# Schematic_Tektronix_Auxiliary_Front_Pane.net
KiCad netlist of a schematic drawn in EasyEDA
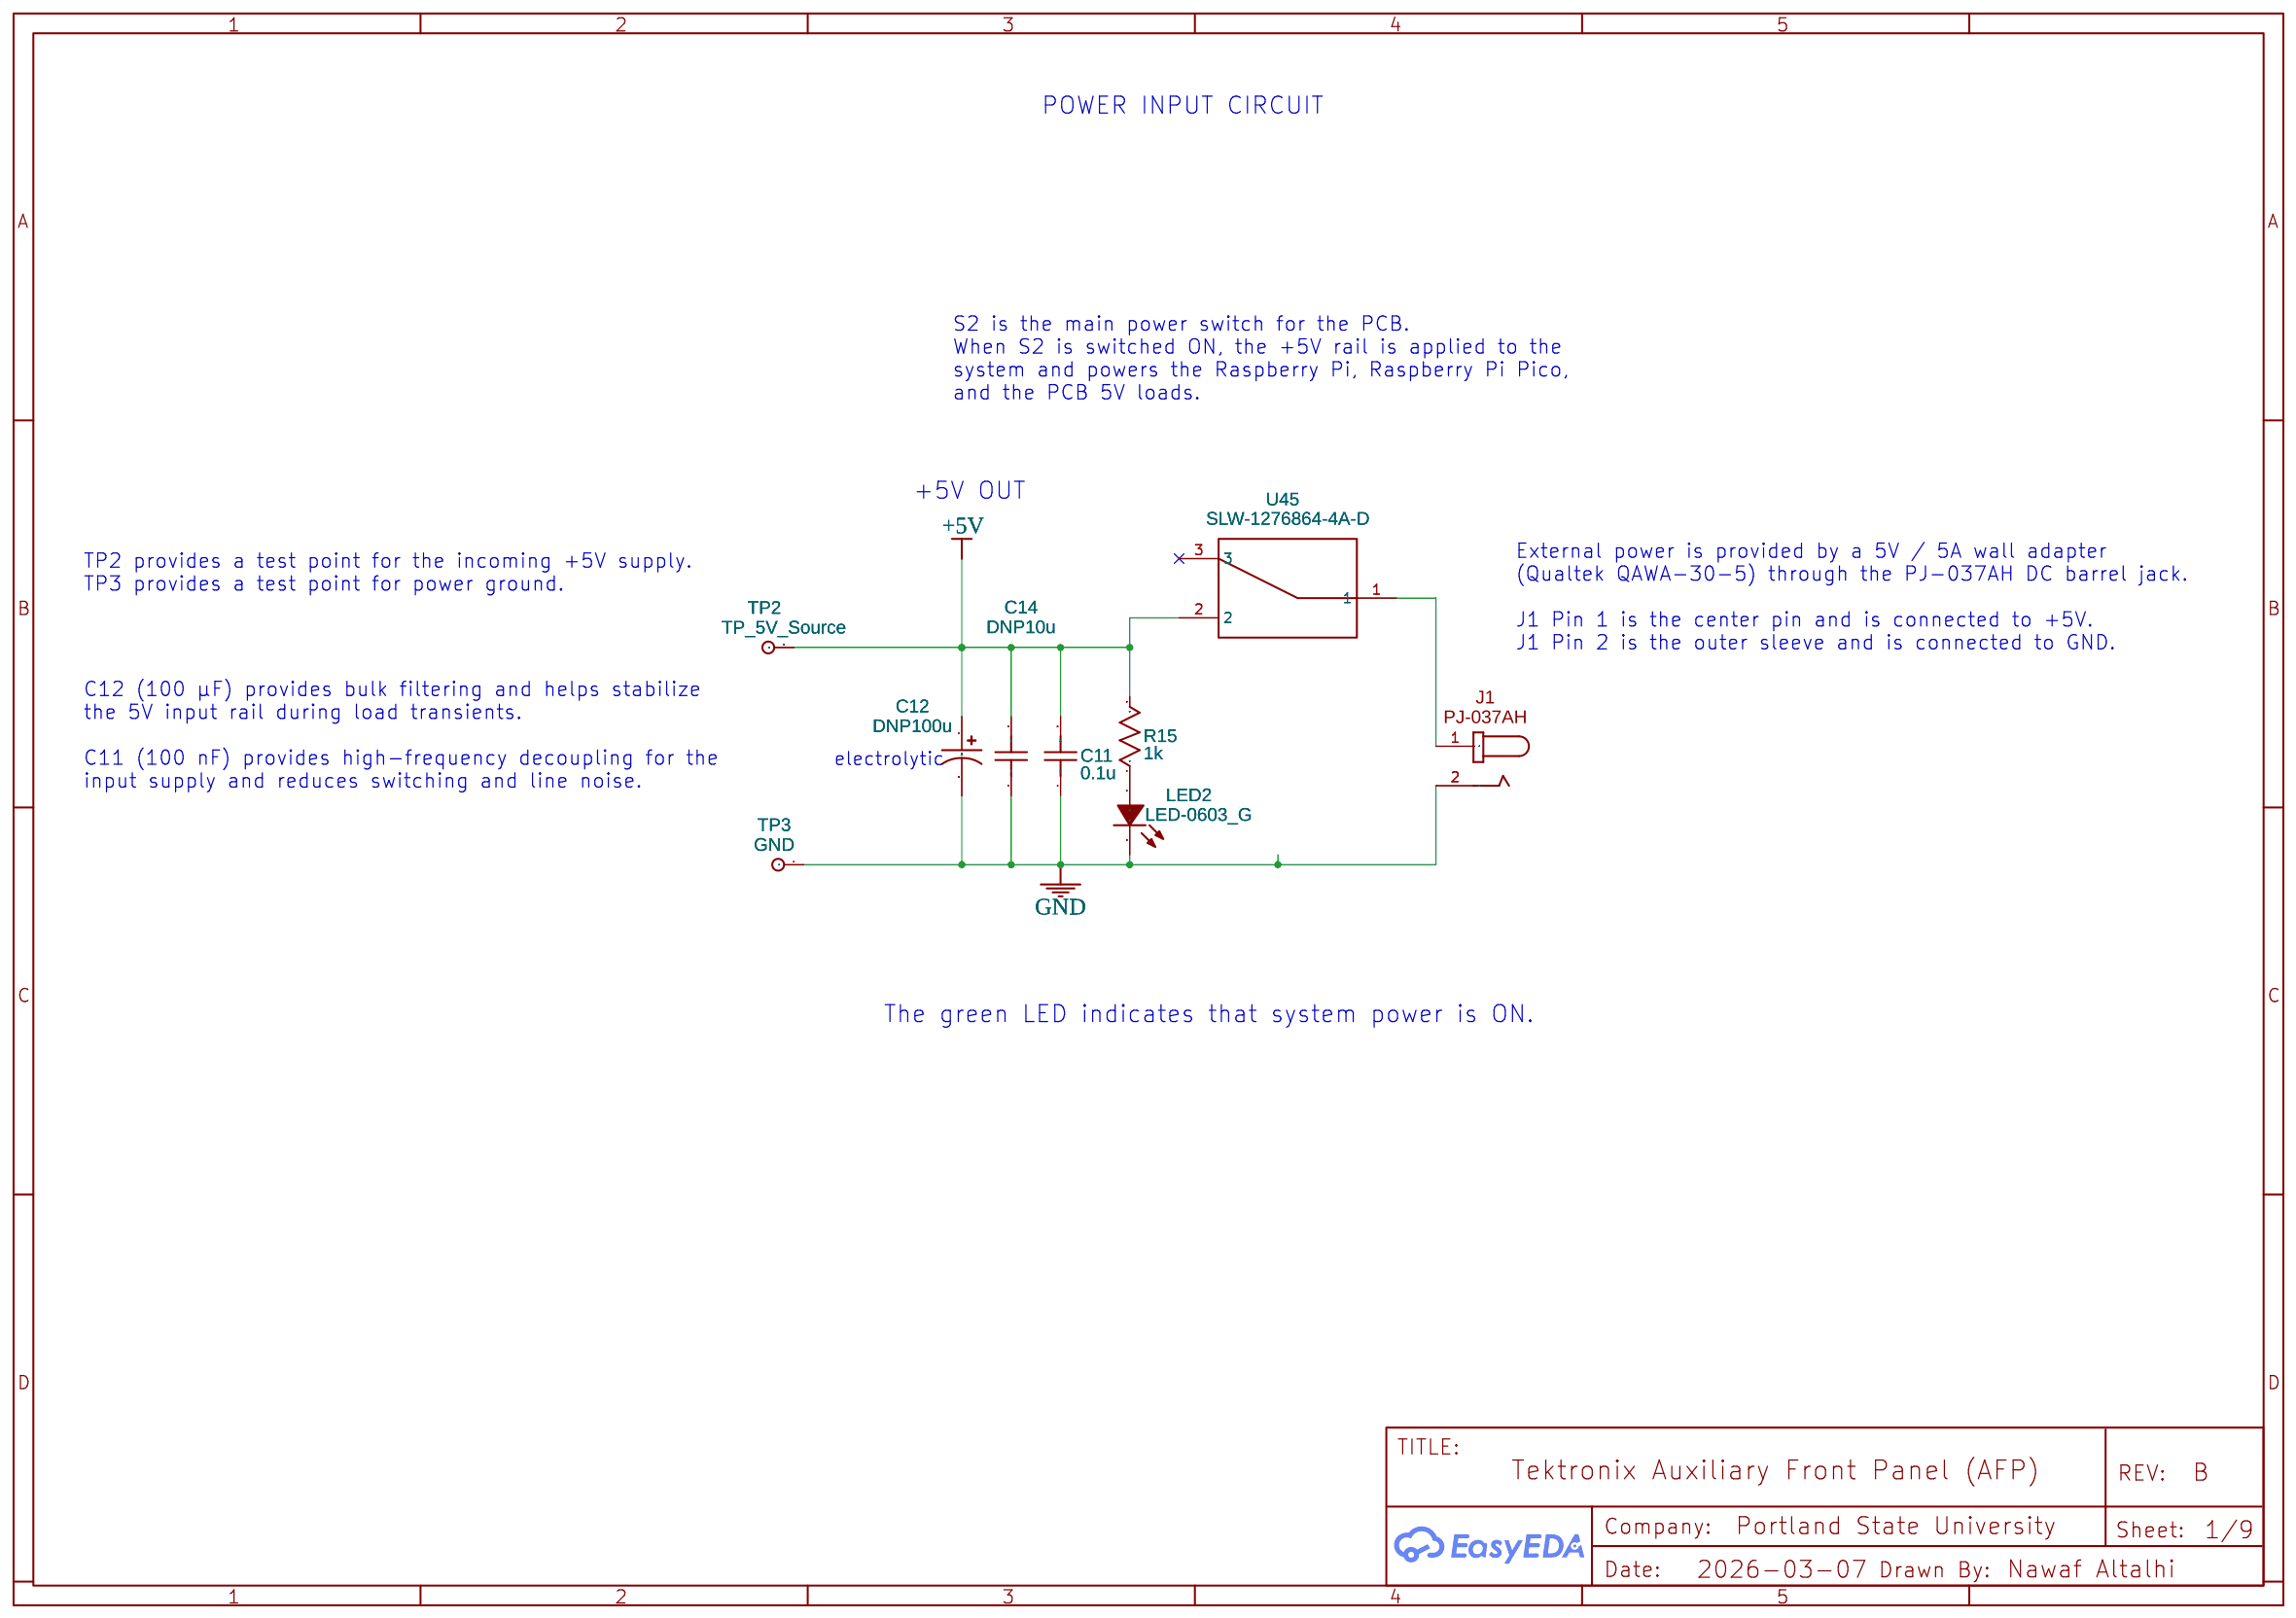
[diagram p0: 5V Power Input]
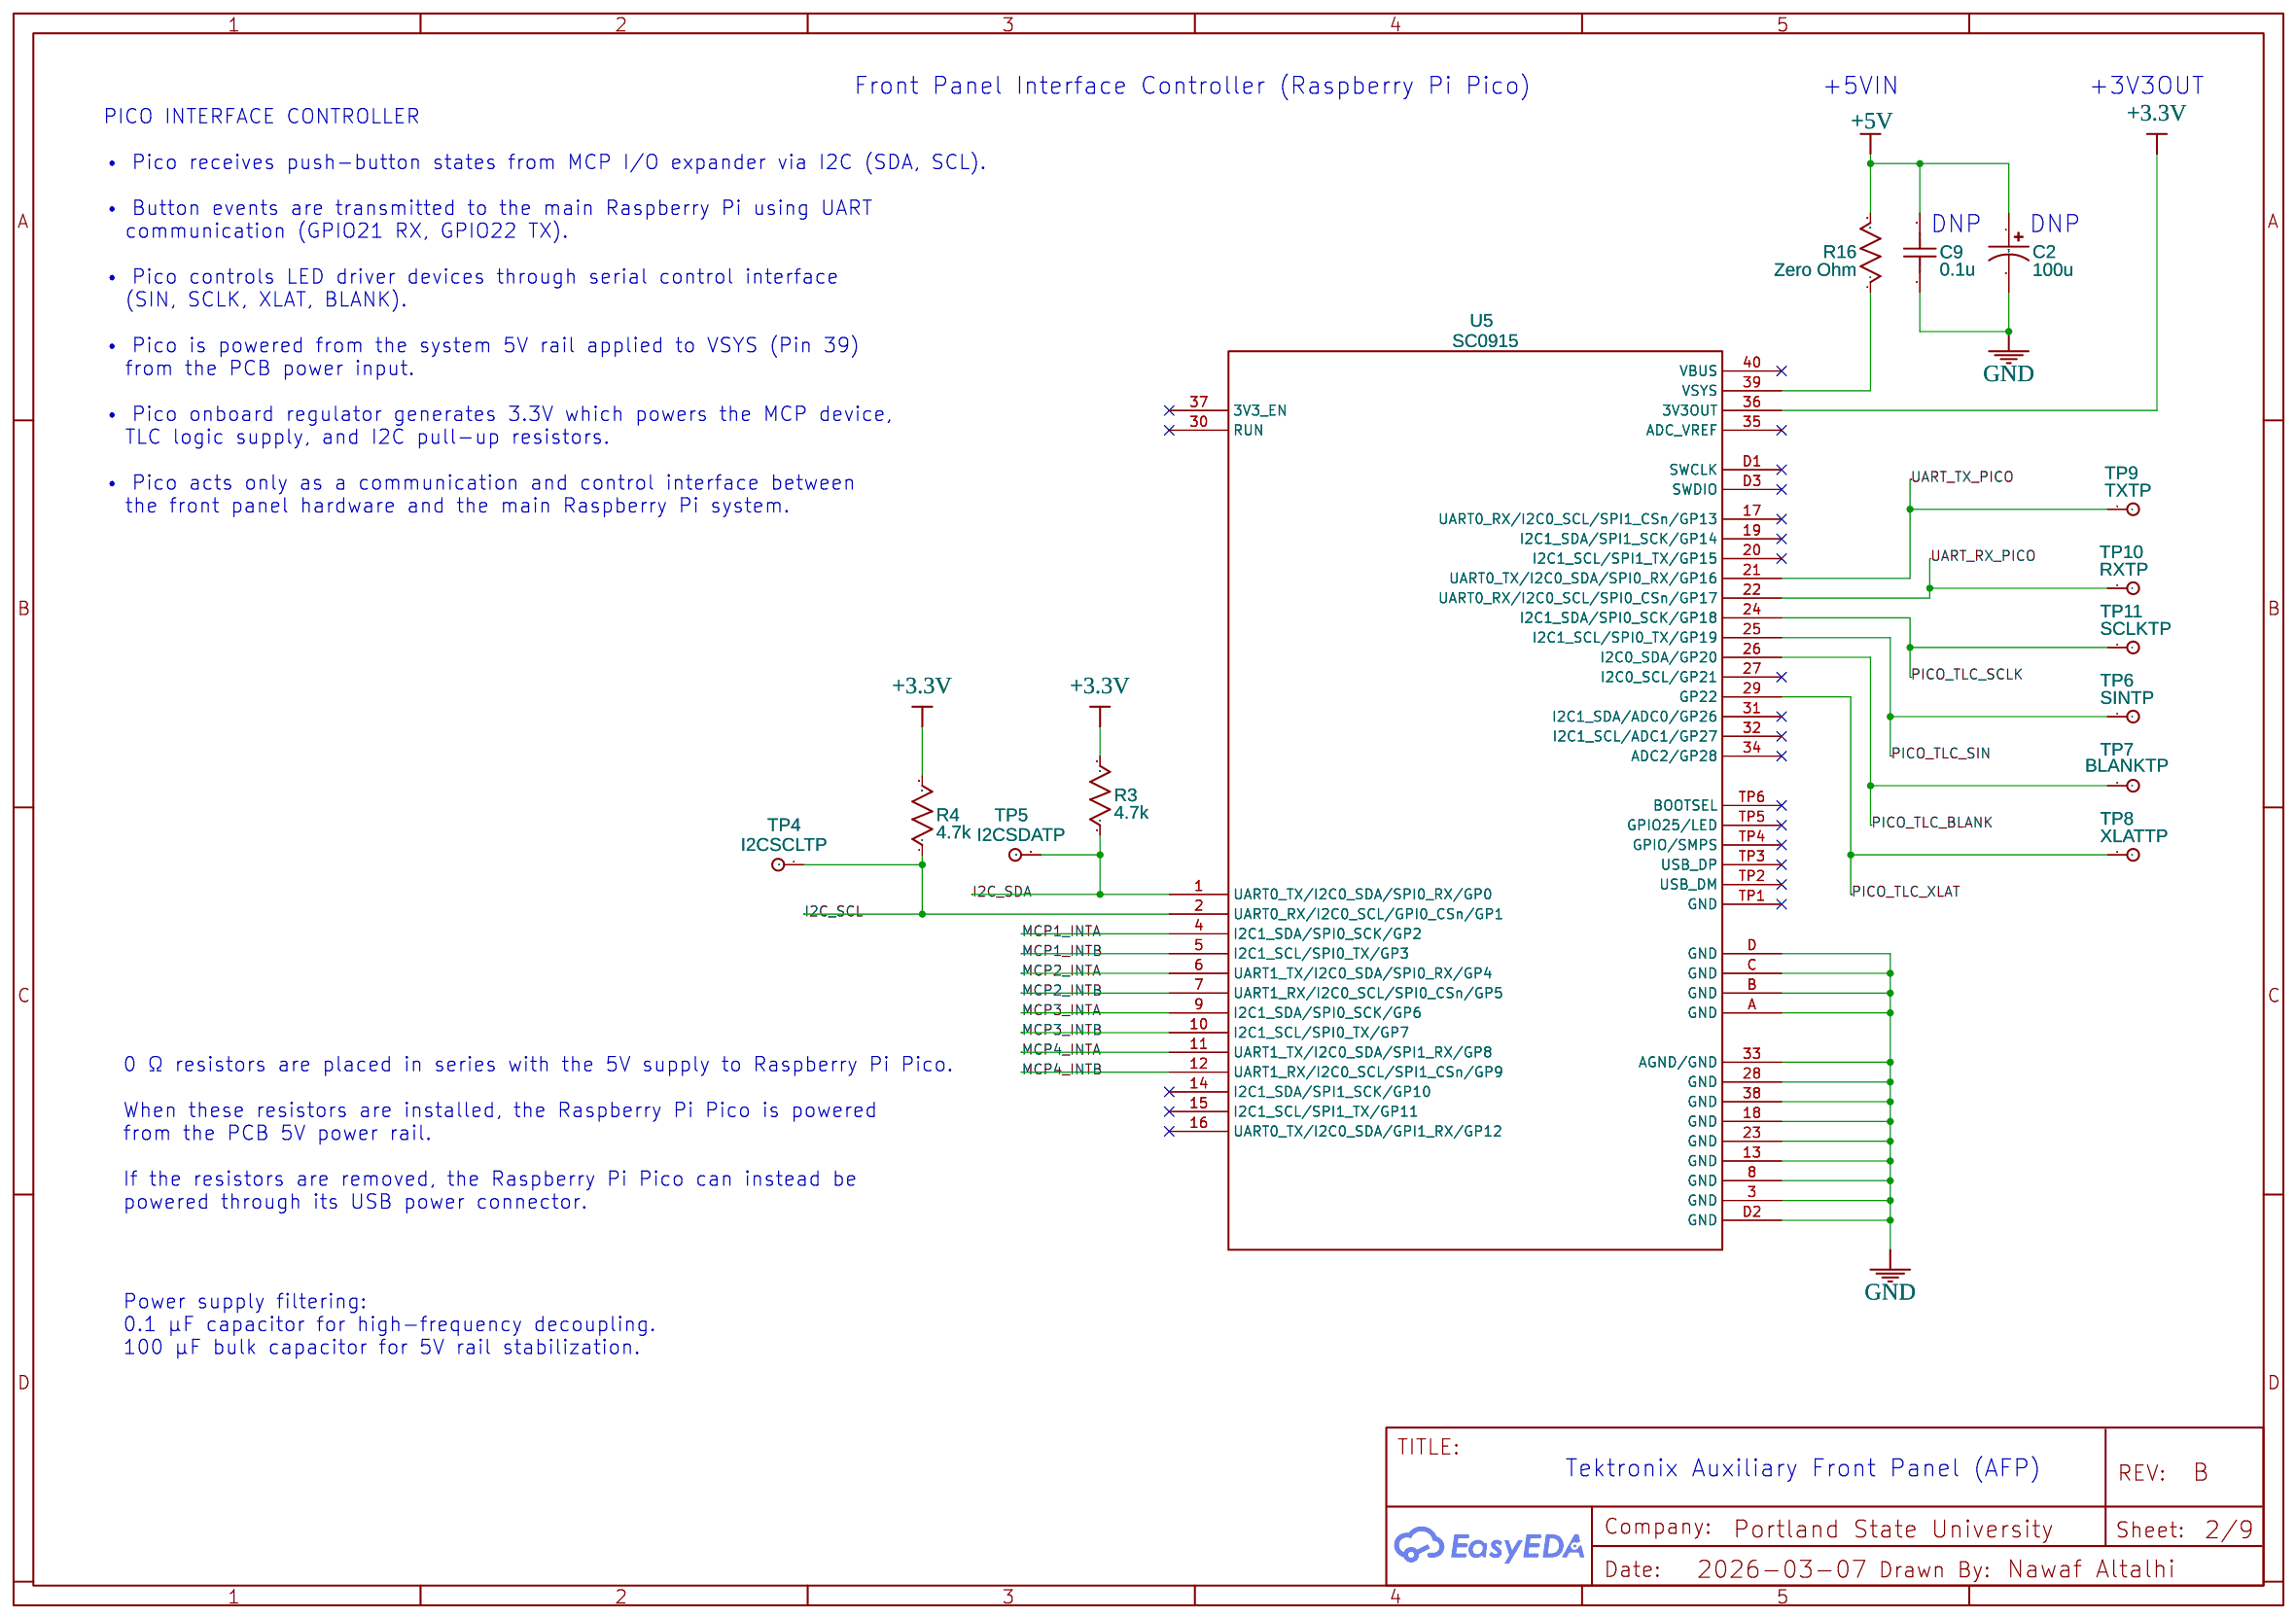
[diagram p1: Raspberry Pi Pico Interface]
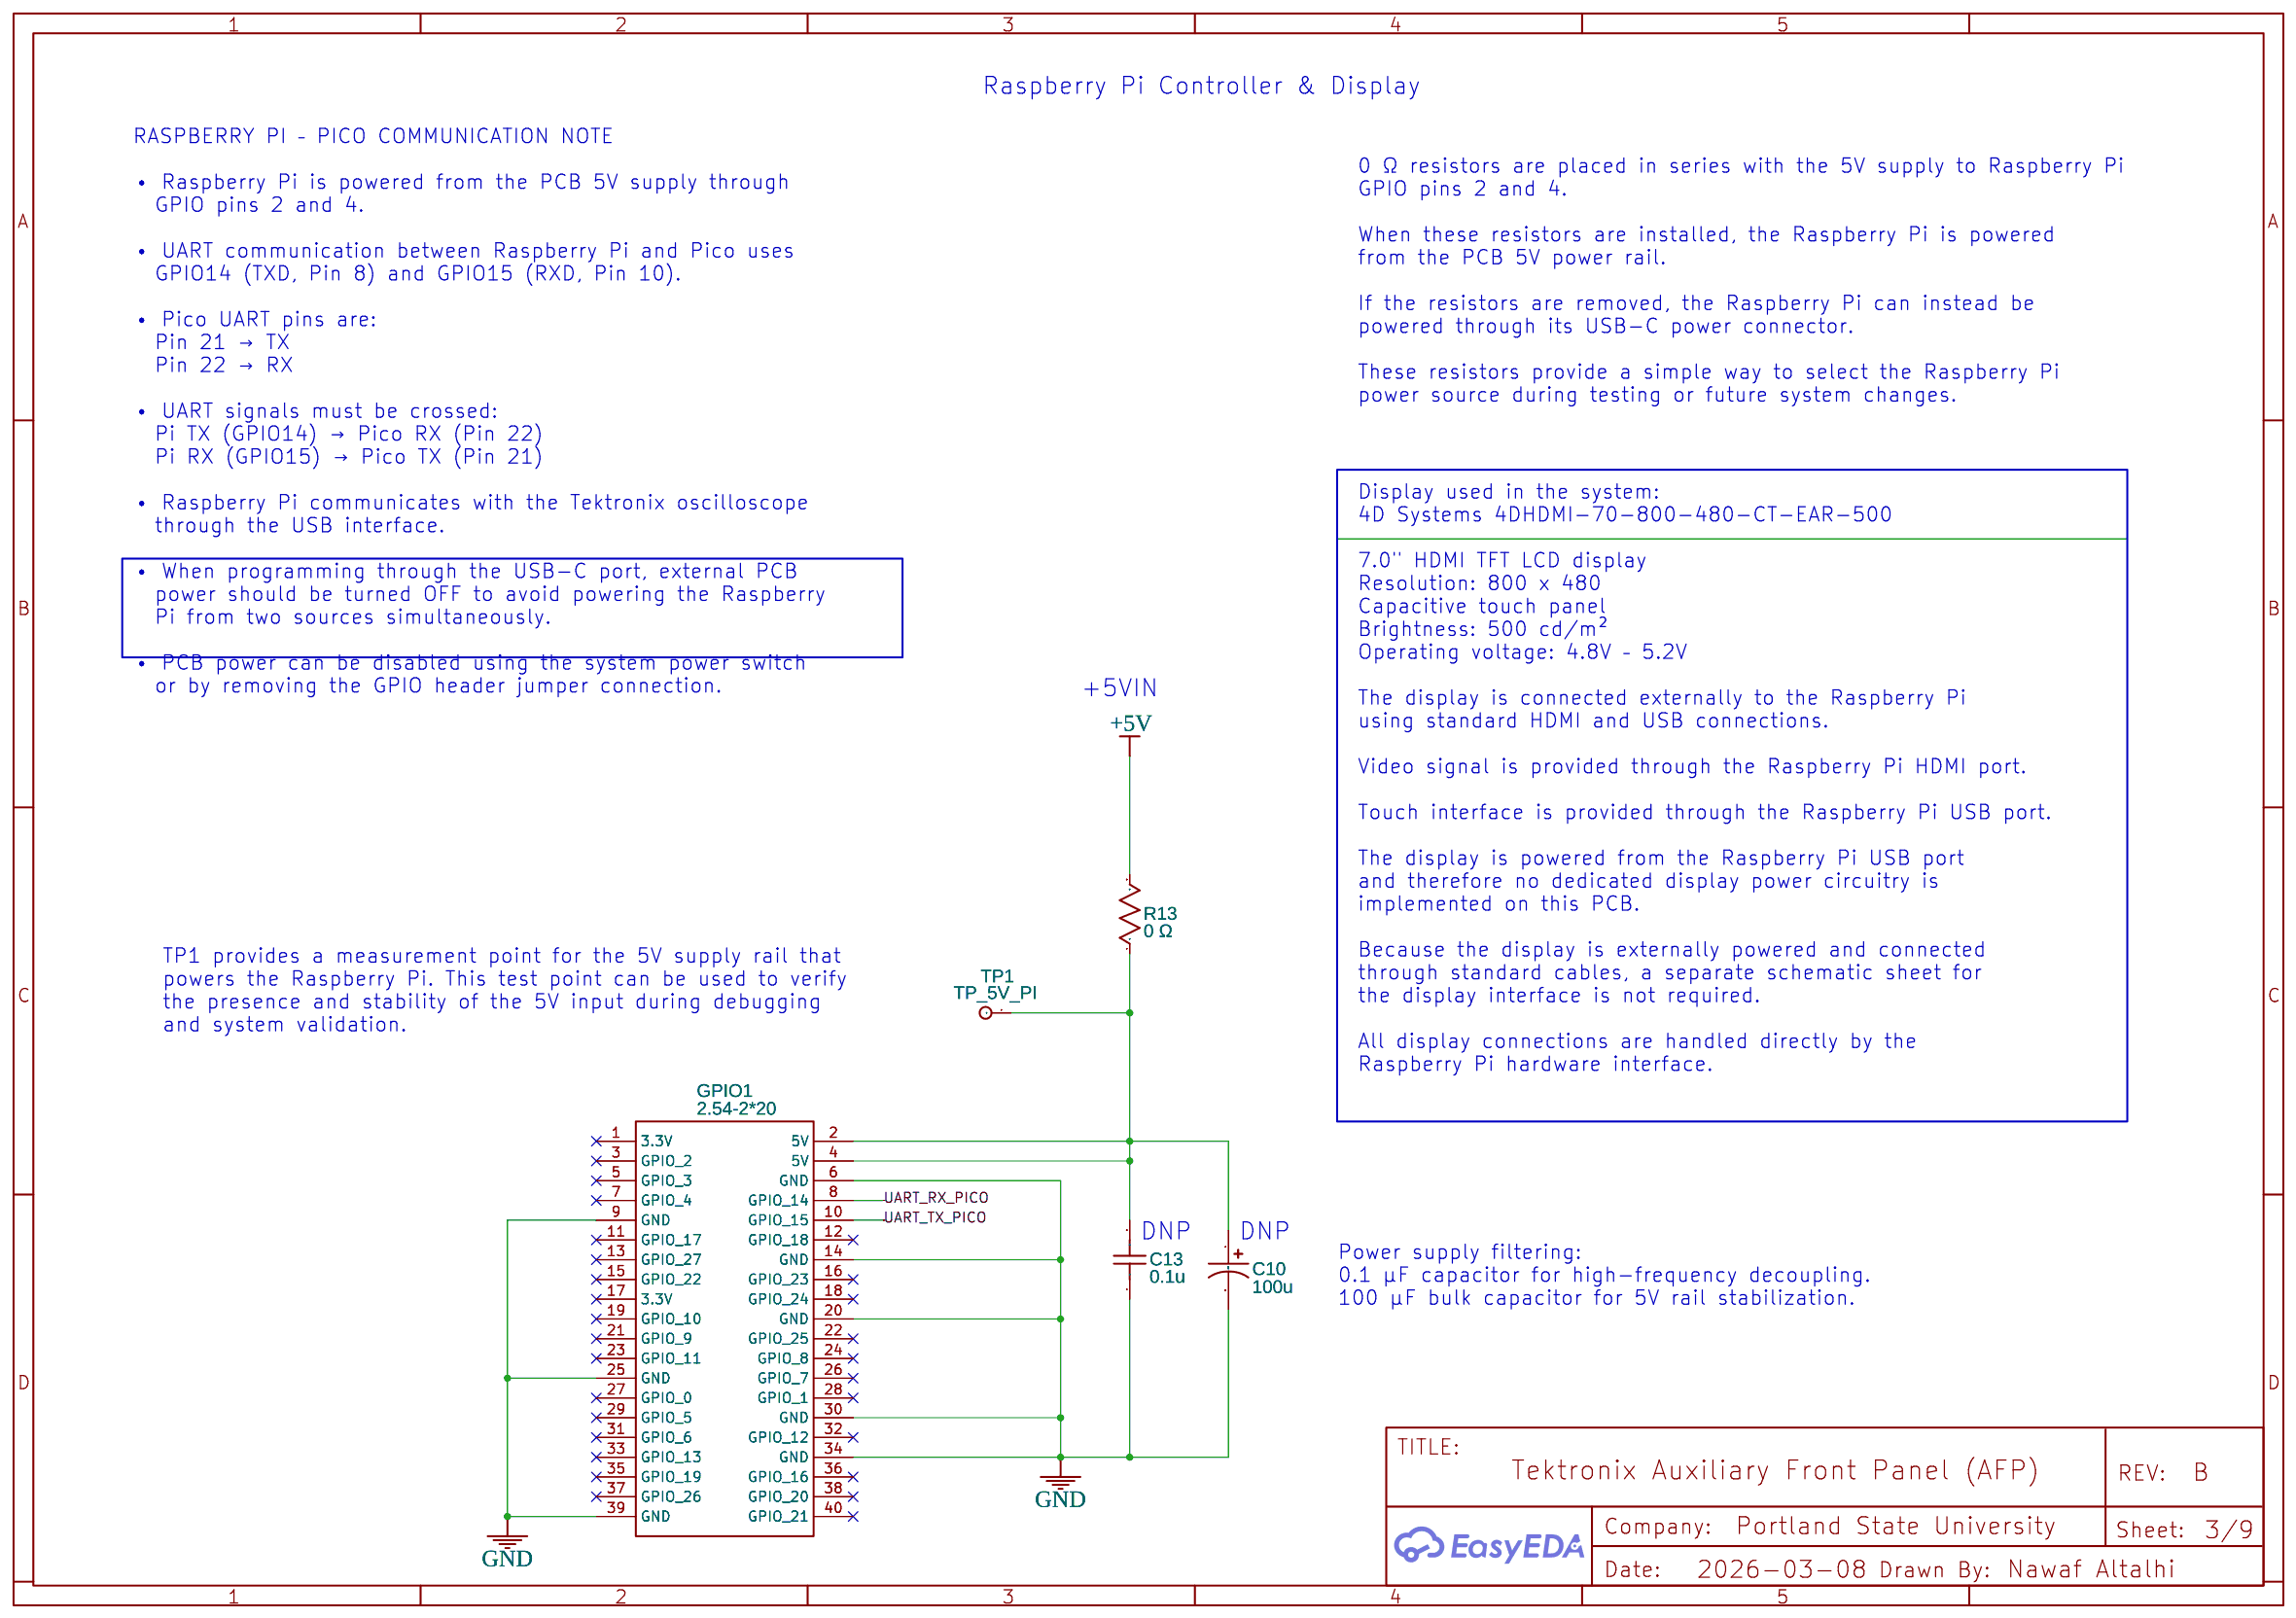
[diagram p2: Raspberry Pi Controller]
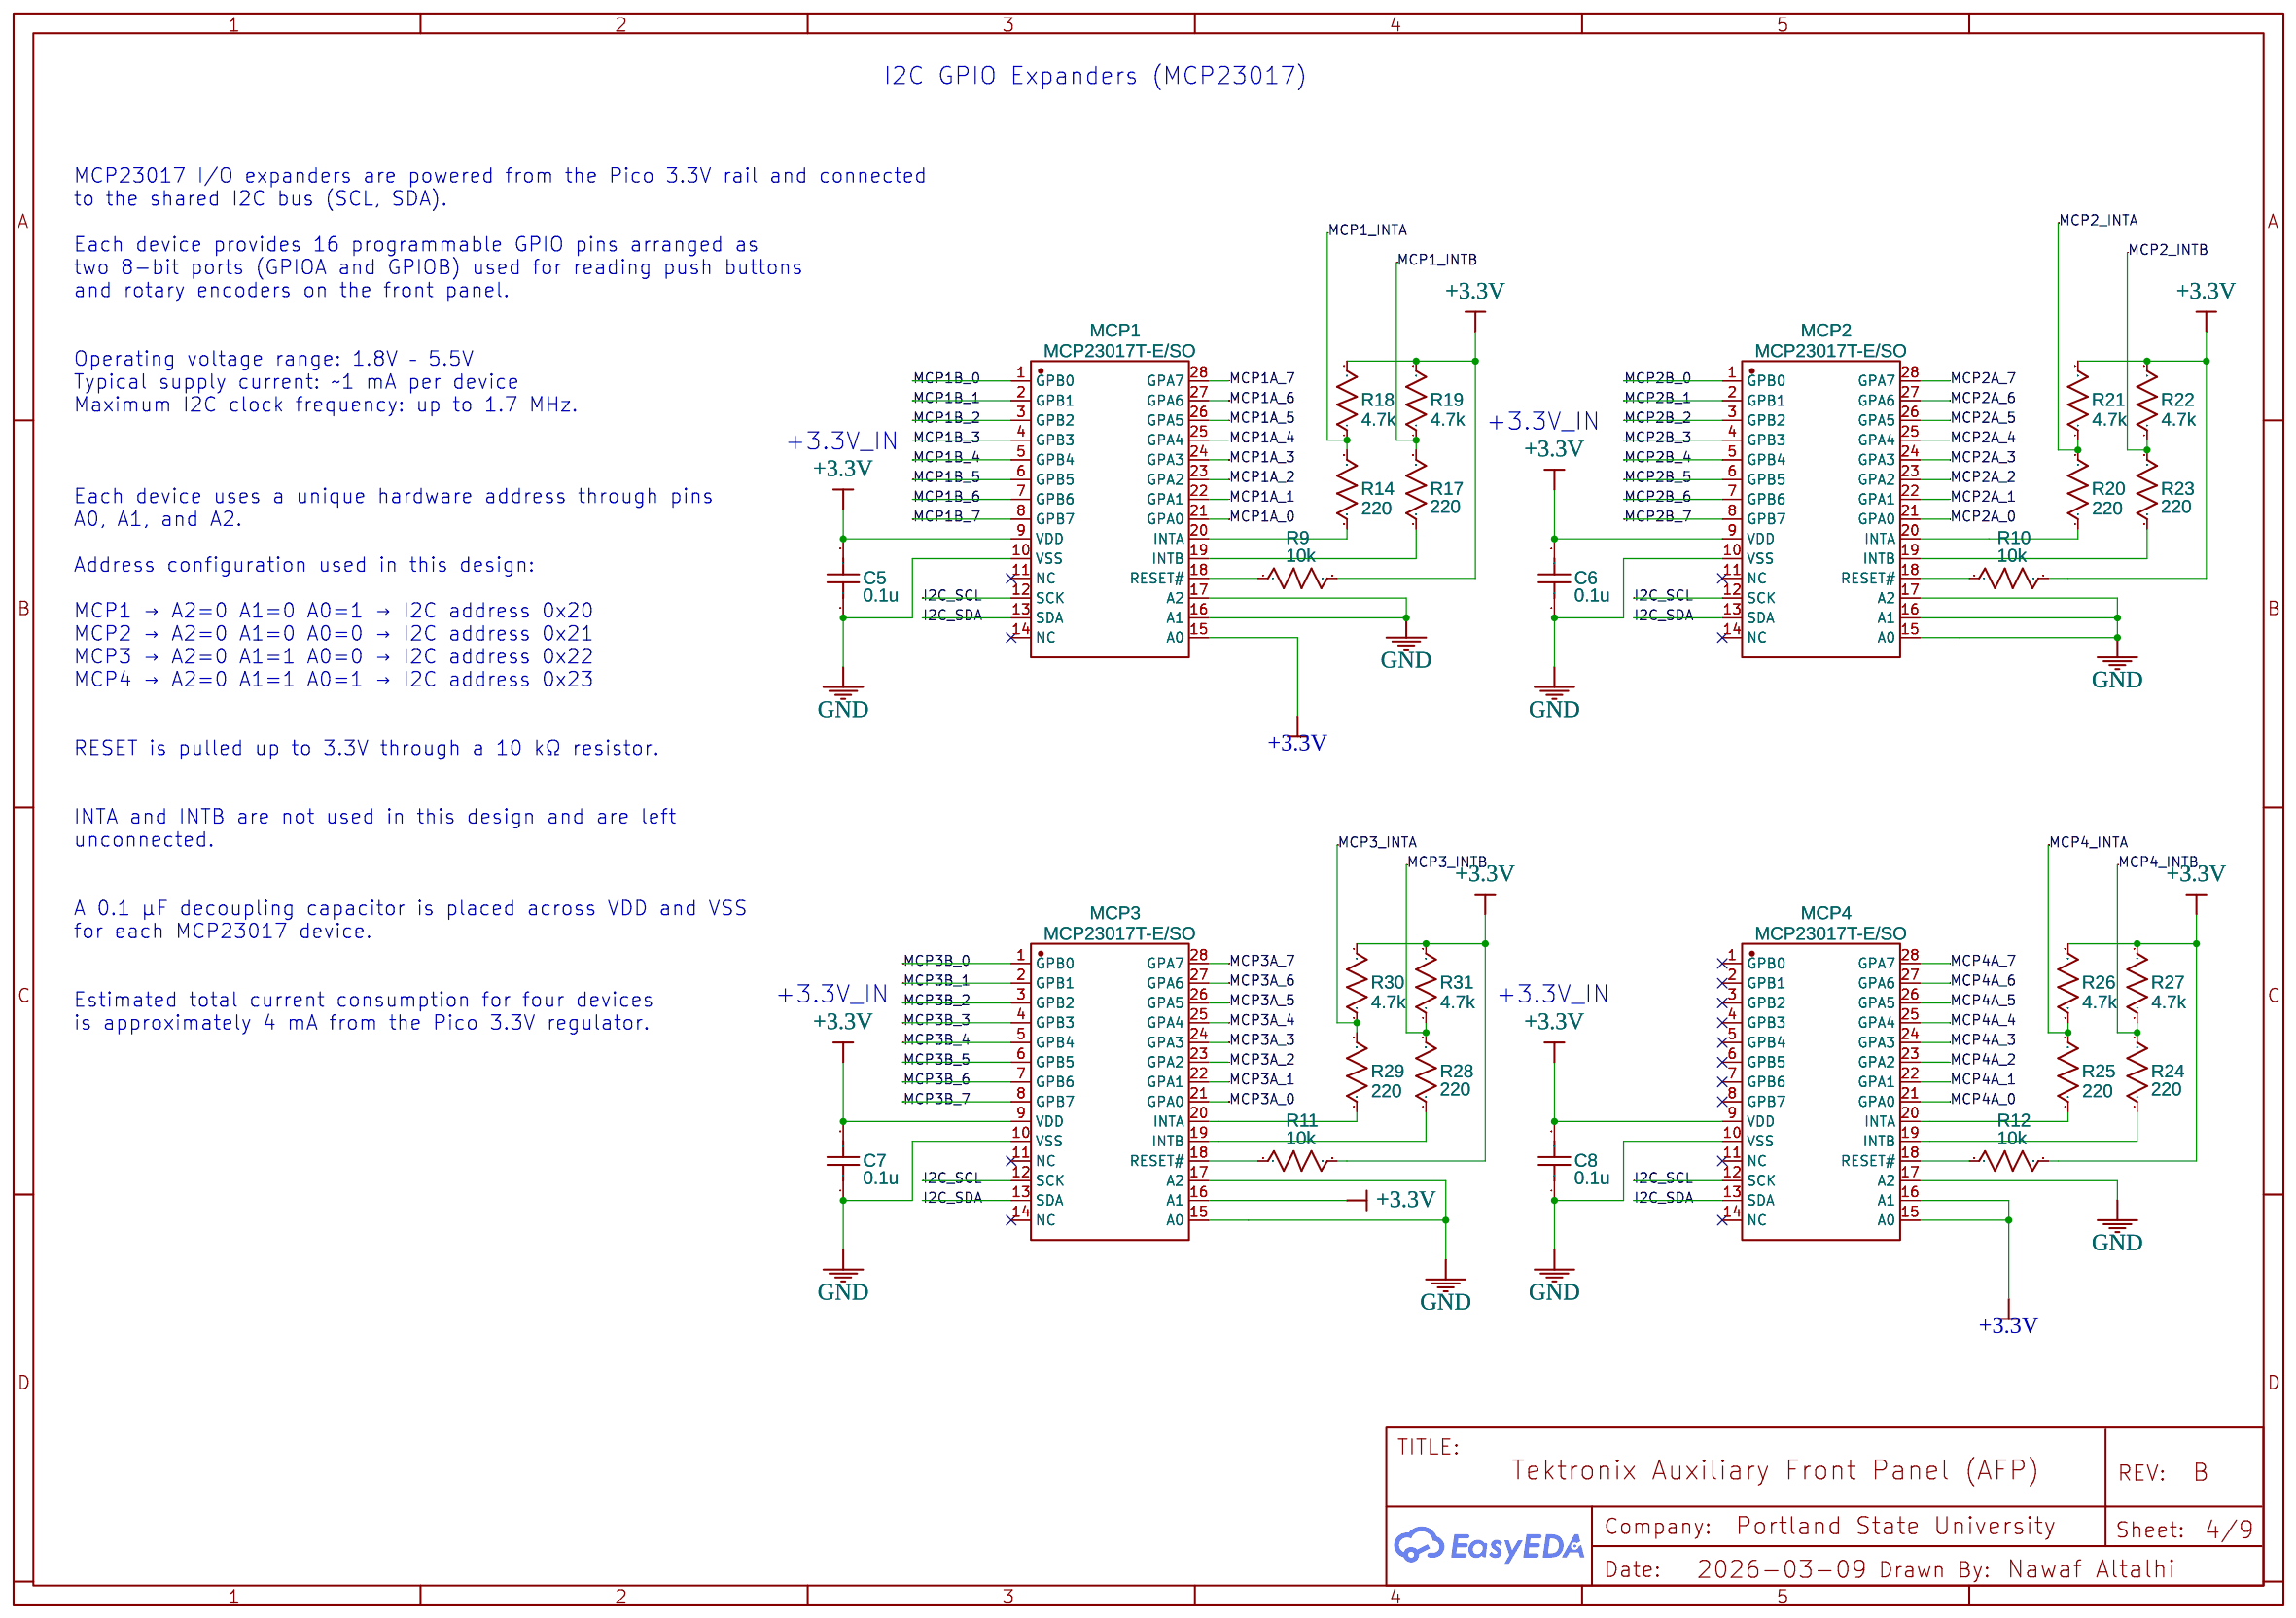
[diagram p3: MCP23017]
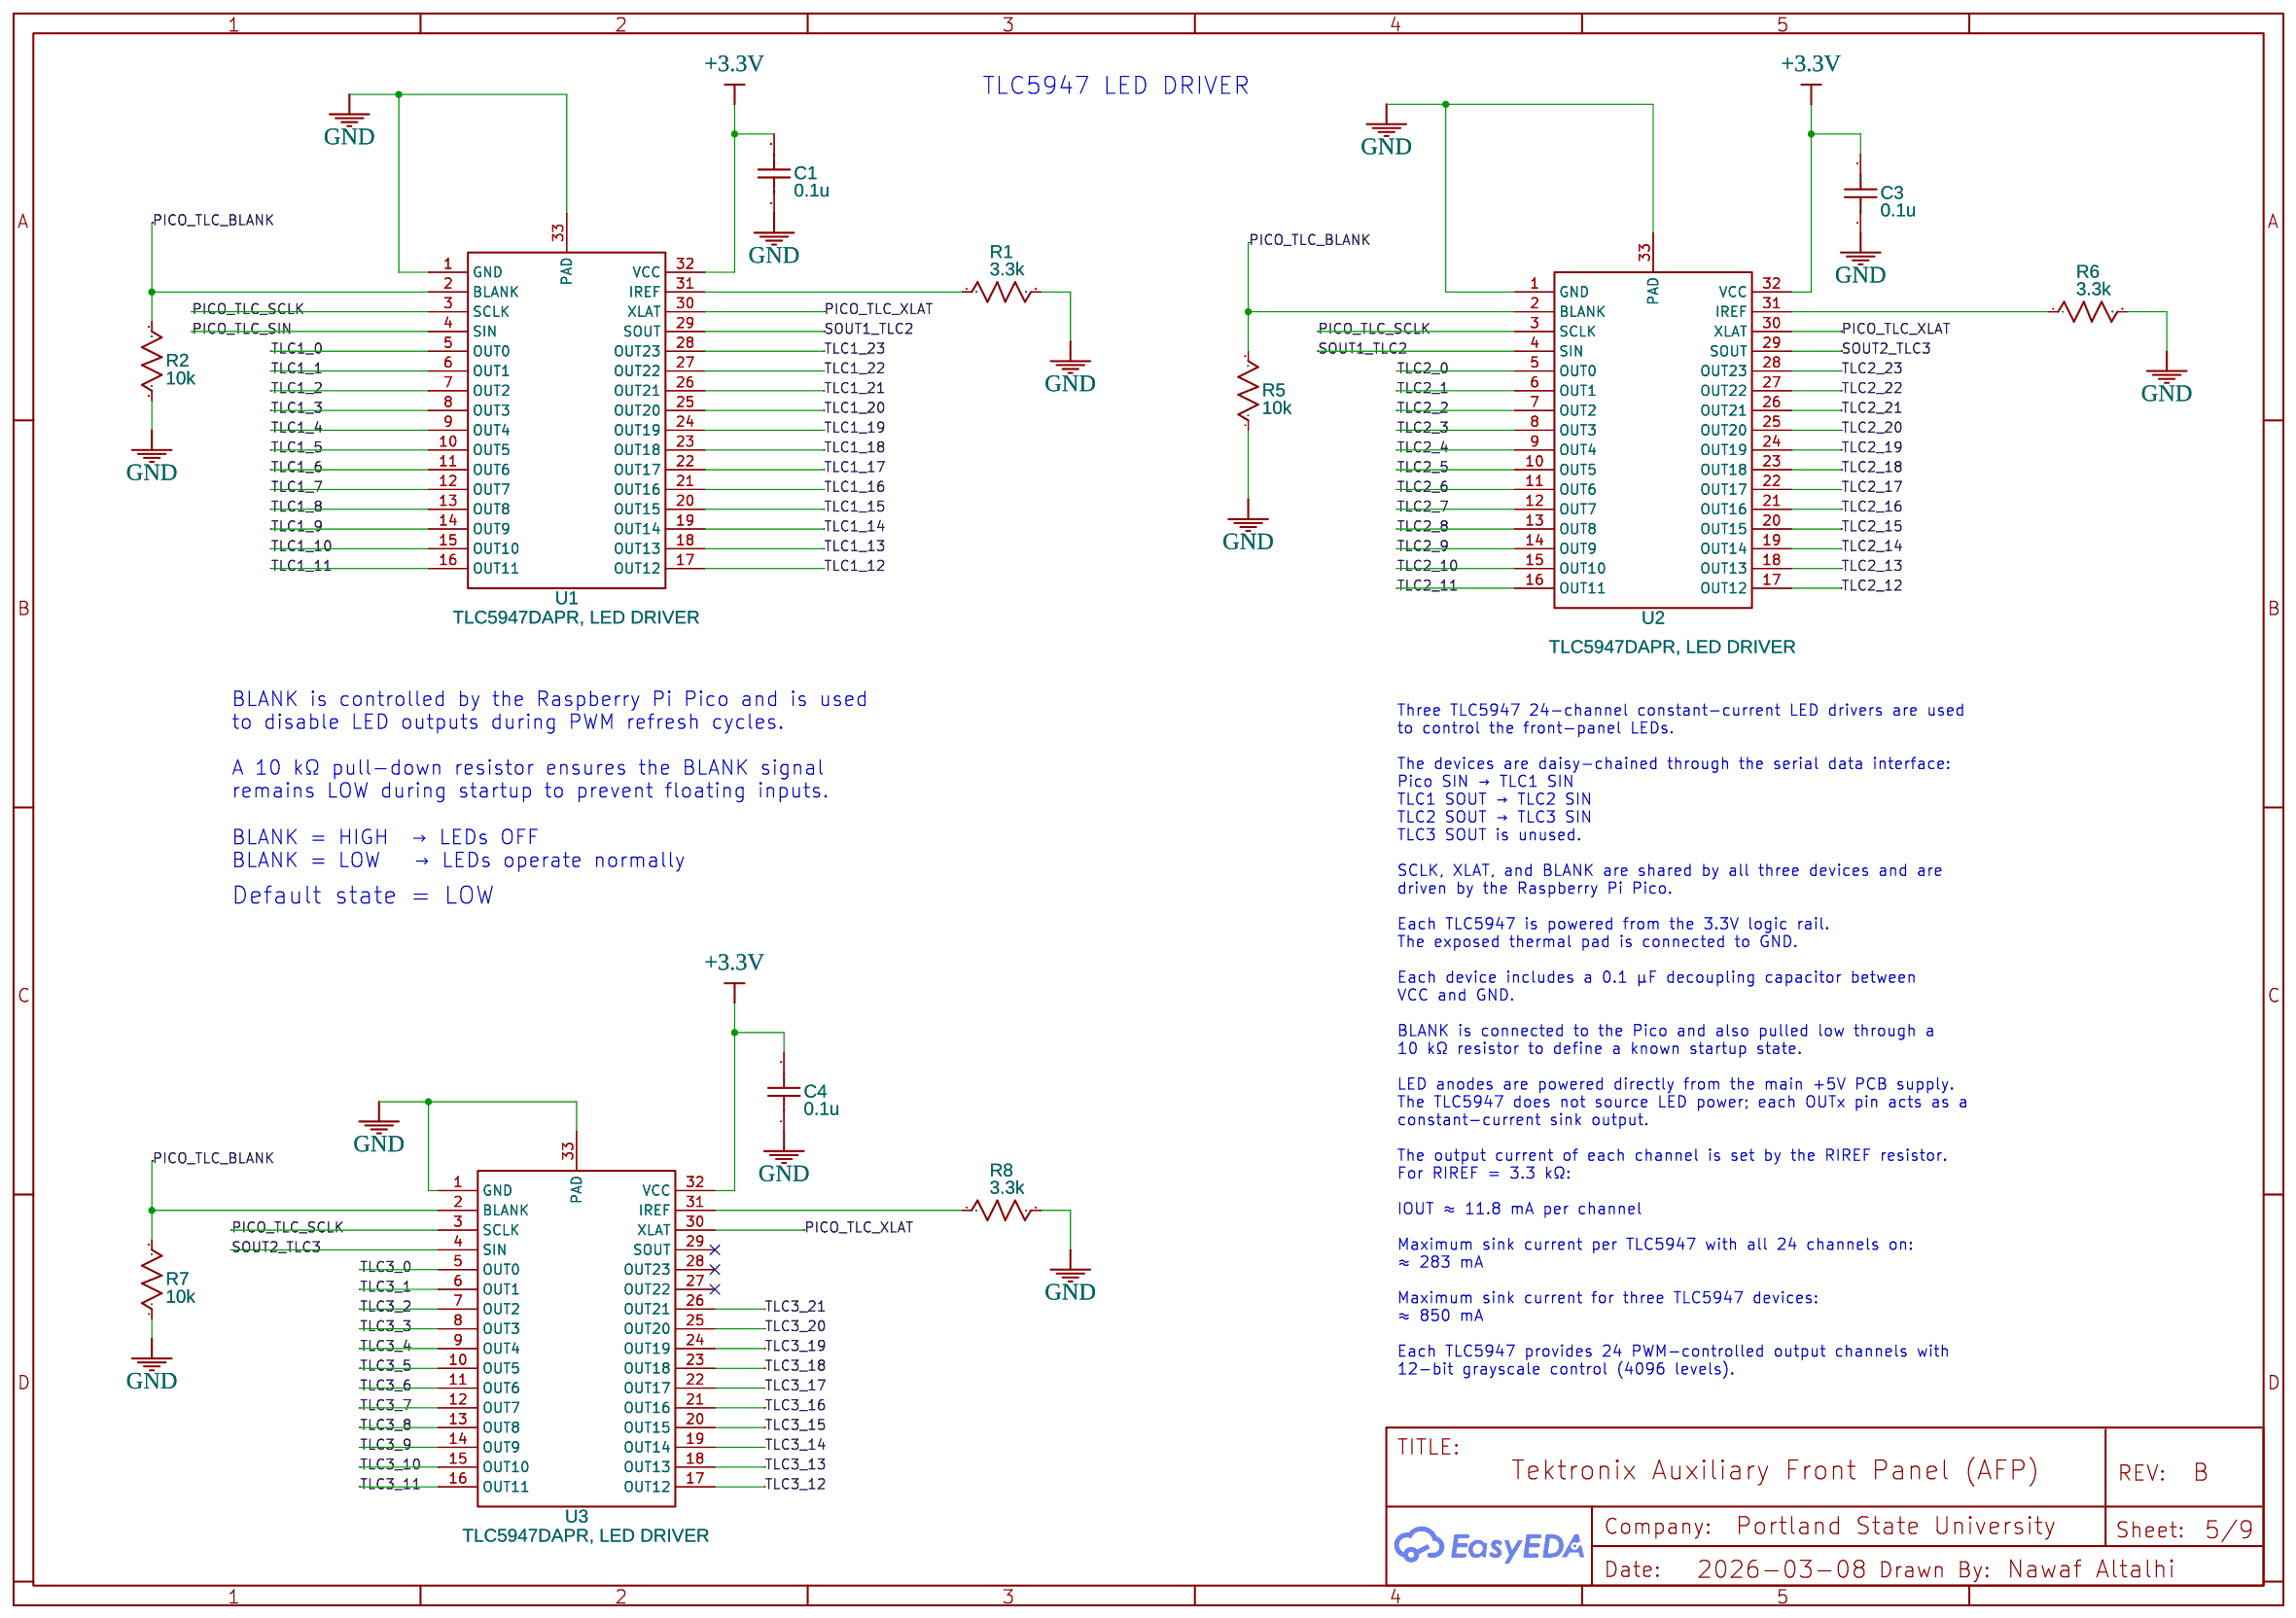
[diagram p4: TLC5947]
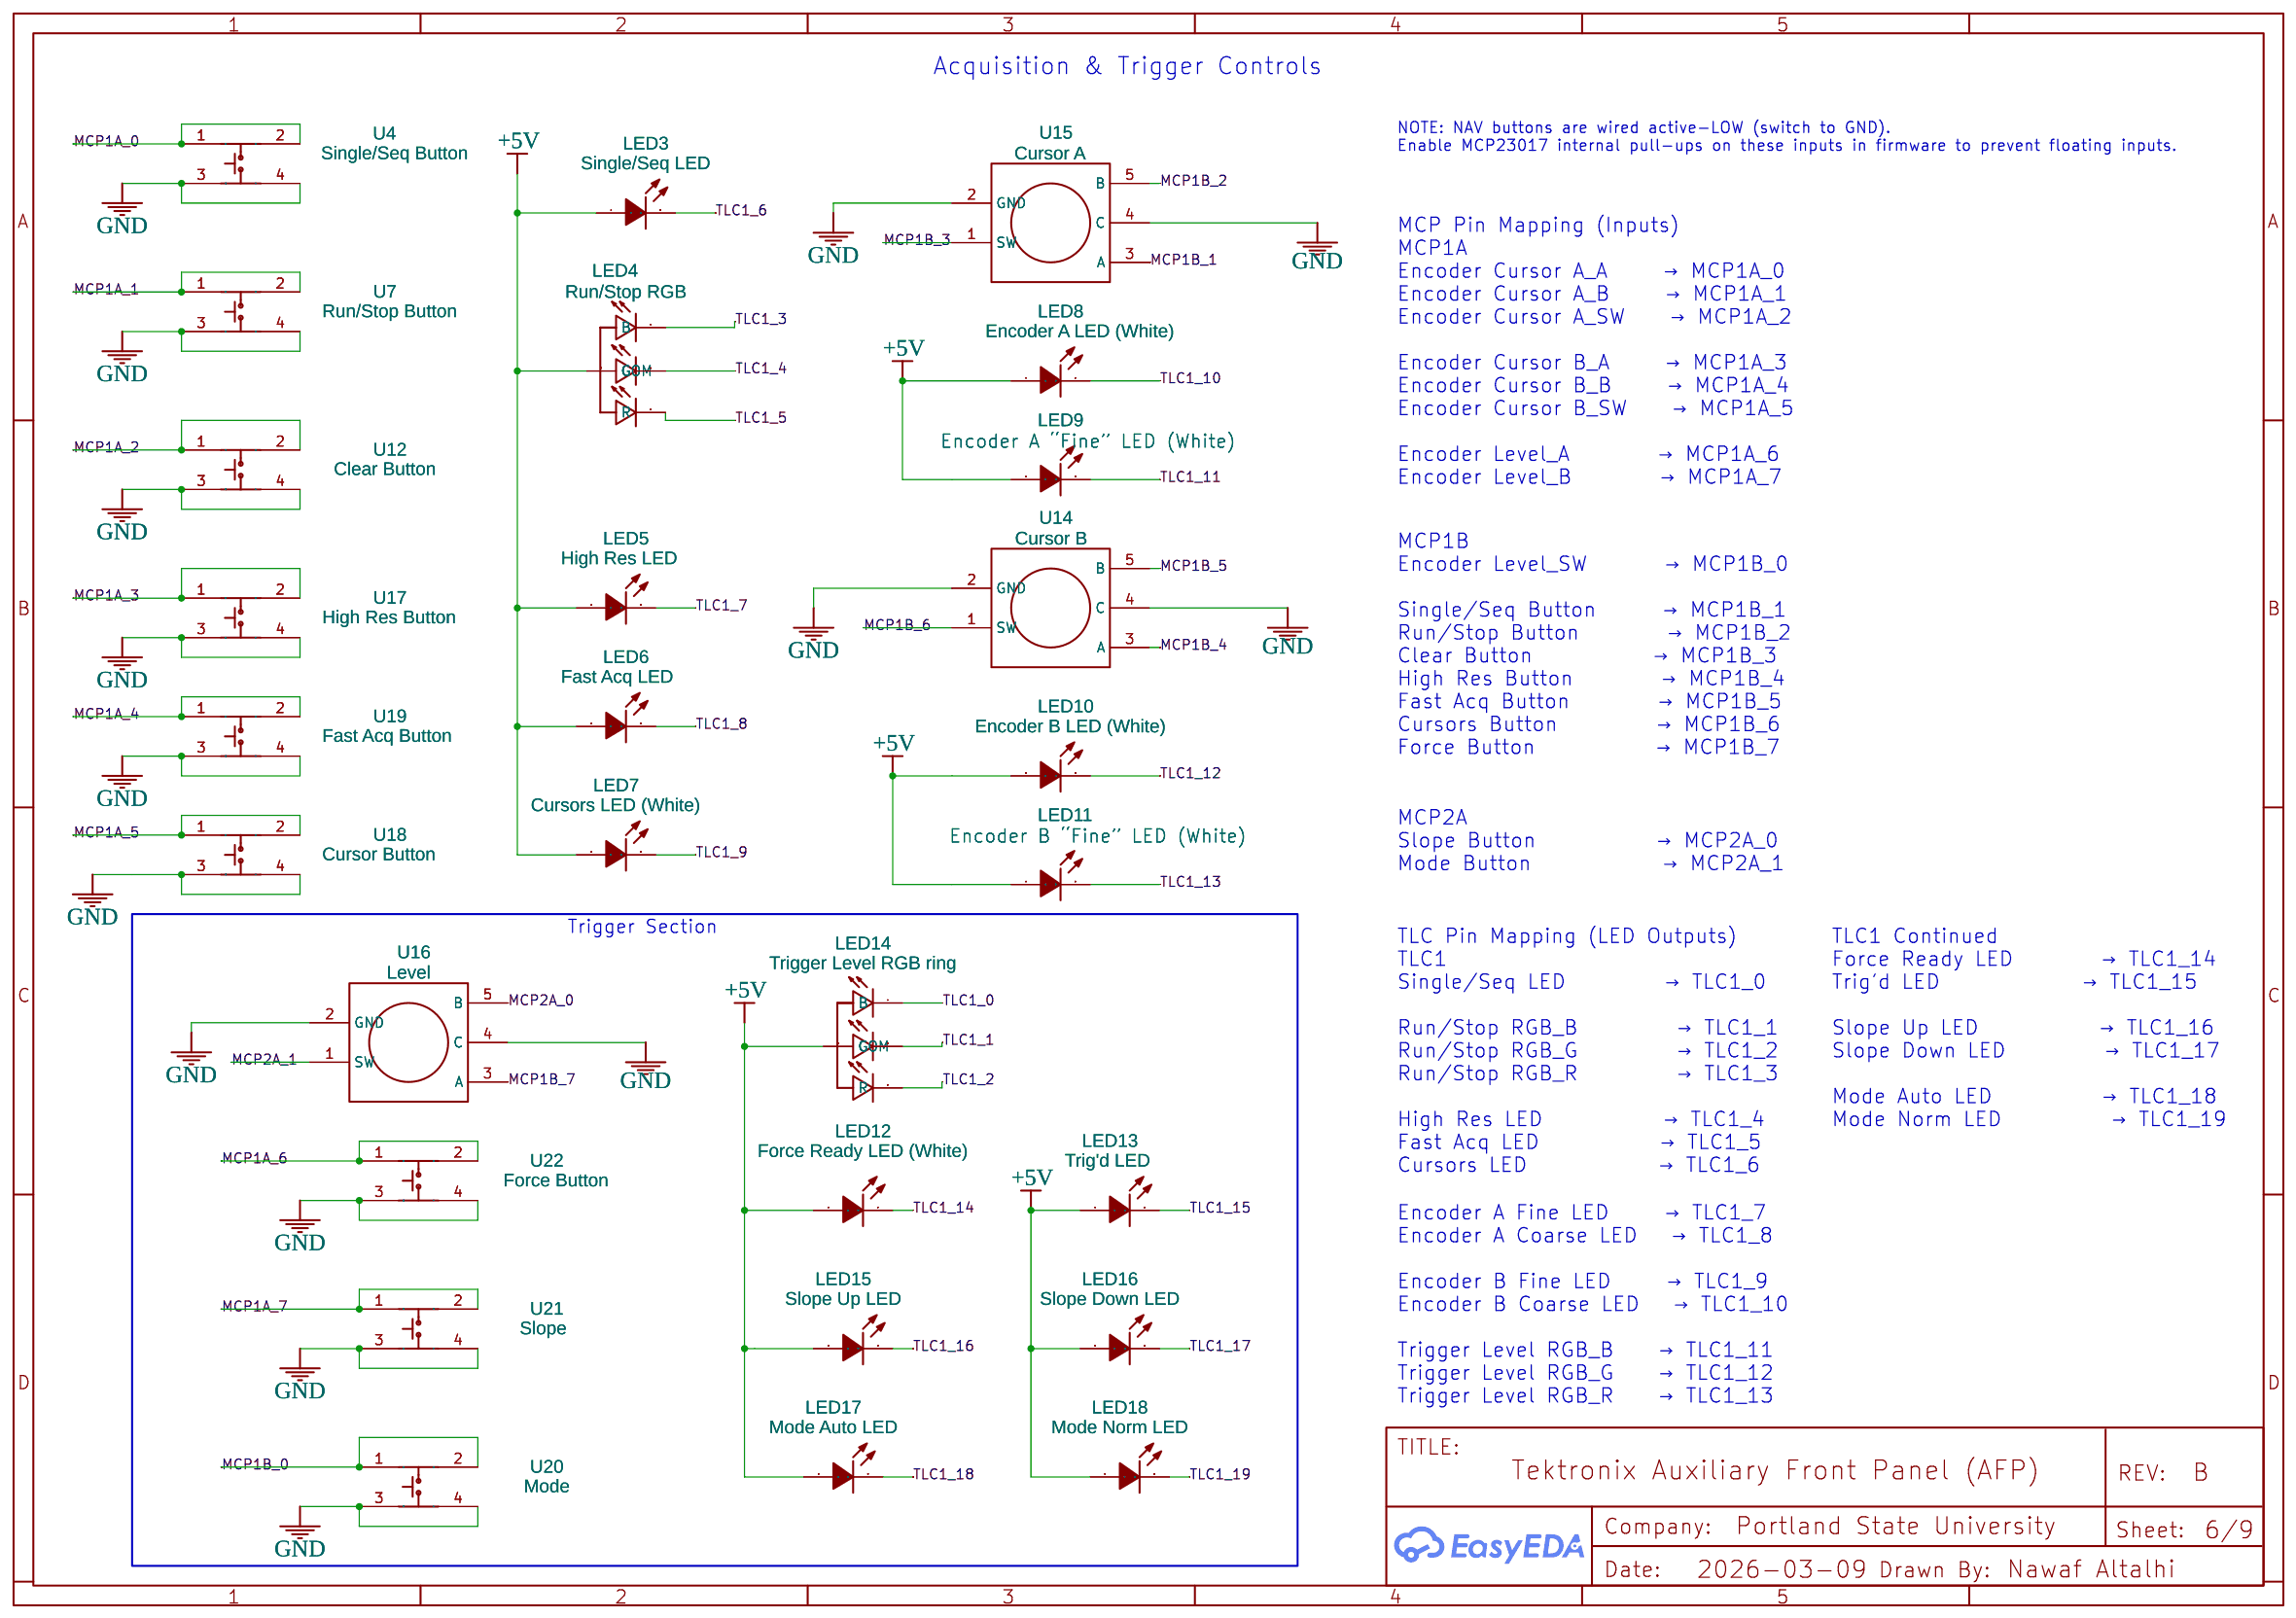
[diagram p5: Acquisition & Trigger Controls]
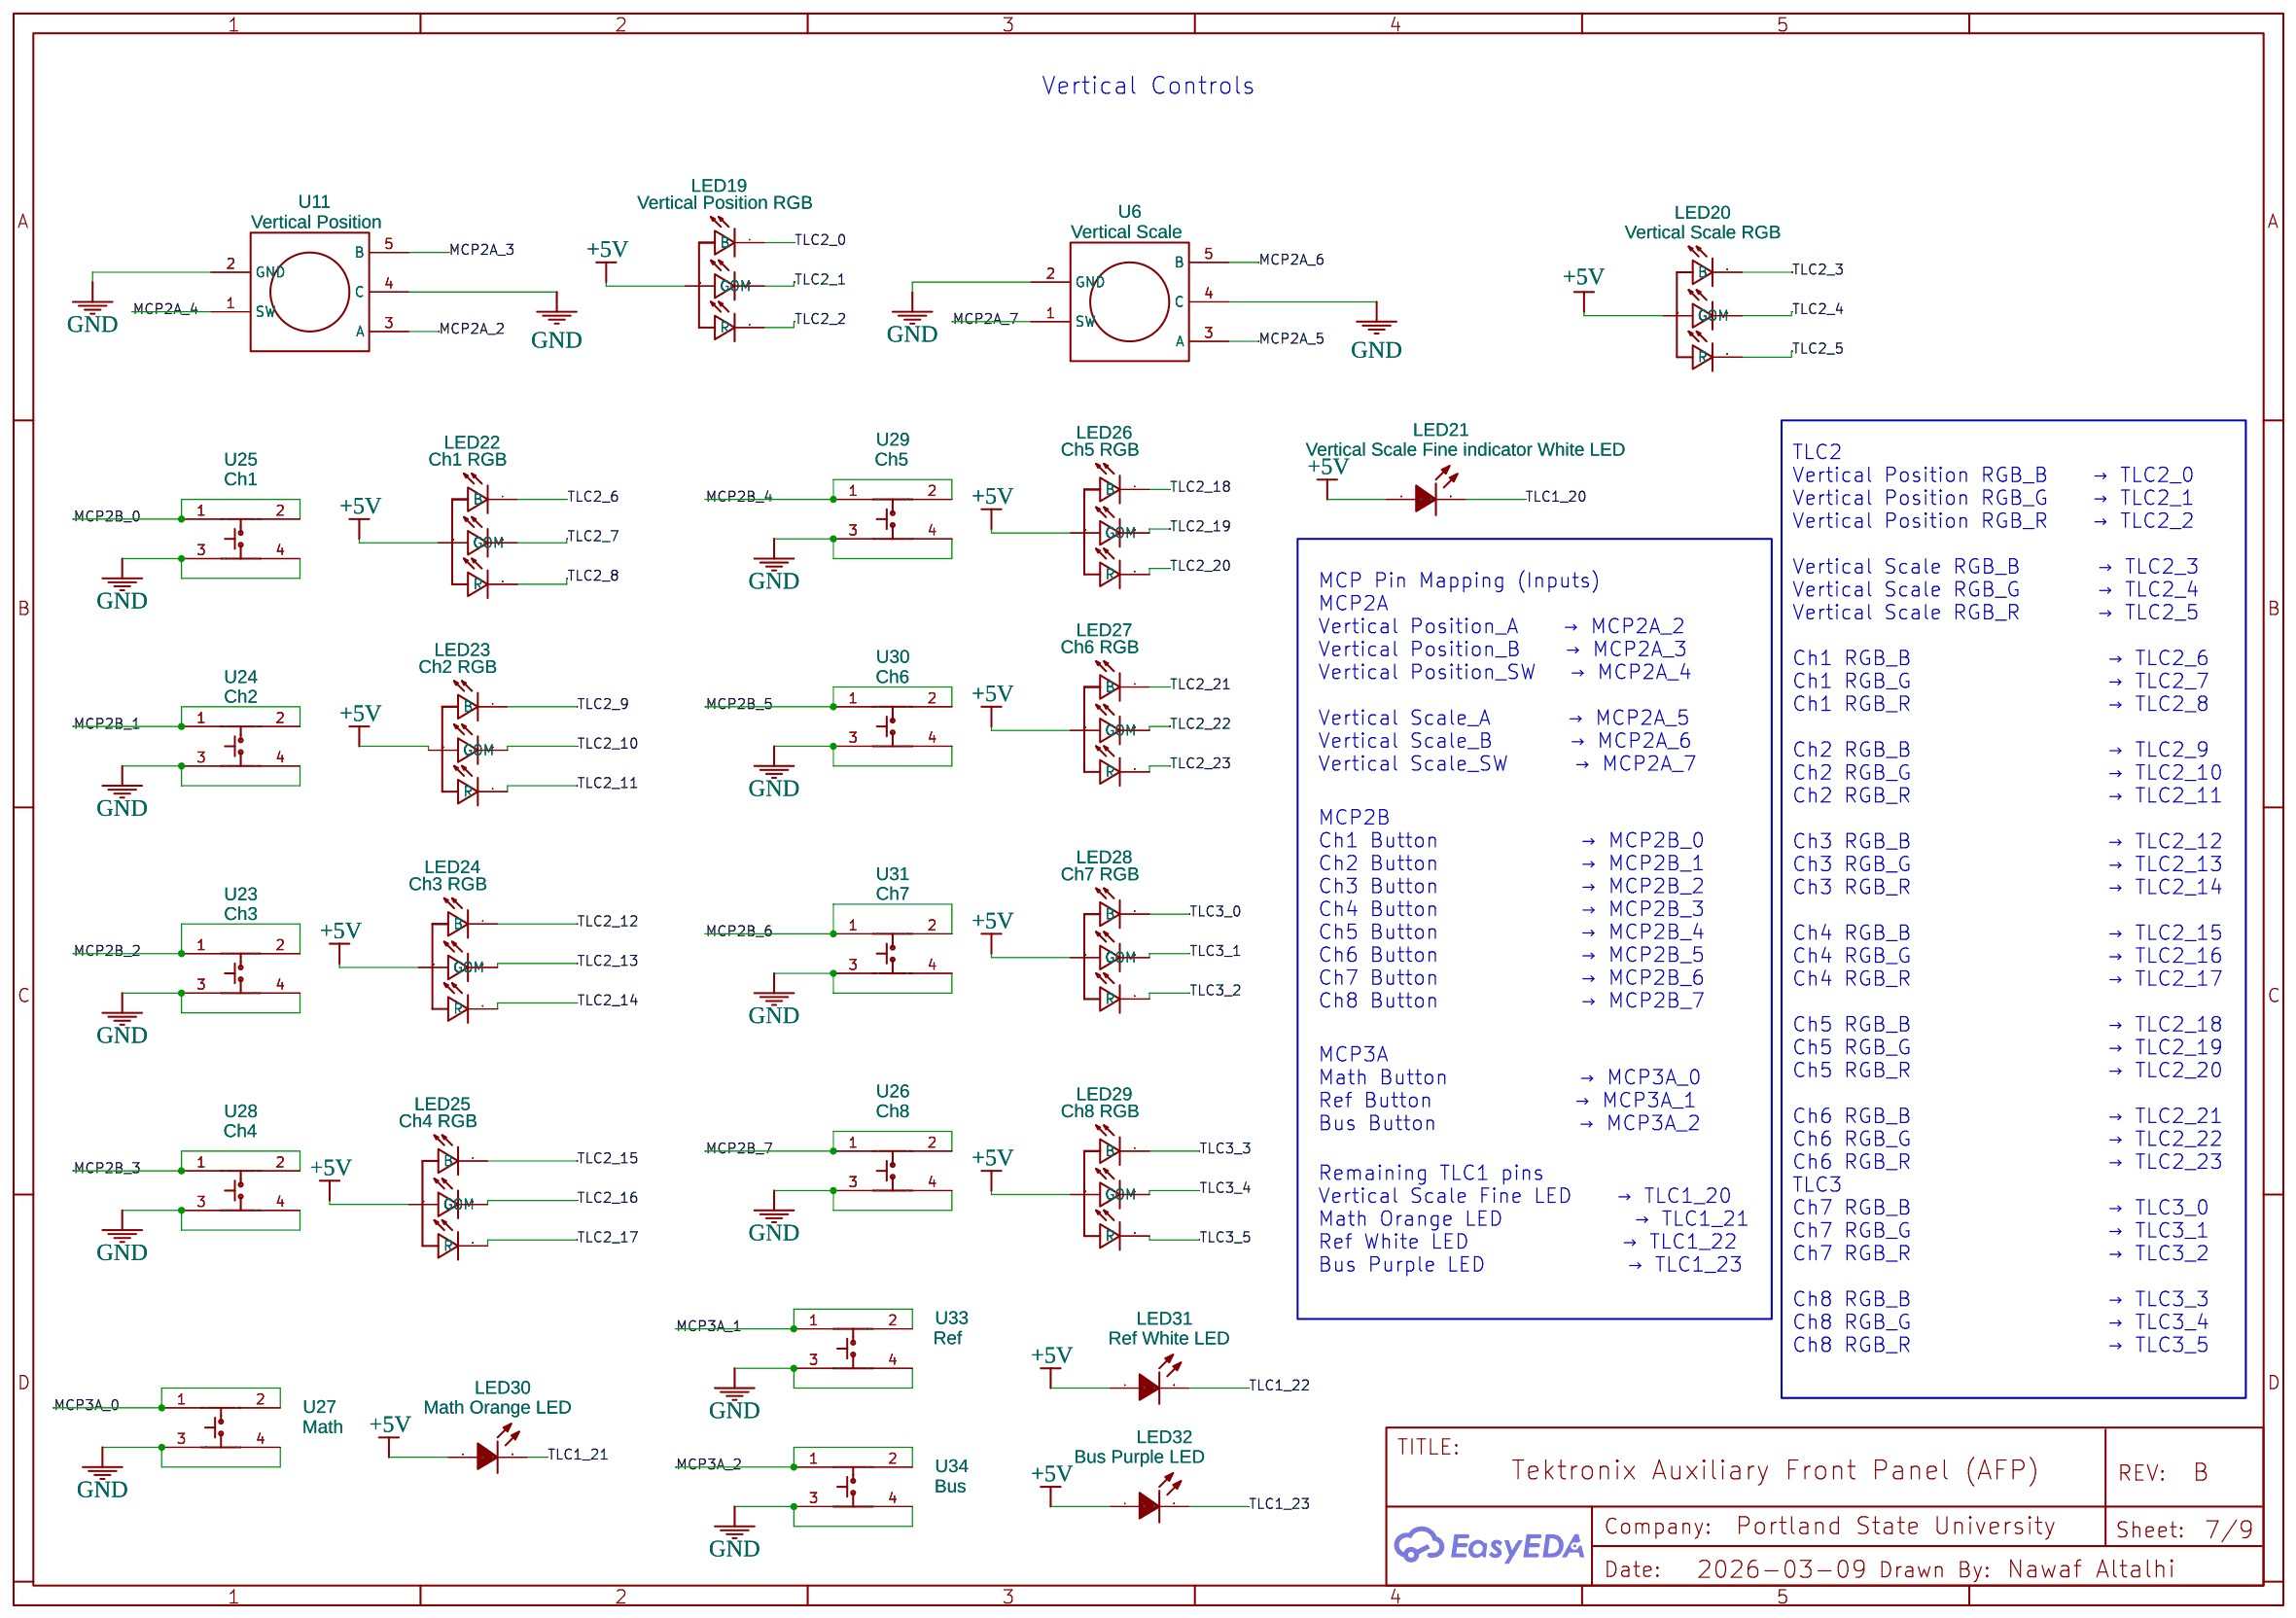
[diagram p6: VERTICAL]
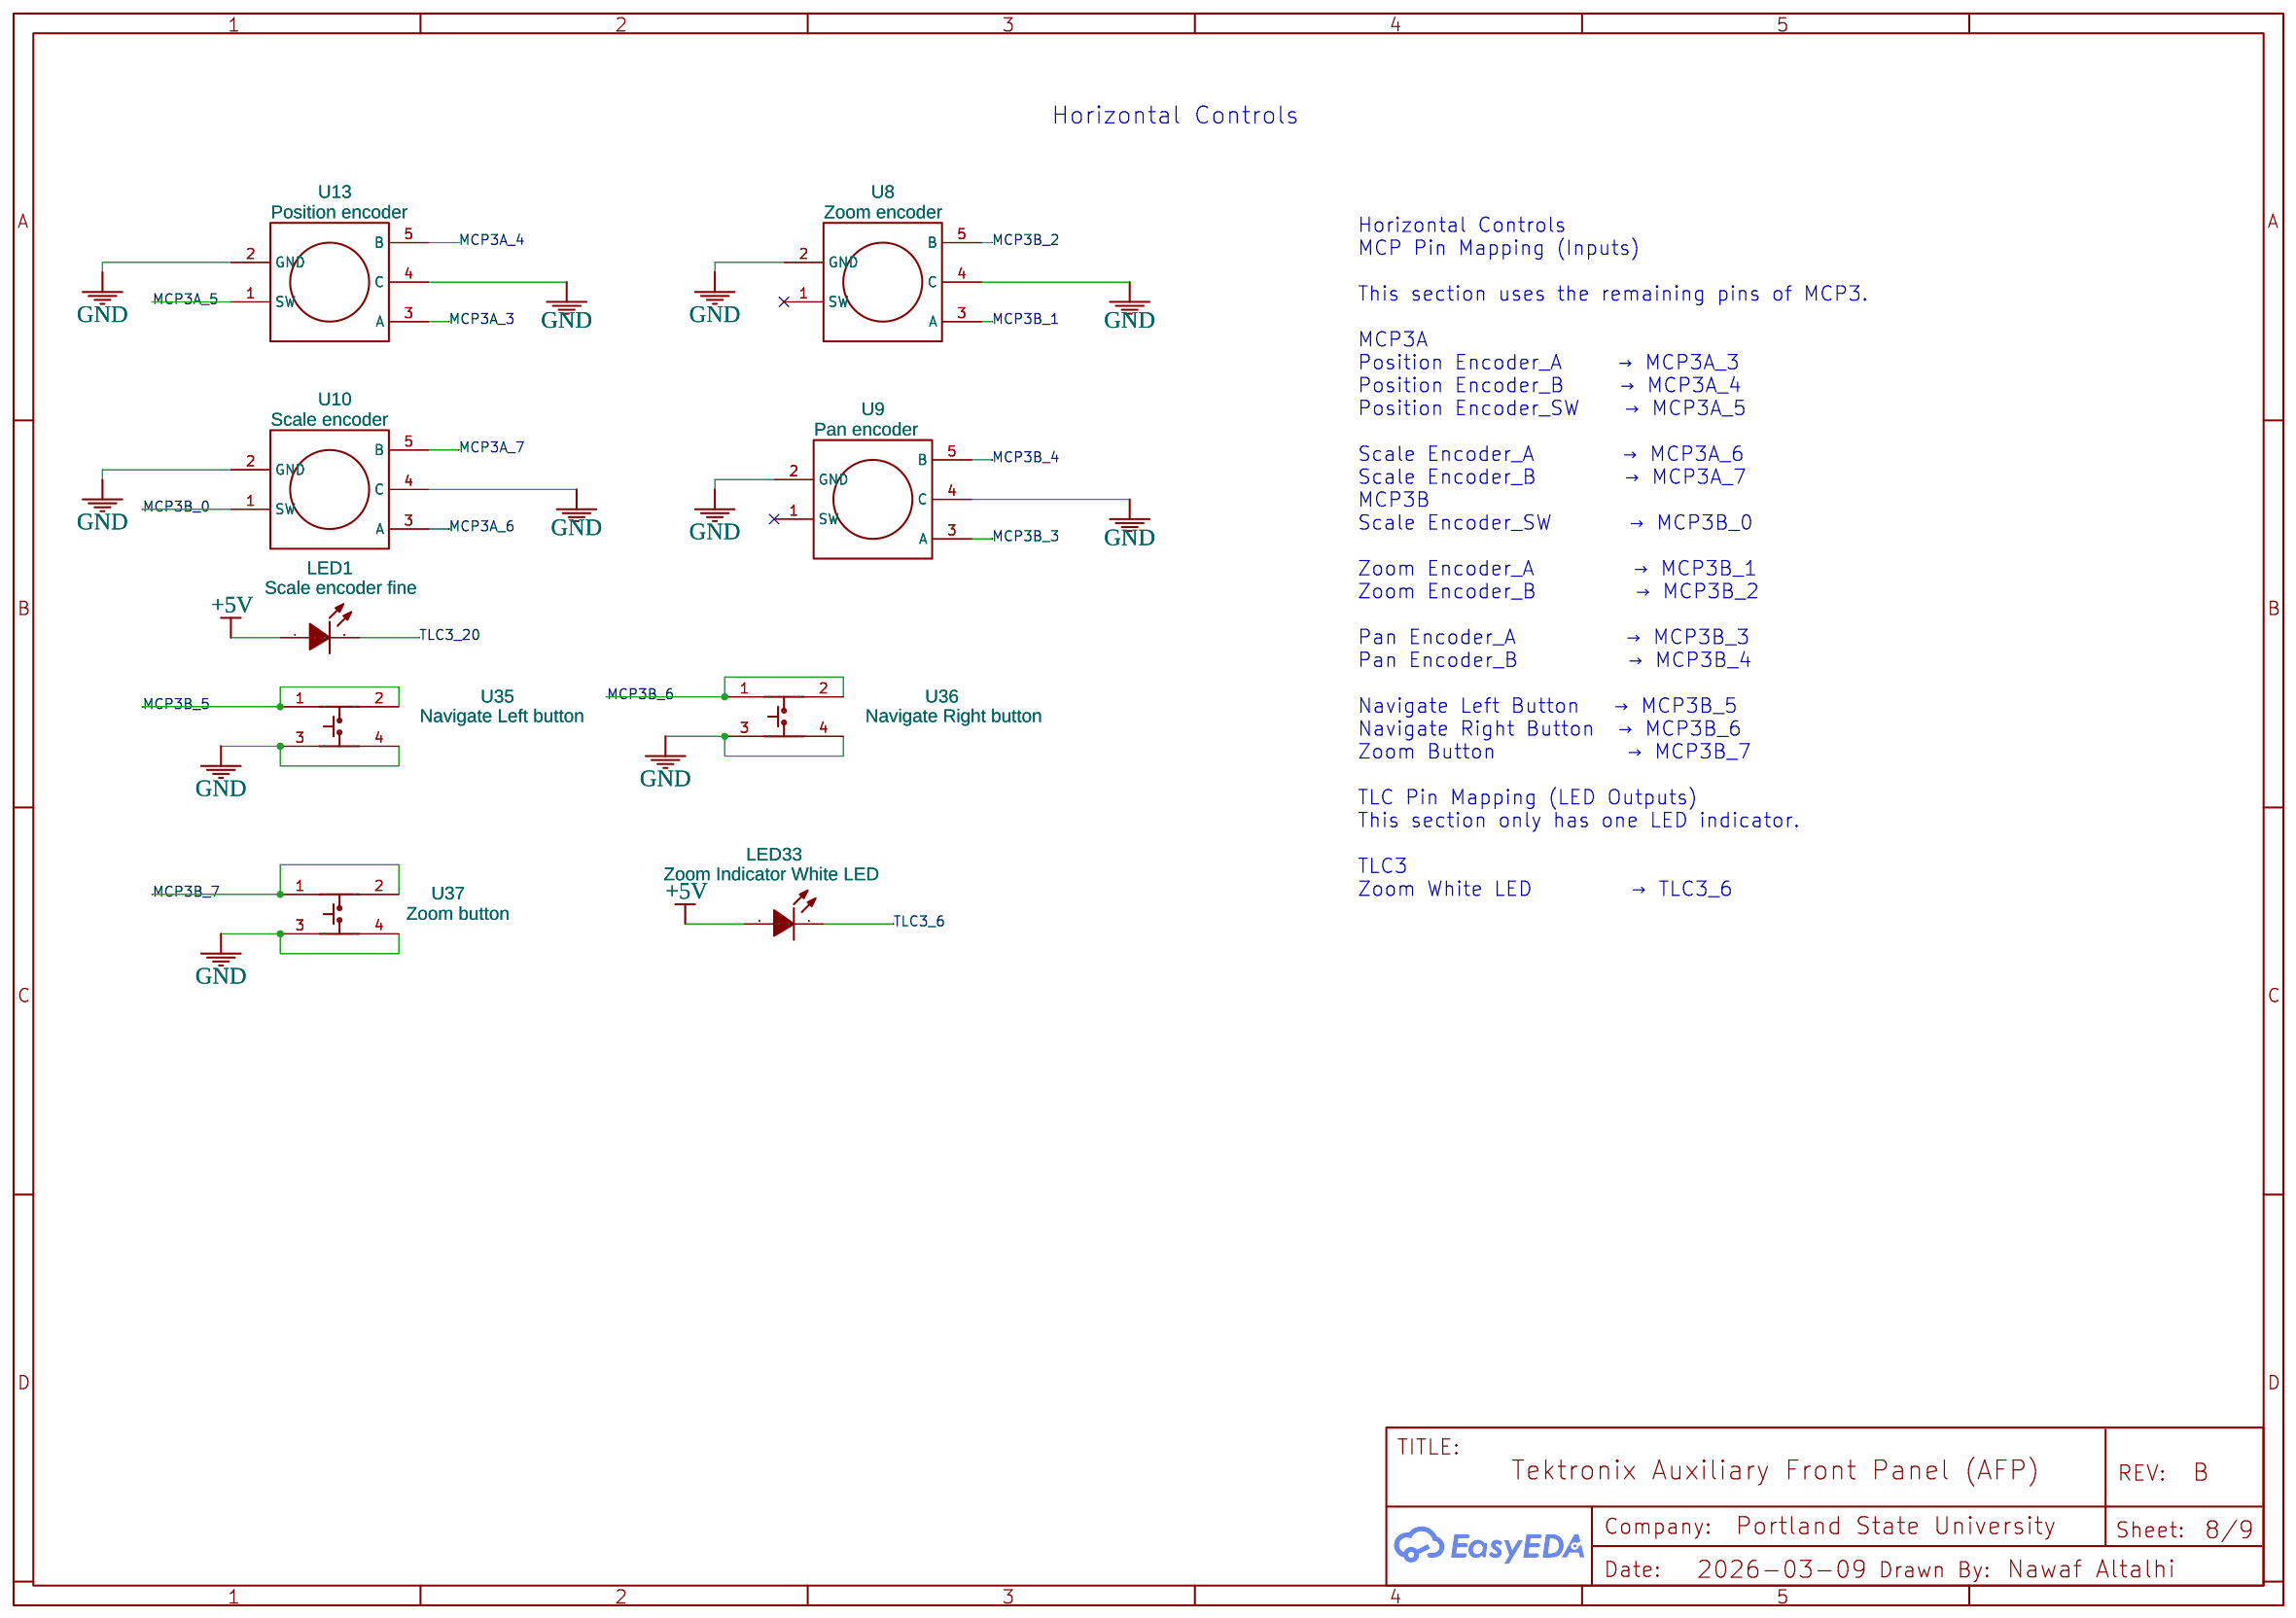
[diagram p7: HORIZONTAL]
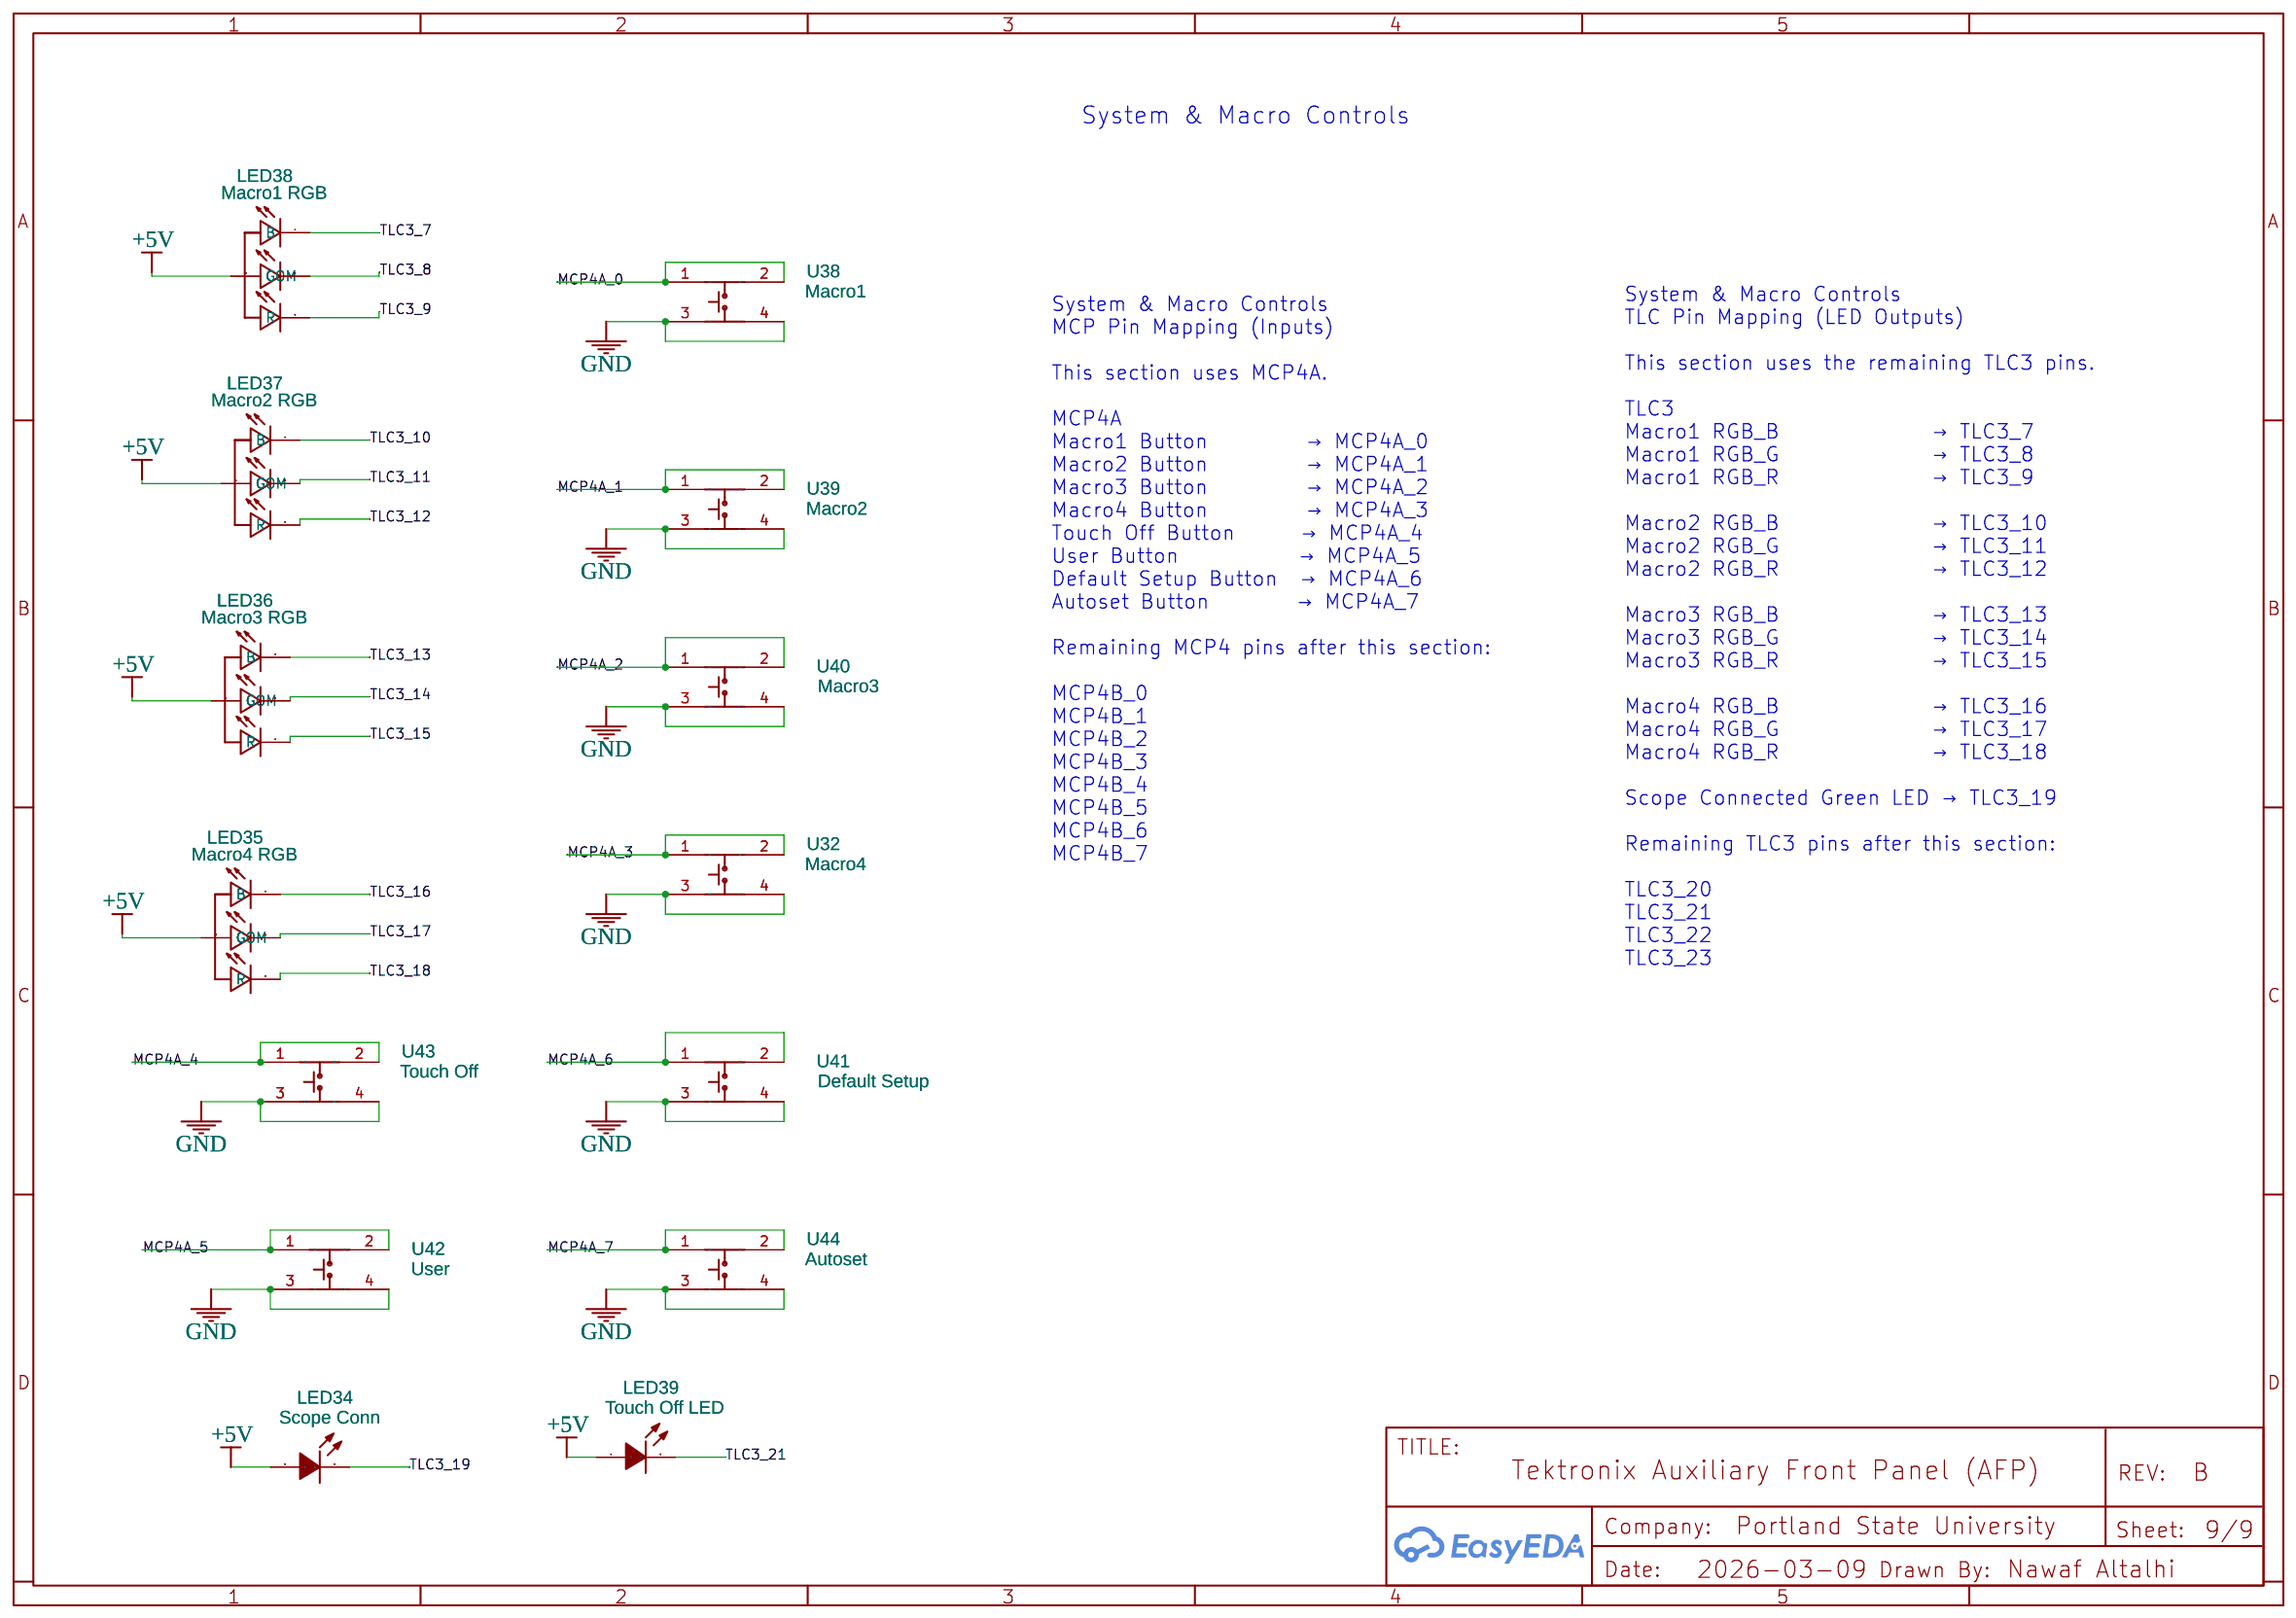
[diagram p8: Miscellaneous controls& Macro]

(export (version "E")
  (design (tool "Eeschema 10.0.6"))
  (components
    (comp (ref "C11") (value "0.1u") (libsource (lib "") (part "C_0603_US")))
    (comp (ref "C12")
      (value "DNP100u")
      (fields (field (name "Manufacturer Part") "EDT107M016A9HAA") (field (name "Manufacturer") "KEMET"))
      (libsource (lib "") (part "C_Tan_SMD_A_US"))
    )
    (comp (ref "C14") (value "DNP10u") (libsource (lib "") (part "C_0603_US")))
    (comp (ref "J1")
      (value "PJ-037AH")
      (fields (field (name "Manufacturer") "Same Sky (Formerly CUI Devices)"))
      (libsource (lib "") (part "PJ-037AH"))
    )
    (comp (ref "LED2")
      (value "LED-0603_G")
      (fields
        (field (name "Manufacturer Part") "19-217/GHC-YR1S2/3T")
        (field (name "Manufacturer") "EVERLIGHT(台湾亿光)")
      )
      (libsource (lib "") (part "LED-0603_G"))
    )
    (comp (ref "R15") (value "1k") (libsource (lib "") (part "R_0603_US")))
    (comp (ref "TP2") (value "TP_5V_Source") (libsource (lib "") (part "Connector_TestPoint")))
    (comp (ref "TP3") (value "GND") (libsource (lib "") (part "Connector_TestPoint")))
    (comp (ref "U45")
      (value "SLW-1276864-4A-D")
      (fields (field (name "Manufacturer") "Same Sky (Formerly CUI Devices)"))
      (libsource (lib "") (part "SLW-1276864-4A-D"))
    )
    (comp (ref "C2")
      (value "100u")
      (fields (field (name "Manufacturer Part") "EDT107M016A9HAA") (field (name "Manufacturer") "KEMET"))
      (libsource (lib "") (part "C_Tan_SMD_A_US"))
    )
    (comp (ref "C9") (value "0.1u") (libsource (lib "") (part "C_0603_US")))
    (comp (ref "R3") (value "4.7k") (libsource (lib "") (part "R_0603_US")))
    (comp (ref "R4") (value "4.7k") (libsource (lib "") (part "R_0603_US")))
    (comp (ref "R16") (value "Zero Ohm") (libsource (lib "") (part "R_0603_US_1")))
    (comp (ref "TP4") (value "I2CSCLTP") (libsource (lib "") (part "Connector_TestPoint")))
    (comp (ref "TP5") (value "I2CSDATP") (libsource (lib "") (part "Connector_TestPoint")))
    (comp (ref "TP6") (value "SINTP") (libsource (lib "") (part "Connector_TestPoint_1")))
    (comp (ref "TP7") (value "BLANKTP") (libsource (lib "") (part "Connector_TestPoint_1")))
    (comp (ref "TP8") (value "XLATTP") (libsource (lib "") (part "Connector_TestPoint_1")))
    (comp (ref "TP9") (value "TXTP") (libsource (lib "") (part "Connector_TestPoint_1")))
    (comp (ref "TP10") (value "RXTP") (libsource (lib "") (part "Connector_TestPoint_1")))
    (comp (ref "TP11") (value "SCLKTP") (libsource (lib "") (part "Connector_TestPoint_1")))
    (comp (ref "U5")
      (value "SC0915")
      (fields (field (name "Manufacturer") "Raspberry Pi"))
      (libsource (lib "") (part "SC0915"))
    )
    (comp (ref "C10")
      (value "100u")
      (fields (field (name "Manufacturer Part") "EDT107M016A9HAA") (field (name "Manufacturer") "KEMET"))
      (libsource (lib "") (part "C_Tan_SMD_A_US"))
    )
    (comp (ref "C13") (value "0.1u") (libsource (lib "") (part "C_0603_US")))
    (comp (ref "GPIO1")
      (value "2.54-2*20")
      (fields (field (name "Manufacturer") "ZHOURI(洲日)"))
      (libsource (lib "") (part "2.54-2*20"))
    )
    (comp (ref "R13") (value "0 Ω") (libsource (lib "") (part "R_0603_US")))
    (comp (ref "TP1") (value "TP_5V_PI") (libsource (lib "") (part "Connector_TestPoint")))
    (comp (ref "C5") (value "0.1u") (libsource (lib "") (part "C_0603_US")))
    (comp (ref "C6") (value "0.1u") (libsource (lib "") (part "C_0603_US")))
    (comp (ref "C7") (value "0.1u") (libsource (lib "") (part "C_0603_US")))
    (comp (ref "C8") (value "0.1u") (libsource (lib "") (part "C_0603_US")))
    (comp (ref "MCP1")
      (value "MCP23017T-E/SO")
      (fields (field (name "Manufacturer") "Microchip Technology"))
      (libsource (lib "") (part "MCP23017T-E/SO"))
    )
    (comp (ref "MCP2")
      (value "MCP23017T-E/SO")
      (fields (field (name "Manufacturer") "Microchip Technology"))
      (libsource (lib "") (part "MCP23017T-E/SO"))
    )
    (comp (ref "MCP3")
      (value "MCP23017T-E/SO")
      (fields (field (name "Manufacturer") "Microchip Technology"))
      (libsource (lib "") (part "MCP23017T-E/SO"))
    )
    (comp (ref "MCP4")
      (value "MCP23017T-E/SO")
      (fields (field (name "Manufacturer") "Microchip Technology"))
      (libsource (lib "") (part "MCP23017T-E/SO"))
    )
    (comp (ref "R9") (value "10k") (libsource (lib "") (part "R_0603_US")))
    (comp (ref "R10") (value "10k") (libsource (lib "") (part "R_0603_US")))
    (comp (ref "R11") (value "10k") (libsource (lib "") (part "R_0603_US")))
    (comp (ref "R12") (value "10k") (libsource (lib "") (part "R_0603_US")))
    (comp (ref "R14") (value "220") (libsource (lib "") (part "R_0603_US_1")))
    (comp (ref "R17") (value "220") (libsource (lib "") (part "R_0603_US_1")))
    (comp (ref "R18") (value "4.7k") (libsource (lib "") (part "R_0603_US_1")))
    (comp (ref "R19") (value "4.7k") (libsource (lib "") (part "R_0603_US_1")))
    (comp (ref "R20") (value "220") (libsource (lib "") (part "R_0603_US_1")))
    (comp (ref "R21") (value "4.7k") (libsource (lib "") (part "R_0603_US_1")))
    (comp (ref "R22") (value "4.7k") (libsource (lib "") (part "R_0603_US_1")))
    (comp (ref "R23") (value "220") (libsource (lib "") (part "R_0603_US_1")))
    (comp (ref "R24") (value "220") (libsource (lib "") (part "R_0603_US_1")))
    (comp (ref "R25") (value "220") (libsource (lib "") (part "R_0603_US_1")))
    (comp (ref "R26") (value "4.7k") (libsource (lib "") (part "R_0603_US_1")))
    (comp (ref "R27") (value "4.7k") (libsource (lib "") (part "R_0603_US_1")))
    (comp (ref "R28") (value "220") (libsource (lib "") (part "R_0603_US_1")))
    (comp (ref "R29") (value "220") (libsource (lib "") (part "R_0603_US_1")))
    (comp (ref "R30") (value "4.7k") (libsource (lib "") (part "R_0603_US_1")))
    (comp (ref "R31") (value "4.7k") (libsource (lib "") (part "R_0603_US_1")))
    (comp (ref "C1") (value "0.1u") (libsource (lib "") (part "C_0603_US")))
    (comp (ref "C3") (value "0.1u") (libsource (lib "") (part "C_0603_US")))
    (comp (ref "C4") (value "0.1u") (libsource (lib "") (part "C_0603_US")))
    (comp (ref "R1") (value "3.3k") (libsource (lib "") (part "R_0603_US")))
    (comp (ref "R2") (value "10k") (libsource (lib "") (part "R_0603_US_1")))
    (comp (ref "R5") (value "10k") (libsource (lib "") (part "R_0603_US_1")))
    (comp (ref "R6") (value "3.3k") (libsource (lib "") (part "R_0603_US")))
    (comp (ref "R7") (value "10k") (libsource (lib "") (part "R_0603_US_1")))
    (comp (ref "R8") (value "3.3k") (libsource (lib "") (part "R_0603_US")))
    (comp (ref "U1")
      (value "TLC5947DAPR, LED DRIVER")
      (fields
        (field (name "Manufacturer Part") "TLC5947DAPR")
        (field (name "Manufacturer") "Texas Instruments")
      )
      (libsource (lib "") (part "TLC5947DAPR, LED DRIVER"))
    )
    (comp (ref "U2")
      (value "TLC5947DAPR, LED DRIVER")
      (fields
        (field (name "Manufacturer Part") "TLC5947DAPR")
        (field (name "Manufacturer") "Texas Instruments")
      )
      (libsource (lib "") (part "TLC5947DAPR, LED DRIVER"))
    )
    (comp (ref "U3")
      (value "TLC5947DAPR, LED DRIVER")
      (fields
        (field (name "Manufacturer Part") "TLC5947DAPR")
        (field (name "Manufacturer") "Texas Instruments")
      )
      (libsource (lib "") (part "TLC5947DAPR, LED DRIVER"))
    )
    (comp (ref "LED3")
      (value "Single/Seq LED")
      (fields
        (field (name "Manufacturer Part") "19-217/GHC-YR1S2/3T")
        (field (name "Manufacturer") "EVERLIGHT(台湾亿光)")
      )
      (libsource (lib "") (part "LED-0603_G"))
    )
    (comp (ref "LED4")
      (value "Run/Stop RGB")
      (fields
        (field (name "Manufacturer Part") "AAA3528LSEEZGKQBKS")
        (field (name "Manufacturer") "Kingbright")
      )
      (libsource (lib "") (part "AAA3528LSEEZGKQBKS"))
    )
    (comp (ref "LED5")
      (value "High Res LED")
      (fields
        (field (name "Manufacturer Part") "19-217/GHC-YR1S2/3T")
        (field (name "Manufacturer") "EVERLIGHT(台湾亿光)")
      )
      (libsource (lib "") (part "LED-0603_G"))
    )
    (comp (ref "LED6")
      (value "Fast Acq LED")
      (fields
        (field (name "Manufacturer Part") "19-217/GHC-YR1S2/3T")
        (field (name "Manufacturer") "EVERLIGHT(台湾亿光)")
      )
      (libsource (lib "") (part "LED-0603_G"))
    )
    (comp (ref "LED7")
      (value "Cursors LED (White)")
      (fields
        (field (name "Manufacturer Part") "19-217/GHC-YR1S2/3T")
        (field (name "Manufacturer") "EVERLIGHT(台湾亿光)")
      )
      (libsource (lib "") (part "LED-0603_G"))
    )
    (comp (ref "LED8")
      (value "Encoder A LED (White)")
      (fields
        (field (name "Manufacturer Part") "19-217/GHC-YR1S2/3T")
        (field (name "Manufacturer") "EVERLIGHT(台湾亿光)")
      )
      (libsource (lib "") (part "LED-0603_G"))
    )
    (comp (ref "LED9")
      (value "Encoder A “Fine” LED (White)")
      (fields
        (field (name "Manufacturer Part") "19-217/GHC-YR1S2/3T")
        (field (name "Manufacturer") "EVERLIGHT(台湾亿光)")
      )
      (libsource (lib "") (part "LED-0603_G"))
    )
    (comp (ref "LED10")
      (value "Encoder B LED (White)")
      (fields
        (field (name "Manufacturer Part") "19-217/GHC-YR1S2/3T")
        (field (name "Manufacturer") "EVERLIGHT(台湾亿光)")
      )
      (libsource (lib "") (part "LED-0603_G"))
    )
    (comp (ref "LED11")
      (value "Encoder B “Fine” LED (White)")
      (fields
        (field (name "Manufacturer Part") "19-217/GHC-YR1S2/3T")
        (field (name "Manufacturer") "EVERLIGHT(台湾亿光)")
      )
      (libsource (lib "") (part "LED-0603_G"))
    )
    (comp (ref "LED12")
      (value "Force Ready LED (White)")
      (fields
        (field (name "Manufacturer Part") "19-217/GHC-YR1S2/3T")
        (field (name "Manufacturer") "EVERLIGHT(台湾亿光)")
      )
      (libsource (lib "") (part "LED-0603_G"))
    )
    (comp (ref "LED13")
      (value "Trig'd LED")
      (fields
        (field (name "Manufacturer Part") "19-217/GHC-YR1S2/3T")
        (field (name "Manufacturer") "EVERLIGHT(台湾亿光)")
      )
      (libsource (lib "") (part "LED-0603_G"))
    )
    (comp (ref "LED14")
      (value "Trigger Level RGB ring")
      (fields
        (field (name "Manufacturer Part") "AAA3528LSEEZGKQBKS")
        (field (name "Manufacturer") "Kingbright")
      )
      (libsource (lib "") (part "AAA3528LSEEZGKQBKS"))
    )
    (comp (ref "LED15")
      (value "Slope Up LED")
      (fields
        (field (name "Manufacturer Part") "19-217/GHC-YR1S2/3T")
        (field (name "Manufacturer") "EVERLIGHT(台湾亿光)")
      )
      (libsource (lib "") (part "LED-0603_G"))
    )
    (comp (ref "LED16")
      (value "Slope Down LED")
      (fields
        (field (name "Manufacturer Part") "19-217/GHC-YR1S2/3T")
        (field (name "Manufacturer") "EVERLIGHT(台湾亿光)")
      )
      (libsource (lib "") (part "LED-0603_G"))
    )
    (comp (ref "LED17")
      (value "Mode Auto LED")
      (fields
        (field (name "Manufacturer Part") "19-217/GHC-YR1S2/3T")
        (field (name "Manufacturer") "EVERLIGHT(台湾亿光)")
      )
      (libsource (lib "") (part "LED-0603_G"))
    )
    (comp (ref "LED18")
      (value "Mode Norm LED")
      (fields
        (field (name "Manufacturer Part") "19-217/GHC-YR1S2/3T")
        (field (name "Manufacturer") "EVERLIGHT(台湾亿光)")
      )
      (libsource (lib "") (part "LED-0603_G"))
    )
    (comp (ref "U4")
      (value "Single/Seq Button")
      (fields
        (field (name "Manufacturer Part") "SWITCH TACTILE SPST-NO 0.05A 12V")
        (field (name "Manufacturer") "E-Switch")
      )
      (libsource (lib "") (part "TL3305AF260QG"))
    )
    (comp (ref "U7")
      (value "Run/Stop Button")
      (fields
        (field (name "Manufacturer Part") "SWITCH TACTILE SPST-NO 0.05A 12V")
        (field (name "Manufacturer") "E-Switch")
      )
      (libsource (lib "") (part "TL3305AF260QG"))
    )
    (comp (ref "U12")
      (value "Clear Button")
      (fields
        (field (name "Manufacturer Part") "SWITCH TACTILE SPST-NO 0.05A 12V")
        (field (name "Manufacturer") "E-Switch")
      )
      (libsource (lib "") (part "TL3305AF260QG"))
    )
    (comp (ref "U14") (value "Cursor B") (libsource (lib "") (part "360 Degree Rotary Encoder")))
    (comp (ref "U15") (value "Cursor A") (libsource (lib "") (part "360 Degree Rotary Encoder")))
    (comp (ref "U16") (value "Level") (libsource (lib "") (part "360 Degree Rotary Encoder")))
    (comp (ref "U17")
      (value "High Res Button")
      (fields
        (field (name "Manufacturer Part") "SWITCH TACTILE SPST-NO 0.05A 12V")
        (field (name "Manufacturer") "E-Switch")
      )
      (libsource (lib "") (part "TL3305AF260QG"))
    )
    (comp (ref "U18")
      (value "Cursor Button")
      (fields
        (field (name "Manufacturer Part") "SWITCH TACTILE SPST-NO 0.05A 12V")
        (field (name "Manufacturer") "E-Switch")
      )
      (libsource (lib "") (part "TL3305AF260QG"))
    )
    (comp (ref "U19")
      (value "Fast Acq Button")
      (fields
        (field (name "Manufacturer Part") "SWITCH TACTILE SPST-NO 0.05A 12V")
        (field (name "Manufacturer") "E-Switch")
      )
      (libsource (lib "") (part "TL3305AF260QG"))
    )
    (comp (ref "U20")
      (value "Mode")
      (fields
        (field (name "Manufacturer Part") "SWITCH TACTILE SPST-NO 0.05A 12V")
        (field (name "Manufacturer") "E-Switch")
      )
      (libsource (lib "") (part "TL3305AF260QG"))
    )
    (comp (ref "U21")
      (value "Slope")
      (fields
        (field (name "Manufacturer Part") "SWITCH TACTILE SPST-NO 0.05A 12V")
        (field (name "Manufacturer") "E-Switch")
      )
      (libsource (lib "") (part "TL3305AF260QG"))
    )
    (comp (ref "U22")
      (value "Force Button")
      (fields
        (field (name "Manufacturer Part") "SWITCH TACTILE SPST-NO 0.05A 12V")
        (field (name "Manufacturer") "E-Switch")
      )
      (libsource (lib "") (part "TL3305AF260QG"))
    )
    (comp (ref "LED19")
      (value "Vertical Position RGB")
      (fields
        (field (name "Manufacturer Part") "HQ67-23A2ARGBC")
        (field (name "Manufacturer") "AAA3528LSEEZGKQBKS")
      )
      (libsource (lib "") (part "AAA3528LSEEZGKQBKS"))
    )
    (comp (ref "LED20")
      (value "Vertical Scale RGB")
      (fields
        (field (name "Manufacturer Part") "HQ67-23A2ARGBC")
        (field (name "Manufacturer") "AAA3528LSEEZGKQBKS")
      )
      (libsource (lib "") (part "AAA3528LSEEZGKQBKS"))
    )
    (comp (ref "LED21")
      (value "Vertical Scale Fine indicator White LED")
      (fields
        (field (name "Manufacturer Part") "19-217/GHC-YR1S2/3T")
        (field (name "Manufacturer") "EVERLIGHT(台湾亿光)")
      )
      (libsource (lib "") (part "LED-0603_G"))
    )
    (comp (ref "LED22")
      (value "Ch1 RGB")
      (fields
        (field (name "Manufacturer Part") "HQ67-23A2ARGBC")
        (field (name "Manufacturer") "AAA3528LSEEZGKQBKS")
      )
      (libsource (lib "") (part "AAA3528LSEEZGKQBKS"))
    )
    (comp (ref "LED23")
      (value "Ch2 RGB")
      (fields
        (field (name "Manufacturer Part") "HQ67-23A2ARGBC")
        (field (name "Manufacturer") "AAA3528LSEEZGKQBKS")
      )
      (libsource (lib "") (part "AAA3528LSEEZGKQBKS"))
    )
    (comp (ref "LED24")
      (value "Ch3 RGB")
      (fields
        (field (name "Manufacturer Part") "HQ67-23A2ARGBC")
        (field (name "Manufacturer") "AAA3528LSEEZGKQBKS")
      )
      (libsource (lib "") (part "AAA3528LSEEZGKQBKS"))
    )
    (comp (ref "LED25")
      (value "Ch4 RGB")
      (fields
        (field (name "Manufacturer Part") "HQ67-23A2ARGBC")
        (field (name "Manufacturer") "AAA3528LSEEZGKQBKS")
      )
      (libsource (lib "") (part "AAA3528LSEEZGKQBKS"))
    )
    (comp (ref "LED26")
      (value "Ch5 RGB")
      (fields
        (field (name "Manufacturer Part") "HQ67-23A2ARGBC")
        (field (name "Manufacturer") "AAA3528LSEEZGKQBKS")
      )
      (libsource (lib "") (part "AAA3528LSEEZGKQBKS"))
    )
    (comp (ref "LED27")
      (value "Ch6 RGB")
      (fields
        (field (name "Manufacturer Part") "HQ67-23A2ARGBC")
        (field (name "Manufacturer") "AAA3528LSEEZGKQBKS")
      )
      (libsource (lib "") (part "AAA3528LSEEZGKQBKS"))
    )
    (comp (ref "LED28")
      (value "Ch7 RGB")
      (fields
        (field (name "Manufacturer Part") "HQ67-23A2ARGBC")
        (field (name "Manufacturer") "AAA3528LSEEZGKQBKS")
      )
      (libsource (lib "") (part "AAA3528LSEEZGKQBKS"))
    )
    (comp (ref "LED29")
      (value "Ch8 RGB")
      (fields
        (field (name "Manufacturer Part") "HQ67-23A2ARGBC")
        (field (name "Manufacturer") "AAA3528LSEEZGKQBKS")
      )
      (libsource (lib "") (part "AAA3528LSEEZGKQBKS"))
    )
    (comp (ref "LED30")
      (value "Math Orange LED")
      (fields
        (field (name "Manufacturer Part") "19-217/GHC-YR1S2/3T")
        (field (name "Manufacturer") "EVERLIGHT(台湾亿光)")
      )
      (libsource (lib "") (part "LED-0603_G"))
    )
    (comp (ref "LED31")
      (value "Ref White LED")
      (fields
        (field (name "Manufacturer Part") "19-217/GHC-YR1S2/3T")
        (field (name "Manufacturer") "EVERLIGHT(台湾亿光)")
      )
      (libsource (lib "") (part "LED-0603_G"))
    )
    (comp (ref "LED32")
      (value "Bus Purple LED")
      (fields
        (field (name "Manufacturer Part") "19-217/GHC-YR1S2/3T")
        (field (name "Manufacturer") "EVERLIGHT(台湾亿光)")
      )
      (libsource (lib "") (part "LED-0603_G"))
    )
    (comp (ref "U6") (value "Vertical Scale") (libsource (lib "") (part "360 Degree Rotary Encoder")))
    (comp (ref "U11") (value "Vertical Position") (libsource (lib "") (part "360 Degree Rotary Encoder")))
    (comp (ref "U23")
      (value "Ch3")
      (fields
        (field (name "Manufacturer Part") "SWITCH TACTILE SPST-NO 0.05A 12V")
        (field (name "Manufacturer") "E-Switch")
      )
      (libsource (lib "") (part "TL3305AF260QG"))
    )
    (comp (ref "U24")
      (value "Ch2")
      (fields
        (field (name "Manufacturer Part") "SWITCH TACTILE SPST-NO 0.05A 12V")
        (field (name "Manufacturer") "E-Switch")
      )
      (libsource (lib "") (part "TL3305AF260QG"))
    )
    (comp (ref "U25")
      (value "Ch1")
      (fields
        (field (name "Manufacturer Part") "SWITCH TACTILE SPST-NO 0.05A 12V")
        (field (name "Manufacturer") "E-Switch")
      )
      (libsource (lib "") (part "TL3305AF260QG"))
    )
    (comp (ref "U26")
      (value "Ch8")
      (fields
        (field (name "Manufacturer Part") "SWITCH TACTILE SPST-NO 0.05A 12V")
        (field (name "Manufacturer") "E-Switch")
      )
      (libsource (lib "") (part "TL3305AF260QG"))
    )
    (comp (ref "U27")
      (value "Math")
      (fields
        (field (name "Manufacturer Part") "SWITCH TACTILE SPST-NO 0.05A 12V")
        (field (name "Manufacturer") "E-Switch")
      )
      (libsource (lib "") (part "TL3305AF260QG"))
    )
    (comp (ref "U28")
      (value "Ch4")
      (fields
        (field (name "Manufacturer Part") "SWITCH TACTILE SPST-NO 0.05A 12V")
        (field (name "Manufacturer") "E-Switch")
      )
      (libsource (lib "") (part "TL3305AF260QG"))
    )
    (comp (ref "U29")
      (value "Ch5")
      (fields
        (field (name "Manufacturer Part") "SWITCH TACTILE SPST-NO 0.05A 12V")
        (field (name "Manufacturer") "E-Switch")
      )
      (libsource (lib "") (part "TL3305AF260QG"))
    )
    (comp (ref "U30")
      (value "Ch6")
      (fields
        (field (name "Manufacturer Part") "SWITCH TACTILE SPST-NO 0.05A 12V")
        (field (name "Manufacturer") "E-Switch")
      )
      (libsource (lib "") (part "TL3305AF260QG"))
    )
    (comp (ref "U31")
      (value "Ch7")
      (fields
        (field (name "Manufacturer Part") "SWITCH TACTILE SPST-NO 0.05A 12V")
        (field (name "Manufacturer") "E-Switch")
      )
      (libsource (lib "") (part "TL3305AF260QG"))
    )
    (comp (ref "U33")
      (value "Ref")
      (fields
        (field (name "Manufacturer Part") "SWITCH TACTILE SPST-NO 0.05A 12V")
        (field (name "Manufacturer") "E-Switch")
      )
      (libsource (lib "") (part "TL3305AF260QG"))
    )
    (comp (ref "U34")
      (value "Bus")
      (fields
        (field (name "Manufacturer Part") "SWITCH TACTILE SPST-NO 0.05A 12V")
        (field (name "Manufacturer") "E-Switch")
      )
      (libsource (lib "") (part "TL3305AF260QG"))
    )
    (comp (ref "LED1")
      (value "Scale encoder fine")
      (fields
        (field (name "Manufacturer Part") "19-217/GHC-YR1S2/3T")
        (field (name "Manufacturer") "EVERLIGHT(台湾亿光)")
      )
      (libsource (lib "") (part "LED-0603_G"))
    )
    (comp (ref "LED33")
      (value "Zoom Indicator White LED")
      (fields
        (field (name "Manufacturer Part") "19-217/GHC-YR1S2/3T")
        (field (name "Manufacturer") "EVERLIGHT(台湾亿光)")
      )
      (libsource (lib "") (part "LED-0603_G"))
    )
    (comp (ref "U8") (value "Zoom encoder") (libsource (lib "") (part "360 Degree Rotary Encoder")))
    (comp (ref "U9") (value "Pan encoder") (libsource (lib "") (part "360 Degree Rotary Encoder")))
    (comp (ref "U10") (value "Scale encoder") (libsource (lib "") (part "360 Degree Rotary Encoder")))
    (comp (ref "U13") (value "Position encoder") (libsource (lib "") (part "360 Degree Rotary Encoder")))
    (comp (ref "U35")
      (value "Navigate Left button")
      (fields
        (field (name "Manufacturer Part") "SWITCH TACTILE SPST-NO 0.05A 12V")
        (field (name "Manufacturer") "E-Switch")
      )
      (libsource (lib "") (part "TL3305AF260QG"))
    )
    (comp (ref "U36")
      (value "Navigate Right button")
      (fields
        (field (name "Manufacturer Part") "SWITCH TACTILE SPST-NO 0.05A 12V")
        (field (name "Manufacturer") "E-Switch")
      )
      (libsource (lib "") (part "TL3305AF260QG"))
    )
    (comp (ref "U37")
      (value "Zoom button")
      (fields
        (field (name "Manufacturer Part") "SWITCH TACTILE SPST-NO 0.05A 12V")
        (field (name "Manufacturer") "E-Switch")
      )
      (libsource (lib "") (part "TL3305AF260QG"))
    )
    (comp (ref "LED34")
      (value "Scope Conn")
      (fields
        (field (name "Manufacturer Part") "333-2SYGD/S530-E2")
        (field (name "Manufacturer") "EVERLIGHT(台湾亿光)")
      )
      (libsource (lib "") (part "LED-TH-5mm_G"))
    )
    (comp (ref "LED35")
      (value "Macro4 RGB")
      (fields
        (field (name "Manufacturer Part") "HQ67-23A2ARGBC")
        (field (name "Manufacturer") "AAA3528LSEEZGKQBKS")
      )
      (libsource (lib "") (part "AAA3528LSEEZGKQBKS"))
    )
    (comp (ref "LED36")
      (value "Macro3 RGB")
      (fields
        (field (name "Manufacturer Part") "HQ67-23A2ARGBC")
        (field (name "Manufacturer") "AAA3528LSEEZGKQBKS")
      )
      (libsource (lib "") (part "AAA3528LSEEZGKQBKS"))
    )
    (comp (ref "LED37")
      (value "Macro2 RGB")
      (fields
        (field (name "Manufacturer Part") "HQ67-23A2ARGBC")
        (field (name "Manufacturer") "AAA3528LSEEZGKQBKS")
      )
      (libsource (lib "") (part "AAA3528LSEEZGKQBKS"))
    )
    (comp (ref "LED38")
      (value "Macro1 RGB")
      (fields
        (field (name "Manufacturer Part") "HQ67-23A2ARGBC")
        (field (name "Manufacturer") "AAA3528LSEEZGKQBKS")
      )
      (libsource (lib "") (part "AAA3528LSEEZGKQBKS"))
    )
    (comp (ref "LED39")
      (value "Touch Off LED")
      (fields
        (field (name "Manufacturer Part") "333-2SYGD/S530-E2")
        (field (name "Manufacturer") "EVERLIGHT(台湾亿光)")
      )
      (libsource (lib "") (part "LED-TH-5mm_G"))
    )
    (comp (ref "U32")
      (value "Macro4")
      (fields
        (field (name "Manufacturer Part") "SWITCH TACTILE SPST-NO 0.05A 12V")
        (field (name "Manufacturer") "E-Switch")
      )
      (libsource (lib "") (part "TL3305AF260QG"))
    )
    (comp (ref "U38")
      (value "Macro1")
      (fields
        (field (name "Manufacturer Part") "SWITCH TACTILE SPST-NO 0.05A 12V")
        (field (name "Manufacturer") "E-Switch")
      )
      (libsource (lib "") (part "TL3305AF260QG"))
    )
    (comp (ref "U39")
      (value "Macro2")
      (fields
        (field (name "Manufacturer Part") "SWITCH TACTILE SPST-NO 0.05A 12V")
        (field (name "Manufacturer") "E-Switch")
      )
      (libsource (lib "") (part "TL3305AF260QG"))
    )
    (comp (ref "U40")
      (value "Macro3")
      (fields
        (field (name "Manufacturer Part") "SWITCH TACTILE SPST-NO 0.05A 12V")
        (field (name "Manufacturer") "E-Switch")
      )
      (libsource (lib "") (part "TL3305AF260QG"))
    )
    (comp (ref "U41")
      (value "Default Setup")
      (fields
        (field (name "Manufacturer Part") "SWITCH TACTILE SPST-NO 0.05A 12V")
        (field (name "Manufacturer") "E-Switch")
      )
      (libsource (lib "") (part "TL3305AF260QG"))
    )
    (comp (ref "U42")
      (value "User")
      (fields
        (field (name "Manufacturer Part") "SWITCH TACTILE SPST-NO 0.05A 12V")
        (field (name "Manufacturer") "E-Switch")
      )
      (libsource (lib "") (part "TL3305AF260QG"))
    )
    (comp (ref "U43")
      (value "Touch Off")
      (fields
        (field (name "Manufacturer Part") "SWITCH TACTILE SPST-NO 0.05A 12V")
        (field (name "Manufacturer") "E-Switch")
      )
      (libsource (lib "") (part "TL3305AF260QG"))
    )
    (comp (ref "U44")
      (value "Autoset")
      (fields
        (field (name "Manufacturer Part") "SWITCH TACTILE SPST-NO 0.05A 12V")
        (field (name "Manufacturer") "E-Switch")
      )
      (libsource (lib "") (part "TL3305AF260QG"))
    )
  )
  (nets
    (net (code "1") (name "+3.3V") (class "Default")
      (node (ref "C1") (pin "2") (pinfunction "2_2") (pintype "unspecified"))
      (node (ref "C3") (pin "2") (pinfunction "2_2") (pintype "unspecified"))
      (node (ref "C4") (pin "2") (pinfunction "2_2") (pintype "unspecified"))
      (node (ref "C5") (pin "2") (pinfunction "2_2") (pintype "unspecified"))
      (node (ref "C6") (pin "2") (pinfunction "2_2") (pintype "unspecified"))
      (node (ref "C7") (pin "2") (pinfunction "2_2") (pintype "unspecified"))
      (node (ref "C8") (pin "2") (pinfunction "2_2") (pintype "unspecified"))
      (node (ref "MCP1") (pin "15") (pinfunction "A0_15") (pintype "unspecified"))
      (node (ref "MCP1") (pin "9") (pinfunction "VDD_9") (pintype "unspecified"))
      (node (ref "MCP2") (pin "9") (pinfunction "VDD_9") (pintype "unspecified"))
      (node (ref "MCP3") (pin "16") (pinfunction "A1_16") (pintype "unspecified"))
      (node (ref "MCP3") (pin "9") (pinfunction "VDD_9") (pintype "unspecified"))
      (node (ref "MCP4") (pin "15") (pinfunction "A0_15") (pintype "unspecified"))
      (node (ref "MCP4") (pin "16") (pinfunction "A1_16") (pintype "unspecified"))
      (node (ref "MCP4") (pin "9") (pinfunction "VDD_9") (pintype "unspecified"))
      (node (ref "R10") (pin "2") (pinfunction "2_2") (pintype "unspecified"))
      (node (ref "R11") (pin "2") (pinfunction "2_2") (pintype "unspecified"))
      (node (ref "R12") (pin "2") (pinfunction "2_2") (pintype "unspecified"))
      (node (ref "R18") (pin "2") (pinfunction "2_2") (pintype "unspecified"))
      (node (ref "R19") (pin "2") (pinfunction "2_2") (pintype "unspecified"))
      (node (ref "R21") (pin "2") (pinfunction "2_2") (pintype "unspecified"))
      (node (ref "R22") (pin "2") (pinfunction "2_2") (pintype "unspecified"))
      (node (ref "R26") (pin "2") (pinfunction "2_2") (pintype "unspecified"))
      (node (ref "R27") (pin "2") (pinfunction "2_2") (pintype "unspecified"))
      (node (ref "R3") (pin "2") (pinfunction "2_2") (pintype "unspecified"))
      (node (ref "R30") (pin "2") (pinfunction "2_2") (pintype "unspecified"))
      (node (ref "R31") (pin "2") (pinfunction "2_2") (pintype "unspecified"))
      (node (ref "R4") (pin "2") (pinfunction "2_2") (pintype "unspecified"))
      (node (ref "R9") (pin "2") (pinfunction "2_2") (pintype "unspecified"))
      (node (ref "U1") (pin "32") (pinfunction "VCC_32") (pintype "unspecified"))
      (node (ref "U2") (pin "32") (pinfunction "VCC_32") (pintype "unspecified"))
      (node (ref "U3") (pin "32") (pinfunction "VCC_32") (pintype "unspecified"))
      (node (ref "U5") (pin "36") (pinfunction "3V3OUT_36") (pintype "output"))
    )
    (net (code "2") (name "+5V") (class "Default")
      (node (ref "C11") (pin "2") (pinfunction "2_2") (pintype "unspecified"))
      (node (ref "C12") (pin "1") (pinfunction "1_1") (pintype "unspecified"))
      (node (ref "C14") (pin "2") (pinfunction "2_2") (pintype "unspecified"))
      (node (ref "C2") (pin "1") (pinfunction "1_1") (pintype "unspecified"))
      (node (ref "C9") (pin "2") (pinfunction "2_2") (pintype "unspecified"))
      (node (ref "LED1") (pin "1") (pinfunction "1_1") (pintype "unspecified"))
      (node (ref "LED10") (pin "1") (pinfunction "1_1") (pintype "unspecified"))
      (node (ref "LED11") (pin "1") (pinfunction "1_1") (pintype "unspecified"))
      (node (ref "LED12") (pin "1") (pinfunction "1_1") (pintype "unspecified"))
      (node (ref "LED13") (pin "1") (pinfunction "1_1") (pintype "unspecified"))
      (node (ref "LED14") (pin "2") (pinfunction "COM_2") (pintype "unspecified"))
      (node (ref "LED15") (pin "1") (pinfunction "1_1") (pintype "unspecified"))
      (node (ref "LED16") (pin "1") (pinfunction "1_1") (pintype "unspecified"))
      (node (ref "LED17") (pin "1") (pinfunction "1_1") (pintype "unspecified"))
      (node (ref "LED18") (pin "1") (pinfunction "1_1") (pintype "unspecified"))
      (node (ref "LED19") (pin "2") (pinfunction "COM_2") (pintype "unspecified"))
      (node (ref "LED20") (pin "2") (pinfunction "COM_2") (pintype "unspecified"))
      (node (ref "LED21") (pin "1") (pinfunction "1_1") (pintype "unspecified"))
      (node (ref "LED22") (pin "2") (pinfunction "COM_2") (pintype "unspecified"))
      (node (ref "LED23") (pin "2") (pinfunction "COM_2") (pintype "unspecified"))
      (node (ref "LED24") (pin "2") (pinfunction "COM_2") (pintype "unspecified"))
      (node (ref "LED25") (pin "2") (pinfunction "COM_2") (pintype "unspecified"))
      (node (ref "LED26") (pin "2") (pinfunction "COM_2") (pintype "unspecified"))
      (node (ref "LED27") (pin "2") (pinfunction "COM_2") (pintype "unspecified"))
      (node (ref "LED28") (pin "2") (pinfunction "COM_2") (pintype "unspecified"))
      (node (ref "LED29") (pin "2") (pinfunction "COM_2") (pintype "unspecified"))
      (node (ref "LED3") (pin "1") (pinfunction "1_1") (pintype "unspecified"))
      (node (ref "LED30") (pin "1") (pinfunction "1_1") (pintype "unspecified"))
      (node (ref "LED31") (pin "1") (pinfunction "1_1") (pintype "unspecified"))
      (node (ref "LED32") (pin "1") (pinfunction "1_1") (pintype "unspecified"))
      (node (ref "LED33") (pin "1") (pinfunction "1_1") (pintype "unspecified"))
      (node (ref "LED34") (pin "1") (pinfunction "1_1") (pintype "unspecified"))
      (node (ref "LED35") (pin "2") (pinfunction "COM_2") (pintype "unspecified"))
      (node (ref "LED36") (pin "2") (pinfunction "COM_2") (pintype "unspecified"))
      (node (ref "LED37") (pin "2") (pinfunction "COM_2") (pintype "unspecified"))
      (node (ref "LED38") (pin "2") (pinfunction "COM_2") (pintype "unspecified"))
      (node (ref "LED39") (pin "1") (pinfunction "1_1") (pintype "unspecified"))
      (node (ref "LED4") (pin "2") (pinfunction "COM_2") (pintype "unspecified"))
      (node (ref "LED5") (pin "1") (pinfunction "1_1") (pintype "unspecified"))
      (node (ref "LED6") (pin "1") (pinfunction "1_1") (pintype "unspecified"))
      (node (ref "LED7") (pin "1") (pinfunction "1_1") (pintype "unspecified"))
      (node (ref "LED8") (pin "1") (pinfunction "1_1") (pintype "unspecified"))
      (node (ref "LED9") (pin "1") (pinfunction "1_1") (pintype "unspecified"))
      (node (ref "R13") (pin "2") (pinfunction "2_2") (pintype "unspecified"))
      (node (ref "R15") (pin "2") (pinfunction "2_2") (pintype "unspecified"))
      (node (ref "R16") (pin "2") (pinfunction "2_2") (pintype "unspecified"))
      (node (ref "TP2") (pin "1") (pinfunction "1_1") (pintype "unspecified"))
      (node (ref "U45") (pin "2") (pinfunction "2_2") (pintype "unspecified"))
    )
    (net (code "3") (name "GND") (class "Default")
      (node (ref "C1") (pin "1") (pinfunction "1_1") (pintype "unspecified"))
      (node (ref "C10") (pin "2") (pinfunction "2_2") (pintype "unspecified"))
      (node (ref "C11") (pin "1") (pinfunction "1_1") (pintype "unspecified"))
      (node (ref "C12") (pin "2") (pinfunction "2_2") (pintype "unspecified"))
      (node (ref "C13") (pin "1") (pinfunction "1_1") (pintype "unspecified"))
      (node (ref "C14") (pin "1") (pinfunction "1_1") (pintype "unspecified"))
      (node (ref "C2") (pin "2") (pinfunction "2_2") (pintype "unspecified"))
      (node (ref "C3") (pin "1") (pinfunction "1_1") (pintype "unspecified"))
      (node (ref "C4") (pin "1") (pinfunction "1_1") (pintype "unspecified"))
      (node (ref "C5") (pin "1") (pinfunction "1_1") (pintype "unspecified"))
      (node (ref "C6") (pin "1") (pinfunction "1_1") (pintype "unspecified"))
      (node (ref "C7") (pin "1") (pinfunction "1_1") (pintype "unspecified"))
      (node (ref "C8") (pin "1") (pinfunction "1_1") (pintype "unspecified"))
      (node (ref "C9") (pin "1") (pinfunction "1_1") (pintype "unspecified"))
      (node (ref "GPIO1") (pin "14") (pinfunction "GND_14") (pintype "unspecified"))
      (node (ref "GPIO1") (pin "20") (pinfunction "GND_20") (pintype "unspecified"))
      (node (ref "GPIO1") (pin "25") (pinfunction "GND_25") (pintype "unspecified"))
      (node (ref "GPIO1") (pin "30") (pinfunction "GND_30") (pintype "unspecified"))
      (node (ref "GPIO1") (pin "34") (pinfunction "GND_34") (pintype "unspecified"))
      (node (ref "GPIO1") (pin "39") (pinfunction "GND_39") (pintype "unspecified"))
      (node (ref "GPIO1") (pin "6") (pinfunction "GND_6") (pintype "unspecified"))
      (node (ref "GPIO1") (pin "9") (pinfunction "GND_9") (pintype "unspecified"))
      (node (ref "J1") (pin "2") (pinfunction "2_2") (pintype "bidirectional"))
      (node (ref "LED2") (pin "2") (pinfunction "2_2") (pintype "unspecified"))
      (node (ref "MCP1") (pin "10") (pinfunction "VSS_10") (pintype "unspecified"))
      (node (ref "MCP1") (pin "16") (pinfunction "A1_16") (pintype "unspecified"))
      (node (ref "MCP1") (pin "17") (pinfunction "A2_17") (pintype "unspecified"))
      (node (ref "MCP2") (pin "10") (pinfunction "VSS_10") (pintype "unspecified"))
      (node (ref "MCP2") (pin "15") (pinfunction "A0_15") (pintype "unspecified"))
      (node (ref "MCP2") (pin "16") (pinfunction "A1_16") (pintype "unspecified"))
      (node (ref "MCP2") (pin "17") (pinfunction "A2_17") (pintype "unspecified"))
      (node (ref "MCP3") (pin "10") (pinfunction "VSS_10") (pintype "unspecified"))
      (node (ref "MCP3") (pin "15") (pinfunction "A0_15") (pintype "unspecified"))
      (node (ref "MCP3") (pin "17") (pinfunction "A2_17") (pintype "unspecified"))
      (node (ref "MCP4") (pin "10") (pinfunction "VSS_10") (pintype "unspecified"))
      (node (ref "MCP4") (pin "17") (pinfunction "A2_17") (pintype "unspecified"))
      (node (ref "R1") (pin "2") (pinfunction "2_2") (pintype "unspecified"))
      (node (ref "R2") (pin "1") (pinfunction "1_1") (pintype "unspecified"))
      (node (ref "R5") (pin "1") (pinfunction "1_1") (pintype "unspecified"))
      (node (ref "R6") (pin "2") (pinfunction "2_2") (pintype "unspecified"))
      (node (ref "R7") (pin "1") (pinfunction "1_1") (pintype "unspecified"))
      (node (ref "R8") (pin "2") (pinfunction "2_2") (pintype "unspecified"))
      (node (ref "TP3") (pin "1") (pinfunction "1_1") (pintype "unspecified"))
      (node (ref "U1") (pin "1") (pinfunction "GND_1") (pintype "unspecified"))
      (node (ref "U1") (pin "33") (pinfunction "PAD_33") (pintype "unspecified"))
      (node (ref "U10") (pin "2") (pinfunction "GND_2") (pintype "unspecified"))
      (node (ref "U10") (pin "4") (pinfunction "C_4") (pintype "unspecified"))
      (node (ref "U11") (pin "2") (pinfunction "GND_2") (pintype "unspecified"))
      (node (ref "U11") (pin "4") (pinfunction "C_4") (pintype "unspecified"))
      (node (ref "U12") (pin "3") (pinfunction "3_3") (pintype "unspecified"))
      (node (ref "U12") (pin "4") (pinfunction "4_4") (pintype "unspecified"))
      (node (ref "U13") (pin "2") (pinfunction "GND_2") (pintype "unspecified"))
      (node (ref "U13") (pin "4") (pinfunction "C_4") (pintype "unspecified"))
      (node (ref "U14") (pin "2") (pinfunction "GND_2") (pintype "unspecified"))
      (node (ref "U14") (pin "4") (pinfunction "C_4") (pintype "unspecified"))
      (node (ref "U15") (pin "2") (pinfunction "GND_2") (pintype "unspecified"))
      (node (ref "U15") (pin "4") (pinfunction "C_4") (pintype "unspecified"))
      (node (ref "U16") (pin "2") (pinfunction "GND_2") (pintype "unspecified"))
      (node (ref "U16") (pin "4") (pinfunction "C_4") (pintype "unspecified"))
      (node (ref "U17") (pin "3") (pinfunction "3_3") (pintype "unspecified"))
      (node (ref "U17") (pin "4") (pinfunction "4_4") (pintype "unspecified"))
      (node (ref "U18") (pin "3") (pinfunction "3_3") (pintype "unspecified"))
      (node (ref "U18") (pin "4") (pinfunction "4_4") (pintype "unspecified"))
      (node (ref "U19") (pin "3") (pinfunction "3_3") (pintype "unspecified"))
      (node (ref "U19") (pin "4") (pinfunction "4_4") (pintype "unspecified"))
      (node (ref "U2") (pin "1") (pinfunction "GND_1") (pintype "unspecified"))
      (node (ref "U2") (pin "33") (pinfunction "PAD_33") (pintype "unspecified"))
      (node (ref "U20") (pin "3") (pinfunction "3_3") (pintype "unspecified"))
      (node (ref "U20") (pin "4") (pinfunction "4_4") (pintype "unspecified"))
      (node (ref "U21") (pin "3") (pinfunction "3_3") (pintype "unspecified"))
      (node (ref "U21") (pin "4") (pinfunction "4_4") (pintype "unspecified"))
      (node (ref "U22") (pin "3") (pinfunction "3_3") (pintype "unspecified"))
      (node (ref "U22") (pin "4") (pinfunction "4_4") (pintype "unspecified"))
      (node (ref "U23") (pin "3") (pinfunction "3_3") (pintype "unspecified"))
      (node (ref "U23") (pin "4") (pinfunction "4_4") (pintype "unspecified"))
      (node (ref "U24") (pin "3") (pinfunction "3_3") (pintype "unspecified"))
      (node (ref "U24") (pin "4") (pinfunction "4_4") (pintype "unspecified"))
      (node (ref "U25") (pin "3") (pinfunction "3_3") (pintype "unspecified"))
      (node (ref "U25") (pin "4") (pinfunction "4_4") (pintype "unspecified"))
      (node (ref "U26") (pin "3") (pinfunction "3_3") (pintype "unspecified"))
      (node (ref "U26") (pin "4") (pinfunction "4_4") (pintype "unspecified"))
      (node (ref "U27") (pin "3") (pinfunction "3_3") (pintype "unspecified"))
      (node (ref "U27") (pin "4") (pinfunction "4_4") (pintype "unspecified"))
      (node (ref "U28") (pin "3") (pinfunction "3_3") (pintype "unspecified"))
      (node (ref "U28") (pin "4") (pinfunction "4_4") (pintype "unspecified"))
      (node (ref "U29") (pin "3") (pinfunction "3_3") (pintype "unspecified"))
      (node (ref "U29") (pin "4") (pinfunction "4_4") (pintype "unspecified"))
      (node (ref "U3") (pin "1") (pinfunction "GND_1") (pintype "unspecified"))
      (node (ref "U3") (pin "33") (pinfunction "PAD_33") (pintype "unspecified"))
      (node (ref "U30") (pin "3") (pinfunction "3_3") (pintype "unspecified"))
      (node (ref "U30") (pin "4") (pinfunction "4_4") (pintype "unspecified"))
      (node (ref "U31") (pin "3") (pinfunction "3_3") (pintype "unspecified"))
      (node (ref "U31") (pin "4") (pinfunction "4_4") (pintype "unspecified"))
      (node (ref "U32") (pin "3") (pinfunction "3_3") (pintype "unspecified"))
      (node (ref "U32") (pin "4") (pinfunction "4_4") (pintype "unspecified"))
      (node (ref "U33") (pin "3") (pinfunction "3_3") (pintype "unspecified"))
      (node (ref "U33") (pin "4") (pinfunction "4_4") (pintype "unspecified"))
      (node (ref "U34") (pin "3") (pinfunction "3_3") (pintype "unspecified"))
      (node (ref "U34") (pin "4") (pinfunction "4_4") (pintype "unspecified"))
      (node (ref "U35") (pin "3") (pinfunction "3_3") (pintype "unspecified"))
      (node (ref "U35") (pin "4") (pinfunction "4_4") (pintype "unspecified"))
      (node (ref "U36") (pin "3") (pinfunction "3_3") (pintype "unspecified"))
      (node (ref "U36") (pin "4") (pinfunction "4_4") (pintype "unspecified"))
      (node (ref "U37") (pin "3") (pinfunction "3_3") (pintype "unspecified"))
      (node (ref "U37") (pin "4") (pinfunction "4_4") (pintype "unspecified"))
      (node (ref "U38") (pin "3") (pinfunction "3_3") (pintype "unspecified"))
      (node (ref "U38") (pin "4") (pinfunction "4_4") (pintype "unspecified"))
      (node (ref "U39") (pin "3") (pinfunction "3_3") (pintype "unspecified"))
      (node (ref "U39") (pin "4") (pinfunction "4_4") (pintype "unspecified"))
      (node (ref "U4") (pin "3") (pinfunction "3_3") (pintype "unspecified"))
      (node (ref "U4") (pin "4") (pinfunction "4_4") (pintype "unspecified"))
      (node (ref "U40") (pin "3") (pinfunction "3_3") (pintype "unspecified"))
      (node (ref "U40") (pin "4") (pinfunction "4_4") (pintype "unspecified"))
      (node (ref "U41") (pin "3") (pinfunction "3_3") (pintype "unspecified"))
      (node (ref "U41") (pin "4") (pinfunction "4_4") (pintype "unspecified"))
      (node (ref "U42") (pin "3") (pinfunction "3_3") (pintype "unspecified"))
      (node (ref "U42") (pin "4") (pinfunction "4_4") (pintype "unspecified"))
      (node (ref "U43") (pin "3") (pinfunction "3_3") (pintype "unspecified"))
      (node (ref "U43") (pin "4") (pinfunction "4_4") (pintype "unspecified"))
      (node (ref "U44") (pin "3") (pinfunction "3_3") (pintype "unspecified"))
      (node (ref "U44") (pin "4") (pinfunction "4_4") (pintype "unspecified"))
      (node (ref "U5") (pin "13") (pinfunction "GND_13") (pintype "bidirectional"))
      (node (ref "U5") (pin "18") (pinfunction "GND_18") (pintype "bidirectional"))
      (node (ref "U5") (pin "23") (pinfunction "GND_23") (pintype "bidirectional"))
      (node (ref "U5") (pin "28") (pinfunction "GND_28") (pintype "bidirectional"))
      (node (ref "U5") (pin "3") (pinfunction "GND_3") (pintype "bidirectional"))
      (node (ref "U5") (pin "33") (pinfunction "AGND/GND_33") (pintype "bidirectional"))
      (node (ref "U5") (pin "38") (pinfunction "GND_38") (pintype "bidirectional"))
      (node (ref "U5") (pin "8") (pinfunction "GND_8") (pintype "bidirectional"))
      (node (ref "U5") (pin "A") (pinfunction "GND_A") (pintype "bidirectional"))
      (node (ref "U5") (pin "B") (pinfunction "GND_B") (pintype "bidirectional"))
      (node (ref "U5") (pin "C") (pinfunction "GND_C") (pintype "bidirectional"))
      (node (ref "U5") (pin "D") (pinfunction "GND_D") (pintype "bidirectional"))
      (node (ref "U5") (pin "D2") (pinfunction "GND_D2") (pintype "bidirectional"))
      (node (ref "U6") (pin "2") (pinfunction "GND_2") (pintype "unspecified"))
      (node (ref "U6") (pin "4") (pinfunction "C_4") (pintype "unspecified"))
      (node (ref "U7") (pin "3") (pinfunction "3_3") (pintype "unspecified"))
      (node (ref "U7") (pin "4") (pinfunction "4_4") (pintype "unspecified"))
      (node (ref "U8") (pin "2") (pinfunction "GND_2") (pintype "unspecified"))
      (node (ref "U8") (pin "4") (pinfunction "C_4") (pintype "unspecified"))
      (node (ref "U9") (pin "2") (pinfunction "GND_2") (pintype "unspecified"))
      (node (ref "U9") (pin "4") (pinfunction "C_4") (pintype "unspecified"))
    )
    (net (code "4") (name "I2C_SCL") (class "Default")
      (node (ref "MCP1") (pin "12") (pinfunction "SCK_12") (pintype "unspecified"))
      (node (ref "MCP2") (pin "12") (pinfunction "SCK_12") (pintype "unspecified"))
      (node (ref "MCP3") (pin "12") (pinfunction "SCK_12") (pintype "unspecified"))
      (node (ref "MCP4") (pin "12") (pinfunction "SCK_12") (pintype "unspecified"))
      (node (ref "R4") (pin "1") (pinfunction "1_1") (pintype "unspecified"))
      (node (ref "TP4") (pin "1") (pinfunction "1_1") (pintype "unspecified"))
      (node (ref "U5") (pin "2") (pinfunction "UART0_RX/I2C0_SCL/GPI0_CSn/GP1_2") (pintype "bidirectional"))
    )
    (net (code "5") (name "I2C_SDA") (class "Default")
      (node (ref "MCP1") (pin "13") (pinfunction "SDA_13") (pintype "unspecified"))
      (node (ref "MCP2") (pin "13") (pinfunction "SDA_13") (pintype "unspecified"))
      (node (ref "MCP3") (pin "13") (pinfunction "SDA_13") (pintype "unspecified"))
      (node (ref "MCP4") (pin "13") (pinfunction "SDA_13") (pintype "unspecified"))
      (node (ref "R3") (pin "1") (pinfunction "1_1") (pintype "unspecified"))
      (node (ref "TP5") (pin "1") (pinfunction "1_1") (pintype "unspecified"))
      (node (ref "U5") (pin "1") (pinfunction "UART0_TX/I2C0_SDA/SPI0_RX/GP0_1") (pintype "bidirectional"))
    )
    (net (code "6") (name "MCP1A_0") (class "Default")
      (node (ref "MCP1") (pin "21") (pinfunction "GPA0_21") (pintype "unspecified"))
      (node (ref "U4") (pin "1") (pinfunction "1_1") (pintype "unspecified"))
      (node (ref "U4") (pin "2") (pinfunction "2_2") (pintype "unspecified"))
    )
    (net (code "7") (name "MCP1A_1") (class "Default")
      (node (ref "MCP1") (pin "22") (pinfunction "GPA1_22") (pintype "unspecified"))
      (node (ref "U7") (pin "1") (pinfunction "1_1") (pintype "unspecified"))
      (node (ref "U7") (pin "2") (pinfunction "2_2") (pintype "unspecified"))
    )
    (net (code "8") (name "MCP1A_2") (class "Default")
      (node (ref "MCP1") (pin "23") (pinfunction "GPA2_23") (pintype "unspecified"))
      (node (ref "U12") (pin "1") (pinfunction "1_1") (pintype "unspecified"))
      (node (ref "U12") (pin "2") (pinfunction "2_2") (pintype "unspecified"))
    )
    (net (code "9") (name "MCP1A_3") (class "Default")
      (node (ref "MCP1") (pin "24") (pinfunction "GPA3_24") (pintype "unspecified"))
      (node (ref "U17") (pin "1") (pinfunction "1_1") (pintype "unspecified"))
      (node (ref "U17") (pin "2") (pinfunction "2_2") (pintype "unspecified"))
    )
    (net (code "10") (name "MCP1A_4") (class "Default")
      (node (ref "MCP1") (pin "25") (pinfunction "GPA4_25") (pintype "unspecified"))
      (node (ref "U19") (pin "1") (pinfunction "1_1") (pintype "unspecified"))
      (node (ref "U19") (pin "2") (pinfunction "2_2") (pintype "unspecified"))
    )
    (net (code "11") (name "MCP1A_5") (class "Default")
      (node (ref "MCP1") (pin "26") (pinfunction "GPA5_26") (pintype "unspecified"))
      (node (ref "U18") (pin "1") (pinfunction "1_1") (pintype "unspecified"))
      (node (ref "U18") (pin "2") (pinfunction "2_2") (pintype "unspecified"))
    )
    (net (code "12") (name "MCP1A_6") (class "Default")
      (node (ref "MCP1") (pin "27") (pinfunction "GPA6_27") (pintype "unspecified"))
      (node (ref "U22") (pin "1") (pinfunction "1_1") (pintype "unspecified"))
      (node (ref "U22") (pin "2") (pinfunction "2_2") (pintype "unspecified"))
    )
    (net (code "13") (name "MCP1A_7") (class "Default")
      (node (ref "MCP1") (pin "28") (pinfunction "GPA7_28") (pintype "unspecified"))
      (node (ref "U21") (pin "1") (pinfunction "1_1") (pintype "unspecified"))
      (node (ref "U21") (pin "2") (pinfunction "2_2") (pintype "unspecified"))
    )
    (net (code "14") (name "MCP1B_0") (class "Default")
      (node (ref "MCP1") (pin "1") (pinfunction "GPB0_1") (pintype "unspecified"))
      (node (ref "U20") (pin "1") (pinfunction "1_1") (pintype "unspecified"))
      (node (ref "U20") (pin "2") (pinfunction "2_2") (pintype "unspecified"))
    )
    (net (code "15") (name "MCP1B_1") (class "Default")
      (node (ref "MCP1") (pin "2") (pinfunction "GPB1_2") (pintype "unspecified"))
      (node (ref "U15") (pin "3") (pinfunction "A_3") (pintype "unspecified"))
    )
    (net (code "16") (name "MCP1B_2") (class "Default")
      (node (ref "MCP1") (pin "3") (pinfunction "GPB2_3") (pintype "unspecified"))
      (node (ref "U15") (pin "5") (pinfunction "B_5") (pintype "unspecified"))
    )
    (net (code "17") (name "MCP1B_3") (class "Default")
      (node (ref "MCP1") (pin "4") (pinfunction "GPB3_4") (pintype "unspecified"))
      (node (ref "U15") (pin "1") (pinfunction "SW_1") (pintype "unspecified"))
    )
    (net (code "18") (name "MCP1B_4") (class "Default")
      (node (ref "MCP1") (pin "5") (pinfunction "GPB4_5") (pintype "unspecified"))
      (node (ref "U14") (pin "3") (pinfunction "A_3") (pintype "unspecified"))
    )
    (net (code "19") (name "MCP1B_5") (class "Default")
      (node (ref "MCP1") (pin "6") (pinfunction "GPB5_6") (pintype "unspecified"))
      (node (ref "U14") (pin "5") (pinfunction "B_5") (pintype "unspecified"))
    )
    (net (code "20") (name "MCP1B_6") (class "Default")
      (node (ref "MCP1") (pin "7") (pinfunction "GPB6_7") (pintype "unspecified"))
      (node (ref "U14") (pin "1") (pinfunction "SW_1") (pintype "unspecified"))
    )
    (net (code "21") (name "MCP1B_7") (class "Default")
      (node (ref "MCP1") (pin "8") (pinfunction "GPB7_8") (pintype "unspecified"))
      (node (ref "U16") (pin "3") (pinfunction "A_3") (pintype "unspecified"))
    )
    (net (code "22") (name "MCP1_INTA") (class "Default")
      (node (ref "R14") (pin "2") (pinfunction "2_2") (pintype "unspecified"))
      (node (ref "R18") (pin "1") (pinfunction "1_1") (pintype "unspecified"))
      (node (ref "U5") (pin "4") (pinfunction "I2C1_SDA/SPI0_SCK/GP2_4") (pintype "bidirectional"))
    )
    (net (code "23") (name "MCP1_INTB") (class "Default")
      (node (ref "R17") (pin "2") (pinfunction "2_2") (pintype "unspecified"))
      (node (ref "R19") (pin "1") (pinfunction "1_1") (pintype "unspecified"))
      (node (ref "U5") (pin "5") (pinfunction "I2C1_SCL/SPI0_TX/GP3_5") (pintype "bidirectional"))
    )
    (net (code "24") (name "MCP2A_0") (class "Default")
      (node (ref "MCP2") (pin "21") (pinfunction "GPA0_21") (pintype "unspecified"))
      (node (ref "U16") (pin "5") (pinfunction "B_5") (pintype "unspecified"))
    )
    (net (code "25") (name "MCP2A_1") (class "Default")
      (node (ref "MCP2") (pin "22") (pinfunction "GPA1_22") (pintype "unspecified"))
      (node (ref "U16") (pin "1") (pinfunction "SW_1") (pintype "unspecified"))
    )
    (net (code "26") (name "MCP2A_2") (class "Default")
      (node (ref "MCP2") (pin "23") (pinfunction "GPA2_23") (pintype "unspecified"))
      (node (ref "U11") (pin "3") (pinfunction "A_3") (pintype "unspecified"))
    )
    (net (code "27") (name "MCP2A_3") (class "Default")
      (node (ref "MCP2") (pin "24") (pinfunction "GPA3_24") (pintype "unspecified"))
      (node (ref "U11") (pin "5") (pinfunction "B_5") (pintype "unspecified"))
    )
    (net (code "28") (name "MCP2A_4") (class "Default")
      (node (ref "MCP2") (pin "25") (pinfunction "GPA4_25") (pintype "unspecified"))
      (node (ref "U11") (pin "1") (pinfunction "SW_1") (pintype "unspecified"))
    )
    (net (code "29") (name "MCP2A_5") (class "Default")
      (node (ref "MCP2") (pin "26") (pinfunction "GPA5_26") (pintype "unspecified"))
      (node (ref "U6") (pin "3") (pinfunction "A_3") (pintype "unspecified"))
    )
    (net (code "30") (name "MCP2A_6") (class "Default")
      (node (ref "MCP2") (pin "27") (pinfunction "GPA6_27") (pintype "unspecified"))
      (node (ref "U6") (pin "5") (pinfunction "B_5") (pintype "unspecified"))
    )
    (net (code "31") (name "MCP2A_7") (class "Default")
      (node (ref "MCP2") (pin "28") (pinfunction "GPA7_28") (pintype "unspecified"))
      (node (ref "U6") (pin "1") (pinfunction "SW_1") (pintype "unspecified"))
    )
    (net (code "32") (name "MCP2B_0") (class "Default")
      (node (ref "MCP2") (pin "1") (pinfunction "GPB0_1") (pintype "unspecified"))
      (node (ref "U25") (pin "1") (pinfunction "1_1") (pintype "unspecified"))
      (node (ref "U25") (pin "2") (pinfunction "2_2") (pintype "unspecified"))
    )
    (net (code "33") (name "MCP2B_1") (class "Default")
      (node (ref "MCP2") (pin "2") (pinfunction "GPB1_2") (pintype "unspecified"))
      (node (ref "U24") (pin "1") (pinfunction "1_1") (pintype "unspecified"))
      (node (ref "U24") (pin "2") (pinfunction "2_2") (pintype "unspecified"))
    )
    (net (code "34") (name "MCP2B_2") (class "Default")
      (node (ref "MCP2") (pin "3") (pinfunction "GPB2_3") (pintype "unspecified"))
      (node (ref "U23") (pin "1") (pinfunction "1_1") (pintype "unspecified"))
      (node (ref "U23") (pin "2") (pinfunction "2_2") (pintype "unspecified"))
    )
    (net (code "35") (name "MCP2B_3") (class "Default")
      (node (ref "MCP2") (pin "4") (pinfunction "GPB3_4") (pintype "unspecified"))
      (node (ref "U28") (pin "1") (pinfunction "1_1") (pintype "unspecified"))
      (node (ref "U28") (pin "2") (pinfunction "2_2") (pintype "unspecified"))
    )
    (net (code "36") (name "MCP2B_4") (class "Default")
      (node (ref "MCP2") (pin "5") (pinfunction "GPB4_5") (pintype "unspecified"))
      (node (ref "U29") (pin "1") (pinfunction "1_1") (pintype "unspecified"))
      (node (ref "U29") (pin "2") (pinfunction "2_2") (pintype "unspecified"))
    )
    (net (code "37") (name "MCP2B_5") (class "Default")
      (node (ref "MCP2") (pin "6") (pinfunction "GPB5_6") (pintype "unspecified"))
      (node (ref "U30") (pin "1") (pinfunction "1_1") (pintype "unspecified"))
      (node (ref "U30") (pin "2") (pinfunction "2_2") (pintype "unspecified"))
    )
    (net (code "38") (name "MCP2B_6") (class "Default")
      (node (ref "MCP2") (pin "7") (pinfunction "GPB6_7") (pintype "unspecified"))
      (node (ref "U31") (pin "1") (pinfunction "1_1") (pintype "unspecified"))
      (node (ref "U31") (pin "2") (pinfunction "2_2") (pintype "unspecified"))
    )
    (net (code "39") (name "MCP2B_7") (class "Default")
      (node (ref "MCP2") (pin "8") (pinfunction "GPB7_8") (pintype "unspecified"))
      (node (ref "U26") (pin "1") (pinfunction "1_1") (pintype "unspecified"))
      (node (ref "U26") (pin "2") (pinfunction "2_2") (pintype "unspecified"))
    )
    (net (code "40") (name "MCP2_INTA") (class "Default")
      (node (ref "R20") (pin "2") (pinfunction "2_2") (pintype "unspecified"))
      (node (ref "R21") (pin "1") (pinfunction "1_1") (pintype "unspecified"))
      (node (ref "U5") (pin "6") (pinfunction "UART1_TX/I2C0_SDA/SPI0_RX/GP4_6") (pintype "bidirectional"))
    )
    (net (code "41") (name "MCP2_INTB") (class "Default")
      (node (ref "R22") (pin "1") (pinfunction "1_1") (pintype "unspecified"))
      (node (ref "R23") (pin "2") (pinfunction "2_2") (pintype "unspecified"))
      (node (ref "U5") (pin "7") (pinfunction "UART1_RX/I2C0_SCL/SPI0_CSn/GP5_7") (pintype "bidirectional"))
    )
    (net (code "42") (name "MCP3A_0") (class "Default")
      (node (ref "MCP3") (pin "21") (pinfunction "GPA0_21") (pintype "unspecified"))
      (node (ref "U27") (pin "1") (pinfunction "1_1") (pintype "unspecified"))
      (node (ref "U27") (pin "2") (pinfunction "2_2") (pintype "unspecified"))
    )
    (net (code "43") (name "MCP3A_1") (class "Default")
      (node (ref "MCP3") (pin "22") (pinfunction "GPA1_22") (pintype "unspecified"))
      (node (ref "U33") (pin "1") (pinfunction "1_1") (pintype "unspecified"))
      (node (ref "U33") (pin "2") (pinfunction "2_2") (pintype "unspecified"))
    )
    (net (code "44") (name "MCP3A_2") (class "Default")
      (node (ref "MCP3") (pin "23") (pinfunction "GPA2_23") (pintype "unspecified"))
      (node (ref "U34") (pin "1") (pinfunction "1_1") (pintype "unspecified"))
      (node (ref "U34") (pin "2") (pinfunction "2_2") (pintype "unspecified"))
    )
    (net (code "45") (name "MCP3A_3") (class "Default")
      (node (ref "MCP3") (pin "24") (pinfunction "GPA3_24") (pintype "unspecified"))
      (node (ref "U13") (pin "3") (pinfunction "A_3") (pintype "unspecified"))
    )
    (net (code "46") (name "MCP3A_4") (class "Default")
      (node (ref "MCP3") (pin "25") (pinfunction "GPA4_25") (pintype "unspecified"))
      (node (ref "U13") (pin "5") (pinfunction "B_5") (pintype "unspecified"))
    )
    (net (code "47") (name "MCP3A_5") (class "Default")
      (node (ref "MCP3") (pin "26") (pinfunction "GPA5_26") (pintype "unspecified"))
      (node (ref "U13") (pin "1") (pinfunction "SW_1") (pintype "unspecified"))
    )
    (net (code "48") (name "MCP3A_6") (class "Default")
      (node (ref "MCP3") (pin "27") (pinfunction "GPA6_27") (pintype "unspecified"))
      (node (ref "U10") (pin "3") (pinfunction "A_3") (pintype "unspecified"))
    )
    (net (code "49") (name "MCP3A_7") (class "Default")
      (node (ref "MCP3") (pin "28") (pinfunction "GPA7_28") (pintype "unspecified"))
      (node (ref "U10") (pin "5") (pinfunction "B_5") (pintype "unspecified"))
    )
    (net (code "50") (name "MCP3B_0") (class "Default")
      (node (ref "MCP3") (pin "1") (pinfunction "GPB0_1") (pintype "unspecified"))
      (node (ref "U10") (pin "1") (pinfunction "SW_1") (pintype "unspecified"))
    )
    (net (code "51") (name "MCP3B_1") (class "Default")
      (node (ref "MCP3") (pin "2") (pinfunction "GPB1_2") (pintype "unspecified"))
      (node (ref "U8") (pin "3") (pinfunction "A_3") (pintype "unspecified"))
    )
    (net (code "52") (name "MCP3B_2") (class "Default")
      (node (ref "MCP3") (pin "3") (pinfunction "GPB2_3") (pintype "unspecified"))
      (node (ref "U8") (pin "5") (pinfunction "B_5") (pintype "unspecified"))
    )
    (net (code "53") (name "MCP3B_3") (class "Default")
      (node (ref "MCP3") (pin "4") (pinfunction "GPB3_4") (pintype "unspecified"))
      (node (ref "U9") (pin "3") (pinfunction "A_3") (pintype "unspecified"))
    )
    (net (code "54") (name "MCP3B_4") (class "Default")
      (node (ref "MCP3") (pin "5") (pinfunction "GPB4_5") (pintype "unspecified"))
      (node (ref "U9") (pin "5") (pinfunction "B_5") (pintype "unspecified"))
    )
    (net (code "55") (name "MCP3B_5") (class "Default")
      (node (ref "MCP3") (pin "6") (pinfunction "GPB5_6") (pintype "unspecified"))
      (node (ref "U35") (pin "1") (pinfunction "1_1") (pintype "unspecified"))
      (node (ref "U35") (pin "2") (pinfunction "2_2") (pintype "unspecified"))
    )
    (net (code "56") (name "MCP3B_6") (class "Default")
      (node (ref "MCP3") (pin "7") (pinfunction "GPB6_7") (pintype "unspecified"))
      (node (ref "U36") (pin "1") (pinfunction "1_1") (pintype "unspecified"))
      (node (ref "U36") (pin "2") (pinfunction "2_2") (pintype "unspecified"))
    )
    (net (code "57") (name "MCP3B_7") (class "Default")
      (node (ref "MCP3") (pin "8") (pinfunction "GPB7_8") (pintype "unspecified"))
      (node (ref "U37") (pin "1") (pinfunction "1_1") (pintype "unspecified"))
      (node (ref "U37") (pin "2") (pinfunction "2_2") (pintype "unspecified"))
    )
    (net (code "58") (name "MCP3_INTA") (class "Default")
      (node (ref "R29") (pin "2") (pinfunction "2_2") (pintype "unspecified"))
      (node (ref "R30") (pin "1") (pinfunction "1_1") (pintype "unspecified"))
      (node (ref "U5") (pin "9") (pinfunction "I2C1_SDA/SPI0_SCK/GP6_9") (pintype "bidirectional"))
    )
    (net (code "59") (name "MCP3_INTB") (class "Default")
      (node (ref "R28") (pin "2") (pinfunction "2_2") (pintype "unspecified"))
      (node (ref "R31") (pin "1") (pinfunction "1_1") (pintype "unspecified"))
      (node (ref "U5") (pin "10") (pinfunction "I2C1_SCL/SPI0_TX/GP7_10") (pintype "bidirectional"))
    )
    (net (code "60") (name "MCP4A_0") (class "Default")
      (node (ref "MCP4") (pin "21") (pinfunction "GPA0_21") (pintype "unspecified"))
      (node (ref "U38") (pin "1") (pinfunction "1_1") (pintype "unspecified"))
      (node (ref "U38") (pin "2") (pinfunction "2_2") (pintype "unspecified"))
    )
    (net (code "61") (name "MCP4A_1") (class "Default")
      (node (ref "MCP4") (pin "22") (pinfunction "GPA1_22") (pintype "unspecified"))
      (node (ref "U39") (pin "1") (pinfunction "1_1") (pintype "unspecified"))
      (node (ref "U39") (pin "2") (pinfunction "2_2") (pintype "unspecified"))
    )
    (net (code "62") (name "MCP4A_2") (class "Default")
      (node (ref "MCP4") (pin "23") (pinfunction "GPA2_23") (pintype "unspecified"))
      (node (ref "U40") (pin "1") (pinfunction "1_1") (pintype "unspecified"))
      (node (ref "U40") (pin "2") (pinfunction "2_2") (pintype "unspecified"))
    )
    (net (code "63") (name "MCP4A_3") (class "Default")
      (node (ref "MCP4") (pin "24") (pinfunction "GPA3_24") (pintype "unspecified"))
      (node (ref "U32") (pin "1") (pinfunction "1_1") (pintype "unspecified"))
      (node (ref "U32") (pin "2") (pinfunction "2_2") (pintype "unspecified"))
    )
    (net (code "64") (name "MCP4A_4") (class "Default")
      (node (ref "MCP4") (pin "25") (pinfunction "GPA4_25") (pintype "unspecified"))
      (node (ref "U43") (pin "1") (pinfunction "1_1") (pintype "unspecified"))
      (node (ref "U43") (pin "2") (pinfunction "2_2") (pintype "unspecified"))
    )
    (net (code "65") (name "MCP4A_5") (class "Default")
      (node (ref "MCP4") (pin "26") (pinfunction "GPA5_26") (pintype "unspecified"))
      (node (ref "U42") (pin "1") (pinfunction "1_1") (pintype "unspecified"))
      (node (ref "U42") (pin "2") (pinfunction "2_2") (pintype "unspecified"))
    )
    (net (code "66") (name "MCP4A_6") (class "Default")
      (node (ref "MCP4") (pin "27") (pinfunction "GPA6_27") (pintype "unspecified"))
      (node (ref "U41") (pin "1") (pinfunction "1_1") (pintype "unspecified"))
      (node (ref "U41") (pin "2") (pinfunction "2_2") (pintype "unspecified"))
    )
    (net (code "67") (name "MCP4A_7") (class "Default")
      (node (ref "MCP4") (pin "28") (pinfunction "GPA7_28") (pintype "unspecified"))
      (node (ref "U44") (pin "1") (pinfunction "1_1") (pintype "unspecified"))
      (node (ref "U44") (pin "2") (pinfunction "2_2") (pintype "unspecified"))
    )
    (net (code "68") (name "MCP4_INTA") (class "Default")
      (node (ref "R25") (pin "2") (pinfunction "2_2") (pintype "unspecified"))
      (node (ref "R26") (pin "1") (pinfunction "1_1") (pintype "unspecified"))
      (node (ref "U5") (pin "11") (pinfunction "UART1_TX/I2C0_SDA/SPI1_RX/GP8_11") (pintype "bidirectional"))
    )
    (net (code "69") (name "MCP4_INTB") (class "Default")
      (node (ref "R24") (pin "2") (pinfunction "2_2") (pintype "unspecified"))
      (node (ref "R27") (pin "1") (pinfunction "1_1") (pintype "unspecified"))
      (node (ref "U5") (pin "12") (pinfunction "UART1_RX/I2C0_SCL/SPI1_CSn/GP9_12") (pintype "bidirectional"))
    )
    (net (code "70") (name "Net-(C10-Pad1)") (class "Default")
      (node (ref "C10") (pin "1") (pinfunction "1_1") (pintype "unspecified"))
      (node (ref "C13") (pin "2") (pinfunction "2_2") (pintype "unspecified"))
      (node (ref "GPIO1") (pin "2") (pinfunction "5V_2") (pintype "unspecified"))
      (node (ref "GPIO1") (pin "4") (pinfunction "5V_4") (pintype "unspecified"))
      (node (ref "R13") (pin "1") (pinfunction "1_1") (pintype "unspecified"))
      (node (ref "TP1") (pin "1") (pinfunction "1_1") (pintype "unspecified"))
    )
    (net (code "71") (name "Net-(J1-Pad1)") (class "Default")
      (node (ref "J1") (pin "1") (pinfunction "1_1") (pintype "bidirectional"))
      (node (ref "U45") (pin "1") (pinfunction "1_1") (pintype "unspecified"))
    )
    (net (code "72") (name "Net-(LED2-Pad1)") (class "Default")
      (node (ref "LED2") (pin "1") (pinfunction "1_1") (pintype "unspecified"))
      (node (ref "R15") (pin "1") (pinfunction "1_1") (pintype "unspecified"))
    )
    (net (code "73") (name "Net-(MCP1-INTA)") (class "Default")
      (node (ref "MCP1") (pin "20") (pinfunction "INTA_20") (pintype "unspecified"))
      (node (ref "R14") (pin "1") (pinfunction "1_1") (pintype "unspecified"))
    )
    (net (code "74") (name "Net-(MCP1-INTB)") (class "Default")
      (node (ref "MCP1") (pin "19") (pinfunction "INTB_19") (pintype "unspecified"))
      (node (ref "R17") (pin "1") (pinfunction "1_1") (pintype "unspecified"))
    )
    (net (code "75") (name "Net-(MCP1-RESET#)") (class "Default")
      (node (ref "MCP1") (pin "18") (pinfunction "RESET#_18") (pintype "unspecified"))
      (node (ref "R9") (pin "1") (pinfunction "1_1") (pintype "unspecified"))
    )
    (net (code "76") (name "Net-(MCP2-INTA)") (class "Default")
      (node (ref "MCP2") (pin "20") (pinfunction "INTA_20") (pintype "unspecified"))
      (node (ref "R20") (pin "1") (pinfunction "1_1") (pintype "unspecified"))
    )
    (net (code "77") (name "Net-(MCP2-INTB)") (class "Default")
      (node (ref "MCP2") (pin "19") (pinfunction "INTB_19") (pintype "unspecified"))
      (node (ref "R23") (pin "1") (pinfunction "1_1") (pintype "unspecified"))
    )
    (net (code "78") (name "Net-(MCP2-RESET#)") (class "Default")
      (node (ref "MCP2") (pin "18") (pinfunction "RESET#_18") (pintype "unspecified"))
      (node (ref "R10") (pin "1") (pinfunction "1_1") (pintype "unspecified"))
    )
    (net (code "79") (name "Net-(MCP3-INTA)") (class "Default")
      (node (ref "MCP3") (pin "20") (pinfunction "INTA_20") (pintype "unspecified"))
      (node (ref "R29") (pin "1") (pinfunction "1_1") (pintype "unspecified"))
    )
    (net (code "80") (name "Net-(MCP3-INTB)") (class "Default")
      (node (ref "MCP3") (pin "19") (pinfunction "INTB_19") (pintype "unspecified"))
      (node (ref "R28") (pin "1") (pinfunction "1_1") (pintype "unspecified"))
    )
    (net (code "81") (name "Net-(MCP3-RESET#)") (class "Default")
      (node (ref "MCP3") (pin "18") (pinfunction "RESET#_18") (pintype "unspecified"))
      (node (ref "R11") (pin "1") (pinfunction "1_1") (pintype "unspecified"))
    )
    (net (code "82") (name "Net-(MCP4-INTA)") (class "Default")
      (node (ref "MCP4") (pin "20") (pinfunction "INTA_20") (pintype "unspecified"))
      (node (ref "R25") (pin "1") (pinfunction "1_1") (pintype "unspecified"))
    )
    (net (code "83") (name "Net-(MCP4-INTB)") (class "Default")
      (node (ref "MCP4") (pin "19") (pinfunction "INTB_19") (pintype "unspecified"))
      (node (ref "R24") (pin "1") (pinfunction "1_1") (pintype "unspecified"))
    )
    (net (code "84") (name "Net-(MCP4-RESET#)") (class "Default")
      (node (ref "MCP4") (pin "18") (pinfunction "RESET#_18") (pintype "unspecified"))
      (node (ref "R12") (pin "1") (pinfunction "1_1") (pintype "unspecified"))
    )
    (net (code "85") (name "Net-(U1-IREF)") (class "Default")
      (node (ref "R1") (pin "1") (pinfunction "1_1") (pintype "unspecified"))
      (node (ref "U1") (pin "31") (pinfunction "IREF_31") (pintype "unspecified"))
    )
    (net (code "86") (name "Net-(U2-IREF)") (class "Default")
      (node (ref "R6") (pin "1") (pinfunction "1_1") (pintype "unspecified"))
      (node (ref "U2") (pin "31") (pinfunction "IREF_31") (pintype "unspecified"))
    )
    (net (code "87") (name "Net-(U3-IREF)") (class "Default")
      (node (ref "R8") (pin "1") (pinfunction "1_1") (pintype "unspecified"))
      (node (ref "U3") (pin "31") (pinfunction "IREF_31") (pintype "unspecified"))
    )
    (net (code "88") (name "Net-(U5-VSYS)") (class "Default")
      (node (ref "R16") (pin "1") (pinfunction "1_1") (pintype "unspecified"))
      (node (ref "U5") (pin "39") (pinfunction "VSYS_39") (pintype "bidirectional"))
    )
    (net (code "89") (name "PICO_TLC_BLANK") (class "Default")
      (node (ref "R2") (pin "2") (pinfunction "2_2") (pintype "unspecified"))
      (node (ref "R5") (pin "2") (pinfunction "2_2") (pintype "unspecified"))
      (node (ref "R7") (pin "2") (pinfunction "2_2") (pintype "unspecified"))
      (node (ref "TP7") (pin "1") (pinfunction "1_1") (pintype "unspecified"))
      (node (ref "U1") (pin "2") (pinfunction "BLANK_2") (pintype "unspecified"))
      (node (ref "U2") (pin "2") (pinfunction "BLANK_2") (pintype "unspecified"))
      (node (ref "U3") (pin "2") (pinfunction "BLANK_2") (pintype "unspecified"))
      (node (ref "U5") (pin "26") (pinfunction "I2C0_SDA/GP20_26") (pintype "bidirectional"))
    )
    (net (code "90") (name "PICO_TLC_SCLK") (class "Default")
      (node (ref "TP11") (pin "1") (pinfunction "1_1") (pintype "unspecified"))
      (node (ref "U1") (pin "3") (pinfunction "SCLK_3") (pintype "unspecified"))
      (node (ref "U2") (pin "3") (pinfunction "SCLK_3") (pintype "unspecified"))
      (node (ref "U3") (pin "3") (pinfunction "SCLK_3") (pintype "unspecified"))
      (node (ref "U5") (pin "24") (pinfunction "I2C1_SDA/SPI0_SCK/GP18_24") (pintype "bidirectional"))
    )
    (net (code "91") (name "PICO_TLC_SIN") (class "Default")
      (node (ref "TP6") (pin "1") (pinfunction "1_1") (pintype "unspecified"))
      (node (ref "U1") (pin "4") (pinfunction "SIN_4") (pintype "unspecified"))
      (node (ref "U5") (pin "25") (pinfunction "I2C1_SCL/SPI0_TX/GP19_25") (pintype "bidirectional"))
    )
    (net (code "92") (name "PICO_TLC_XLAT") (class "Default")
      (node (ref "TP8") (pin "1") (pinfunction "1_1") (pintype "unspecified"))
      (node (ref "U1") (pin "30") (pinfunction "XLAT_30") (pintype "unspecified"))
      (node (ref "U2") (pin "30") (pinfunction "XLAT_30") (pintype "unspecified"))
      (node (ref "U3") (pin "30") (pinfunction "XLAT_30") (pintype "unspecified"))
      (node (ref "U5") (pin "29") (pinfunction "GP22_29") (pintype "bidirectional"))
    )
    (net (code "93") (name "SOUT1_TLC2") (class "Default")
      (node (ref "U1") (pin "29") (pinfunction "SOUT_29") (pintype "unspecified"))
      (node (ref "U2") (pin "4") (pinfunction "SIN_4") (pintype "unspecified"))
    )
    (net (code "94") (name "SOUT2_TLC3") (class "Default")
      (node (ref "U2") (pin "29") (pinfunction "SOUT_29") (pintype "unspecified"))
      (node (ref "U3") (pin "4") (pinfunction "SIN_4") (pintype "unspecified"))
    )
    (net (code "95") (name "TLC1_0") (class "Default")
      (node (ref "LED14") (pin "4") (pinfunction "B_4") (pintype "unspecified"))
      (node (ref "U1") (pin "5") (pinfunction "OUT0_5") (pintype "unspecified"))
    )
    (net (code "96") (name "TLC1_1") (class "Default")
      (node (ref "LED14") (pin "3") (pinfunction "G_3") (pintype "unspecified"))
      (node (ref "U1") (pin "6") (pinfunction "OUT1_6") (pintype "unspecified"))
    )
    (net (code "97") (name "TLC1_2") (class "Default")
      (node (ref "LED14") (pin "1") (pinfunction "R_1") (pintype "unspecified"))
      (node (ref "U1") (pin "7") (pinfunction "OUT2_7") (pintype "unspecified"))
    )
    (net (code "98") (name "TLC1_3") (class "Default")
      (node (ref "LED4") (pin "4") (pinfunction "B_4") (pintype "unspecified"))
      (node (ref "U1") (pin "8") (pinfunction "OUT3_8") (pintype "unspecified"))
    )
    (net (code "99") (name "TLC1_4") (class "Default")
      (node (ref "LED4") (pin "3") (pinfunction "G_3") (pintype "unspecified"))
      (node (ref "U1") (pin "9") (pinfunction "OUT4_9") (pintype "unspecified"))
    )
    (net (code "100") (name "TLC1_5") (class "Default")
      (node (ref "LED4") (pin "1") (pinfunction "R_1") (pintype "unspecified"))
      (node (ref "U1") (pin "10") (pinfunction "OUT5_10") (pintype "unspecified"))
    )
    (net (code "101") (name "TLC1_6") (class "Default")
      (node (ref "LED3") (pin "2") (pinfunction "2_2") (pintype "unspecified"))
      (node (ref "U1") (pin "11") (pinfunction "OUT6_11") (pintype "unspecified"))
    )
    (net (code "102") (name "TLC1_7") (class "Default")
      (node (ref "LED5") (pin "2") (pinfunction "2_2") (pintype "unspecified"))
      (node (ref "U1") (pin "12") (pinfunction "OUT7_12") (pintype "unspecified"))
    )
    (net (code "103") (name "TLC1_8") (class "Default")
      (node (ref "LED6") (pin "2") (pinfunction "2_2") (pintype "unspecified"))
      (node (ref "U1") (pin "13") (pinfunction "OUT8_13") (pintype "unspecified"))
    )
    (net (code "104") (name "TLC1_9") (class "Default")
      (node (ref "LED7") (pin "2") (pinfunction "2_2") (pintype "unspecified"))
      (node (ref "U1") (pin "14") (pinfunction "OUT9_14") (pintype "unspecified"))
    )
    (net (code "105") (name "TLC1_10") (class "Default")
      (node (ref "LED8") (pin "2") (pinfunction "2_2") (pintype "unspecified"))
      (node (ref "U1") (pin "15") (pinfunction "OUT10_15") (pintype "unspecified"))
    )
    (net (code "106") (name "TLC1_11") (class "Default")
      (node (ref "LED9") (pin "2") (pinfunction "2_2") (pintype "unspecified"))
      (node (ref "U1") (pin "16") (pinfunction "OUT11_16") (pintype "unspecified"))
    )
    (net (code "107") (name "TLC1_12") (class "Default")
      (node (ref "LED10") (pin "2") (pinfunction "2_2") (pintype "unspecified"))
      (node (ref "U1") (pin "17") (pinfunction "OUT12_17") (pintype "unspecified"))
    )
    (net (code "108") (name "TLC1_13") (class "Default")
      (node (ref "LED11") (pin "2") (pinfunction "2_2") (pintype "unspecified"))
      (node (ref "U1") (pin "18") (pinfunction "OUT13_18") (pintype "unspecified"))
    )
    (net (code "109") (name "TLC1_14") (class "Default")
      (node (ref "LED12") (pin "2") (pinfunction "2_2") (pintype "unspecified"))
      (node (ref "U1") (pin "19") (pinfunction "OUT14_19") (pintype "unspecified"))
    )
    (net (code "110") (name "TLC1_15") (class "Default")
      (node (ref "LED13") (pin "2") (pinfunction "2_2") (pintype "unspecified"))
      (node (ref "U1") (pin "20") (pinfunction "OUT15_20") (pintype "unspecified"))
    )
    (net (code "111") (name "TLC1_16") (class "Default")
      (node (ref "LED15") (pin "2") (pinfunction "2_2") (pintype "unspecified"))
      (node (ref "U1") (pin "21") (pinfunction "OUT16_21") (pintype "unspecified"))
    )
    (net (code "112") (name "TLC1_17") (class "Default")
      (node (ref "LED16") (pin "2") (pinfunction "2_2") (pintype "unspecified"))
      (node (ref "U1") (pin "22") (pinfunction "OUT17_22") (pintype "unspecified"))
    )
    (net (code "113") (name "TLC1_18") (class "Default")
      (node (ref "LED17") (pin "2") (pinfunction "2_2") (pintype "unspecified"))
      (node (ref "U1") (pin "23") (pinfunction "OUT18_23") (pintype "unspecified"))
    )
    (net (code "114") (name "TLC1_19") (class "Default")
      (node (ref "LED18") (pin "2") (pinfunction "2_2") (pintype "unspecified"))
      (node (ref "U1") (pin "24") (pinfunction "OUT19_24") (pintype "unspecified"))
    )
    (net (code "115") (name "TLC1_20") (class "Default")
      (node (ref "LED21") (pin "2") (pinfunction "2_2") (pintype "unspecified"))
      (node (ref "U1") (pin "25") (pinfunction "OUT20_25") (pintype "unspecified"))
    )
    (net (code "116") (name "TLC1_21") (class "Default")
      (node (ref "LED30") (pin "2") (pinfunction "2_2") (pintype "unspecified"))
      (node (ref "U1") (pin "26") (pinfunction "OUT21_26") (pintype "unspecified"))
    )
    (net (code "117") (name "TLC1_22") (class "Default")
      (node (ref "LED31") (pin "2") (pinfunction "2_2") (pintype "unspecified"))
      (node (ref "U1") (pin "27") (pinfunction "OUT22_27") (pintype "unspecified"))
    )
    (net (code "118") (name "TLC1_23") (class "Default")
      (node (ref "LED32") (pin "2") (pinfunction "2_2") (pintype "unspecified"))
      (node (ref "U1") (pin "28") (pinfunction "OUT23_28") (pintype "unspecified"))
    )
    (net (code "119") (name "TLC2_0") (class "Default")
      (node (ref "LED19") (pin "4") (pinfunction "B_4") (pintype "unspecified"))
      (node (ref "U2") (pin "5") (pinfunction "OUT0_5") (pintype "unspecified"))
    )
    (net (code "120") (name "TLC2_1") (class "Default")
      (node (ref "LED19") (pin "3") (pinfunction "G_3") (pintype "unspecified"))
      (node (ref "U2") (pin "6") (pinfunction "OUT1_6") (pintype "unspecified"))
    )
    (net (code "121") (name "TLC2_2") (class "Default")
      (node (ref "LED19") (pin "1") (pinfunction "R_1") (pintype "unspecified"))
      (node (ref "U2") (pin "7") (pinfunction "OUT2_7") (pintype "unspecified"))
    )
    (net (code "122") (name "TLC2_3") (class "Default")
      (node (ref "LED20") (pin "4") (pinfunction "B_4") (pintype "unspecified"))
      (node (ref "U2") (pin "8") (pinfunction "OUT3_8") (pintype "unspecified"))
    )
    (net (code "123") (name "TLC2_4") (class "Default")
      (node (ref "LED20") (pin "3") (pinfunction "G_3") (pintype "unspecified"))
      (node (ref "U2") (pin "9") (pinfunction "OUT4_9") (pintype "unspecified"))
    )
    (net (code "124") (name "TLC2_5") (class "Default")
      (node (ref "LED20") (pin "1") (pinfunction "R_1") (pintype "unspecified"))
      (node (ref "U2") (pin "10") (pinfunction "OUT5_10") (pintype "unspecified"))
    )
    (net (code "125") (name "TLC2_6") (class "Default")
      (node (ref "LED22") (pin "4") (pinfunction "B_4") (pintype "unspecified"))
      (node (ref "U2") (pin "11") (pinfunction "OUT6_11") (pintype "unspecified"))
    )
    (net (code "126") (name "TLC2_7") (class "Default")
      (node (ref "LED22") (pin "3") (pinfunction "G_3") (pintype "unspecified"))
      (node (ref "U2") (pin "12") (pinfunction "OUT7_12") (pintype "unspecified"))
    )
    (net (code "127") (name "TLC2_8") (class "Default")
      (node (ref "LED22") (pin "1") (pinfunction "R_1") (pintype "unspecified"))
      (node (ref "U2") (pin "13") (pinfunction "OUT8_13") (pintype "unspecified"))
    )
    (net (code "128") (name "TLC2_9") (class "Default")
      (node (ref "LED23") (pin "4") (pinfunction "B_4") (pintype "unspecified"))
      (node (ref "U2") (pin "14") (pinfunction "OUT9_14") (pintype "unspecified"))
    )
    (net (code "129") (name "TLC2_10") (class "Default")
      (node (ref "LED23") (pin "3") (pinfunction "G_3") (pintype "unspecified"))
      (node (ref "U2") (pin "15") (pinfunction "OUT10_15") (pintype "unspecified"))
    )
    (net (code "130") (name "TLC2_11") (class "Default")
      (node (ref "LED23") (pin "1") (pinfunction "R_1") (pintype "unspecified"))
      (node (ref "U2") (pin "16") (pinfunction "OUT11_16") (pintype "unspecified"))
    )
    (net (code "131") (name "TLC2_12") (class "Default")
      (node (ref "LED24") (pin "4") (pinfunction "B_4") (pintype "unspecified"))
      (node (ref "U2") (pin "17") (pinfunction "OUT12_17") (pintype "unspecified"))
    )
    (net (code "132") (name "TLC2_13") (class "Default")
      (node (ref "LED24") (pin "3") (pinfunction "G_3") (pintype "unspecified"))
      (node (ref "U2") (pin "18") (pinfunction "OUT13_18") (pintype "unspecified"))
    )
    (net (code "133") (name "TLC2_14") (class "Default")
      (node (ref "LED24") (pin "1") (pinfunction "R_1") (pintype "unspecified"))
      (node (ref "U2") (pin "19") (pinfunction "OUT14_19") (pintype "unspecified"))
    )
    (net (code "134") (name "TLC2_15") (class "Default")
      (node (ref "LED25") (pin "4") (pinfunction "B_4") (pintype "unspecified"))
      (node (ref "U2") (pin "20") (pinfunction "OUT15_20") (pintype "unspecified"))
    )
    (net (code "135") (name "TLC2_16") (class "Default")
      (node (ref "LED25") (pin "3") (pinfunction "G_3") (pintype "unspecified"))
      (node (ref "U2") (pin "21") (pinfunction "OUT16_21") (pintype "unspecified"))
    )
    (net (code "136") (name "TLC2_17") (class "Default")
      (node (ref "LED25") (pin "1") (pinfunction "R_1") (pintype "unspecified"))
      (node (ref "U2") (pin "22") (pinfunction "OUT17_22") (pintype "unspecified"))
    )
    (net (code "137") (name "TLC2_18") (class "Default")
      (node (ref "LED26") (pin "4") (pinfunction "B_4") (pintype "unspecified"))
      (node (ref "U2") (pin "23") (pinfunction "OUT18_23") (pintype "unspecified"))
    )
    (net (code "138") (name "TLC2_19") (class "Default")
      (node (ref "LED26") (pin "3") (pinfunction "G_3") (pintype "unspecified"))
      (node (ref "U2") (pin "24") (pinfunction "OUT19_24") (pintype "unspecified"))
    )
    (net (code "139") (name "TLC2_20") (class "Default")
      (node (ref "LED26") (pin "1") (pinfunction "R_1") (pintype "unspecified"))
      (node (ref "U2") (pin "25") (pinfunction "OUT20_25") (pintype "unspecified"))
    )
    (net (code "140") (name "TLC2_21") (class "Default")
      (node (ref "LED27") (pin "4") (pinfunction "B_4") (pintype "unspecified"))
      (node (ref "U2") (pin "26") (pinfunction "OUT21_26") (pintype "unspecified"))
    )
    (net (code "141") (name "TLC2_22") (class "Default")
      (node (ref "LED27") (pin "3") (pinfunction "G_3") (pintype "unspecified"))
      (node (ref "U2") (pin "27") (pinfunction "OUT22_27") (pintype "unspecified"))
    )
    (net (code "142") (name "TLC2_23") (class "Default")
      (node (ref "LED27") (pin "1") (pinfunction "R_1") (pintype "unspecified"))
      (node (ref "U2") (pin "28") (pinfunction "OUT23_28") (pintype "unspecified"))
    )
    (net (code "143") (name "TLC3_0") (class "Default")
      (node (ref "LED28") (pin "4") (pinfunction "B_4") (pintype "unspecified"))
      (node (ref "U3") (pin "5") (pinfunction "OUT0_5") (pintype "unspecified"))
    )
    (net (code "144") (name "TLC3_1") (class "Default")
      (node (ref "LED28") (pin "3") (pinfunction "G_3") (pintype "unspecified"))
      (node (ref "U3") (pin "6") (pinfunction "OUT1_6") (pintype "unspecified"))
    )
    (net (code "145") (name "TLC3_2") (class "Default")
      (node (ref "LED28") (pin "1") (pinfunction "R_1") (pintype "unspecified"))
      (node (ref "U3") (pin "7") (pinfunction "OUT2_7") (pintype "unspecified"))
    )
    (net (code "146") (name "TLC3_3") (class "Default")
      (node (ref "LED29") (pin "4") (pinfunction "B_4") (pintype "unspecified"))
      (node (ref "U3") (pin "8") (pinfunction "OUT3_8") (pintype "unspecified"))
    )
    (net (code "147") (name "TLC3_4") (class "Default")
      (node (ref "LED29") (pin "3") (pinfunction "G_3") (pintype "unspecified"))
      (node (ref "U3") (pin "9") (pinfunction "OUT4_9") (pintype "unspecified"))
    )
    (net (code "148") (name "TLC3_5") (class "Default")
      (node (ref "LED29") (pin "1") (pinfunction "R_1") (pintype "unspecified"))
      (node (ref "U3") (pin "10") (pinfunction "OUT5_10") (pintype "unspecified"))
    )
    (net (code "149") (name "TLC3_6") (class "Default")
      (node (ref "LED33") (pin "2") (pinfunction "2_2") (pintype "unspecified"))
      (node (ref "U3") (pin "11") (pinfunction "OUT6_11") (pintype "unspecified"))
    )
    (net (code "150") (name "TLC3_7") (class "Default")
      (node (ref "LED38") (pin "4") (pinfunction "B_4") (pintype "unspecified"))
      (node (ref "U3") (pin "12") (pinfunction "OUT7_12") (pintype "unspecified"))
    )
    (net (code "151") (name "TLC3_8") (class "Default")
      (node (ref "LED38") (pin "3") (pinfunction "G_3") (pintype "unspecified"))
      (node (ref "U3") (pin "13") (pinfunction "OUT8_13") (pintype "unspecified"))
    )
    (net (code "152") (name "TLC3_9") (class "Default")
      (node (ref "LED38") (pin "1") (pinfunction "R_1") (pintype "unspecified"))
      (node (ref "U3") (pin "14") (pinfunction "OUT9_14") (pintype "unspecified"))
    )
    (net (code "153") (name "TLC3_10") (class "Default")
      (node (ref "LED37") (pin "4") (pinfunction "B_4") (pintype "unspecified"))
      (node (ref "U3") (pin "15") (pinfunction "OUT10_15") (pintype "unspecified"))
    )
    (net (code "154") (name "TLC3_11") (class "Default")
      (node (ref "LED37") (pin "3") (pinfunction "G_3") (pintype "unspecified"))
      (node (ref "U3") (pin "16") (pinfunction "OUT11_16") (pintype "unspecified"))
    )
    (net (code "155") (name "TLC3_12") (class "Default")
      (node (ref "LED37") (pin "1") (pinfunction "R_1") (pintype "unspecified"))
      (node (ref "U3") (pin "17") (pinfunction "OUT12_17") (pintype "unspecified"))
    )
    (net (code "156") (name "TLC3_13") (class "Default")
      (node (ref "LED36") (pin "4") (pinfunction "B_4") (pintype "unspecified"))
      (node (ref "U3") (pin "18") (pinfunction "OUT13_18") (pintype "unspecified"))
    )
    (net (code "157") (name "TLC3_14") (class "Default")
      (node (ref "LED36") (pin "3") (pinfunction "G_3") (pintype "unspecified"))
      (node (ref "U3") (pin "19") (pinfunction "OUT14_19") (pintype "unspecified"))
    )
    (net (code "158") (name "TLC3_15") (class "Default")
      (node (ref "LED36") (pin "1") (pinfunction "R_1") (pintype "unspecified"))
      (node (ref "U3") (pin "20") (pinfunction "OUT15_20") (pintype "unspecified"))
    )
    (net (code "159") (name "TLC3_16") (class "Default")
      (node (ref "LED35") (pin "4") (pinfunction "B_4") (pintype "unspecified"))
      (node (ref "U3") (pin "21") (pinfunction "OUT16_21") (pintype "unspecified"))
    )
    (net (code "160") (name "TLC3_17") (class "Default")
      (node (ref "LED35") (pin "3") (pinfunction "G_3") (pintype "unspecified"))
      (node (ref "U3") (pin "22") (pinfunction "OUT17_22") (pintype "unspecified"))
    )
    (net (code "161") (name "TLC3_18") (class "Default")
      (node (ref "LED35") (pin "1") (pinfunction "R_1") (pintype "unspecified"))
      (node (ref "U3") (pin "23") (pinfunction "OUT18_23") (pintype "unspecified"))
    )
    (net (code "162") (name "TLC3_19") (class "Default")
      (node (ref "LED34") (pin "2") (pinfunction "2_2") (pintype "unspecified"))
      (node (ref "U3") (pin "24") (pinfunction "OUT19_24") (pintype "unspecified"))
    )
    (net (code "163") (name "TLC3_20") (class "Default")
      (node (ref "LED1") (pin "2") (pinfunction "2_2") (pintype "unspecified"))
      (node (ref "U3") (pin "25") (pinfunction "OUT20_25") (pintype "unspecified"))
    )
    (net (code "164") (name "TLC3_21") (class "Default")
      (node (ref "LED39") (pin "2") (pinfunction "2_2") (pintype "unspecified"))
      (node (ref "U3") (pin "26") (pinfunction "OUT21_26") (pintype "unspecified"))
    )
    (net (code "165") (name "UART_RX_PICO") (class "Default")
      (node (ref "GPIO1") (pin "8") (pinfunction "GPIO_14_8") (pintype "unspecified"))
      (node (ref "TP10") (pin "1") (pinfunction "1_1") (pintype "unspecified"))
      (node (ref "U5") (pin "22") (pinfunction "UART0_RX/I2C0_SCL/SPI0_CSn/GP17_22") (pintype "bidirectional"))
    )
    (net (code "166") (name "UART_TX_PICO") (class "Default")
      (node (ref "GPIO1") (pin "10") (pinfunction "GPIO_15_10") (pintype "unspecified"))
      (node (ref "TP9") (pin "1") (pinfunction "1_1") (pintype "unspecified"))
      (node (ref "U5") (pin "21") (pinfunction "UART0_TX/I2C0_SDA/SPI0_RX/GP16_21") (pintype "bidirectional"))
    )
    (net (code "167") (name "unconnected-(GPIO1-3.3V-Pad1)") (class "Default")
      (node (ref "GPIO1") (pin "1") (pinfunction "3.3V_1") (pintype "output+no_connect"))
    )
    (net (code "168") (name "unconnected-(GPIO1-3.3V-Pad17)") (class "Default")
      (node (ref "GPIO1") (pin "17") (pinfunction "3.3V_17") (pintype "output+no_connect"))
    )
    (net (code "169") (name "unconnected-(GPIO1-GPIO_0-Pad27)") (class "Default")
      (node (ref "GPIO1") (pin "27") (pinfunction "GPIO_0_27") (pintype "unspecified+no_connect"))
    )
    (net (code "170") (name "unconnected-(GPIO1-GPIO_1-Pad28)") (class "Default")
      (node (ref "GPIO1") (pin "28") (pinfunction "GPIO_1_28") (pintype "unspecified+no_connect"))
    )
    (net (code "171") (name "unconnected-(GPIO1-GPIO_2-Pad3)") (class "Default")
      (node (ref "GPIO1") (pin "3") (pinfunction "GPIO_2_3") (pintype "unspecified+no_connect"))
    )
    (net (code "172") (name "unconnected-(GPIO1-GPIO_3-Pad5)") (class "Default")
      (node (ref "GPIO1") (pin "5") (pinfunction "GPIO_3_5") (pintype "unspecified+no_connect"))
    )
    (net (code "173") (name "unconnected-(GPIO1-GPIO_4-Pad7)") (class "Default")
      (node (ref "GPIO1") (pin "7") (pinfunction "GPIO_4_7") (pintype "unspecified+no_connect"))
    )
    (net (code "174") (name "unconnected-(GPIO1-GPIO_5-Pad29)") (class "Default")
      (node (ref "GPIO1") (pin "29") (pinfunction "GPIO_5_29") (pintype "unspecified+no_connect"))
    )
    (net (code "175") (name "unconnected-(GPIO1-GPIO_6-Pad31)") (class "Default")
      (node (ref "GPIO1") (pin "31") (pinfunction "GPIO_6_31") (pintype "unspecified+no_connect"))
    )
    (net (code "176") (name "unconnected-(GPIO1-GPIO_7-Pad26)") (class "Default")
      (node (ref "GPIO1") (pin "26") (pinfunction "GPIO_7_26") (pintype "unspecified+no_connect"))
    )
    (net (code "177") (name "unconnected-(GPIO1-GPIO_8-Pad24)") (class "Default")
      (node (ref "GPIO1") (pin "24") (pinfunction "GPIO_8_24") (pintype "unspecified+no_connect"))
    )
    (net (code "178") (name "unconnected-(GPIO1-GPIO_9-Pad21)") (class "Default")
      (node (ref "GPIO1") (pin "21") (pinfunction "GPIO_9_21") (pintype "unspecified+no_connect"))
    )
    (net (code "179") (name "unconnected-(GPIO1-GPIO_10-Pad19)") (class "Default")
      (node (ref "GPIO1") (pin "19") (pinfunction "GPIO_10_19") (pintype "unspecified+no_connect"))
    )
    (net (code "180") (name "unconnected-(GPIO1-GPIO_11-Pad23)") (class "Default")
      (node (ref "GPIO1") (pin "23") (pinfunction "GPIO_11_23") (pintype "unspecified+no_connect"))
    )
    (net (code "181") (name "unconnected-(GPIO1-GPIO_12-Pad32)") (class "Default")
      (node (ref "GPIO1") (pin "32") (pinfunction "GPIO_12_32") (pintype "unspecified+no_connect"))
    )
    (net (code "182") (name "unconnected-(GPIO1-GPIO_13-Pad33)") (class "Default")
      (node (ref "GPIO1") (pin "33") (pinfunction "GPIO_13_33") (pintype "unspecified+no_connect"))
    )
    (net (code "183") (name "unconnected-(GPIO1-GPIO_16-Pad36)") (class "Default")
      (node (ref "GPIO1") (pin "36") (pinfunction "GPIO_16_36") (pintype "unspecified+no_connect"))
    )
    (net (code "184") (name "unconnected-(GPIO1-GPIO_17-Pad11)") (class "Default")
      (node (ref "GPIO1") (pin "11") (pinfunction "GPIO_17_11") (pintype "unspecified+no_connect"))
    )
    (net (code "185") (name "unconnected-(GPIO1-GPIO_18-Pad12)") (class "Default")
      (node (ref "GPIO1") (pin "12") (pinfunction "GPIO_18_12") (pintype "unspecified+no_connect"))
    )
    (net (code "186") (name "unconnected-(GPIO1-GPIO_19-Pad35)") (class "Default")
      (node (ref "GPIO1") (pin "35") (pinfunction "GPIO_19_35") (pintype "unspecified+no_connect"))
    )
    (net (code "187") (name "unconnected-(GPIO1-GPIO_20-Pad38)") (class "Default")
      (node (ref "GPIO1") (pin "38") (pinfunction "GPIO_20_38") (pintype "unspecified+no_connect"))
    )
    (net (code "188") (name "unconnected-(GPIO1-GPIO_21-Pad40)") (class "Default")
      (node (ref "GPIO1") (pin "40") (pinfunction "GPIO_21_40") (pintype "unspecified+no_connect"))
    )
    (net (code "189") (name "unconnected-(GPIO1-GPIO_22-Pad15)") (class "Default")
      (node (ref "GPIO1") (pin "15") (pinfunction "GPIO_22_15") (pintype "unspecified+no_connect"))
    )
    (net (code "190") (name "unconnected-(GPIO1-GPIO_23-Pad16)") (class "Default")
      (node (ref "GPIO1") (pin "16") (pinfunction "GPIO_23_16") (pintype "unspecified+no_connect"))
    )
    (net (code "191") (name "unconnected-(GPIO1-GPIO_24-Pad18)") (class "Default")
      (node (ref "GPIO1") (pin "18") (pinfunction "GPIO_24_18") (pintype "unspecified+no_connect"))
    )
    (net (code "192") (name "unconnected-(GPIO1-GPIO_25-Pad22)") (class "Default")
      (node (ref "GPIO1") (pin "22") (pinfunction "GPIO_25_22") (pintype "unspecified+no_connect"))
    )
    (net (code "193") (name "unconnected-(GPIO1-GPIO_26-Pad37)") (class "Default")
      (node (ref "GPIO1") (pin "37") (pinfunction "GPIO_26_37") (pintype "unspecified+no_connect"))
    )
    (net (code "194") (name "unconnected-(GPIO1-GPIO_27-Pad13)") (class "Default")
      (node (ref "GPIO1") (pin "13") (pinfunction "GPIO_27_13") (pintype "unspecified+no_connect"))
    )
    (net (code "195") (name "unconnected-(MCP1-NC-Pad11)") (class "Default")
      (node (ref "MCP1") (pin "11") (pinfunction "NC_11") (pintype "unspecified+no_connect"))
    )
    (net (code "196") (name "unconnected-(MCP1-NC-Pad14)") (class "Default")
      (node (ref "MCP1") (pin "14") (pinfunction "NC_14") (pintype "unspecified+no_connect"))
    )
    (net (code "197") (name "unconnected-(MCP2-NC-Pad11)") (class "Default")
      (node (ref "MCP2") (pin "11") (pinfunction "NC_11") (pintype "unspecified+no_connect"))
    )
    (net (code "198") (name "unconnected-(MCP2-NC-Pad14)") (class "Default")
      (node (ref "MCP2") (pin "14") (pinfunction "NC_14") (pintype "unspecified+no_connect"))
    )
    (net (code "199") (name "unconnected-(MCP3-NC-Pad11)") (class "Default")
      (node (ref "MCP3") (pin "11") (pinfunction "NC_11") (pintype "unspecified+no_connect"))
    )
    (net (code "200") (name "unconnected-(MCP3-NC-Pad14)") (class "Default")
      (node (ref "MCP3") (pin "14") (pinfunction "NC_14") (pintype "unspecified+no_connect"))
    )
    (net (code "201") (name "unconnected-(MCP4-GPB0-Pad1)") (class "Default")
      (node (ref "MCP4") (pin "1") (pinfunction "GPB0_1") (pintype "unspecified+no_connect"))
    )
    (net (code "202") (name "unconnected-(MCP4-GPB1-Pad2)") (class "Default")
      (node (ref "MCP4") (pin "2") (pinfunction "GPB1_2") (pintype "unspecified+no_connect"))
    )
    (net (code "203") (name "unconnected-(MCP4-GPB2-Pad3)") (class "Default")
      (node (ref "MCP4") (pin "3") (pinfunction "GPB2_3") (pintype "unspecified+no_connect"))
    )
    (net (code "204") (name "unconnected-(MCP4-GPB3-Pad4)") (class "Default")
      (node (ref "MCP4") (pin "4") (pinfunction "GPB3_4") (pintype "unspecified+no_connect"))
    )
    (net (code "205") (name "unconnected-(MCP4-GPB4-Pad5)") (class "Default")
      (node (ref "MCP4") (pin "5") (pinfunction "GPB4_5") (pintype "unspecified+no_connect"))
    )
    (net (code "206") (name "unconnected-(MCP4-GPB5-Pad6)") (class "Default")
      (node (ref "MCP4") (pin "6") (pinfunction "GPB5_6") (pintype "unspecified+no_connect"))
    )
    (net (code "207") (name "unconnected-(MCP4-GPB6-Pad7)") (class "Default")
      (node (ref "MCP4") (pin "7") (pinfunction "GPB6_7") (pintype "unspecified+no_connect"))
    )
    (net (code "208") (name "unconnected-(MCP4-GPB7-Pad8)") (class "Default")
      (node (ref "MCP4") (pin "8") (pinfunction "GPB7_8") (pintype "unspecified+no_connect"))
    )
    (net (code "209") (name "unconnected-(MCP4-NC-Pad11)") (class "Default")
      (node (ref "MCP4") (pin "11") (pinfunction "NC_11") (pintype "unspecified+no_connect"))
    )
    (net (code "210") (name "unconnected-(MCP4-NC-Pad14)") (class "Default")
      (node (ref "MCP4") (pin "14") (pinfunction "NC_14") (pintype "unspecified+no_connect"))
    )
    (net (code "211") (name "unconnected-(U3-OUT22-Pad27)") (class "Default")
      (node (ref "U3") (pin "27") (pinfunction "OUT22_27") (pintype "unspecified+no_connect"))
    )
    (net (code "212") (name "unconnected-(U3-OUT23-Pad28)") (class "Default")
      (node (ref "U3") (pin "28") (pinfunction "OUT23_28") (pintype "unspecified+no_connect"))
    )
    (net (code "213") (name "unconnected-(U3-SOUT-Pad29)") (class "Default")
      (node (ref "U3") (pin "29") (pinfunction "SOUT_29") (pintype "unspecified+no_connect"))
    )
    (net (code "214") (name "unconnected-(U5-3V3_EN-Pad37)") (class "Default")
      (node (ref "U5") (pin "37") (pinfunction "3V3_EN_37") (pintype "bidirectional+no_connect"))
    )
    (net (code "215") (name "unconnected-(U5-ADC2{slash}GP28-Pad34)") (class "Default")
      (node (ref "U5") (pin "34") (pinfunction "ADC2/GP28_34") (pintype "bidirectional+no_connect"))
    )
    (net (code "216") (name "unconnected-(U5-ADC_VREF-Pad35)") (class "Default")
      (node (ref "U5") (pin "35") (pinfunction "ADC_VREF_35") (pintype "bidirectional+no_connect"))
    )
    (net (code "217") (name "unconnected-(U5-BOOTSEL-PadTP6)") (class "Default")
      (node (ref "U5") (pin "TP6") (pinfunction "BOOTSEL_TP6") (pintype "unspecified+no_connect"))
    )
    (net (code "218") (name "unconnected-(U5-GND-PadTP1)") (class "Default")
      (node (ref "U5") (pin "TP1") (pinfunction "GND_TP1") (pintype "bidirectional+no_connect"))
    )
    (net (code "219") (name "unconnected-(U5-GPIO25{slash}LED-PadTP5)") (class "Default")
      (node (ref "U5") (pin "TP5") (pinfunction "GPIO25/LED_TP5") (pintype "unspecified+no_connect"))
    )
    (net (code "220") (name "unconnected-(U5-GPIO{slash}SMPS-PadTP4)") (class "Default")
      (node (ref "U5") (pin "TP4") (pinfunction "GPIO/SMPS_TP4") (pintype "unspecified+no_connect"))
    )
    (net (code "221") (name "unconnected-(U5-I2C0_SCL{slash}GP21-Pad27)") (class "Default")
      (node (ref "U5") (pin "27") (pinfunction "I2C0_SCL/GP21_27") (pintype "bidirectional+no_connect"))
    )
    (net (code "222") (name "unconnected-(U5-I2C1_SCL{slash}ADC1{slash}GP27-Pad32)") (class "Default")
      (node (ref "U5") (pin "32") (pinfunction "I2C1_SCL/ADC1/GP27_32") (pintype "bidirectional+no_connect"))
    )
    (net (code "223") (name "unconnected-(U5-I2C1_SCL{slash}SPI1_TX{slash}GP11-Pad15)") (class "Default")
      (node (ref "U5") (pin "15") (pinfunction "I2C1_SCL/SPI1_TX/GP11_15") (pintype "bidirectional+no_connect"))
    )
    (net (code "224") (name "unconnected-(U5-I2C1_SCL{slash}SPI1_TX{slash}GP15-Pad20)") (class "Default")
      (node (ref "U5") (pin "20") (pinfunction "I2C1_SCL/SPI1_TX/GP15_20") (pintype "bidirectional+no_connect"))
    )
    (net (code "225") (name "unconnected-(U5-I2C1_SDA{slash}ADC0{slash}GP26-Pad31)") (class "Default")
      (node (ref "U5") (pin "31") (pinfunction "I2C1_SDA/ADC0/GP26_31") (pintype "bidirectional+no_connect"))
    )
    (net (code "226") (name "unconnected-(U5-I2C1_SDA{slash}SPI1_SCK{slash}GP10-Pad14)") (class "Default")
      (node (ref "U5") (pin "14") (pinfunction "I2C1_SDA/SPI1_SCK/GP10_14") (pintype "bidirectional+no_connect"))
    )
    (net (code "227") (name "unconnected-(U5-I2C1_SDA{slash}SPI1_SCK{slash}GP14-Pad19)") (class "Default")
      (node (ref "U5") (pin "19") (pinfunction "I2C1_SDA/SPI1_SCK/GP14_19") (pintype "bidirectional+no_connect"))
    )
    (net (code "228") (name "unconnected-(U5-RUN-Pad30)") (class "Default")
      (node (ref "U5") (pin "30") (pinfunction "RUN_30") (pintype "unspecified+no_connect"))
    )
    (net (code "229") (name "unconnected-(U5-SWCLK-PadD1)") (class "Default")
      (node (ref "U5") (pin "D1") (pinfunction "SWCLK_D1") (pintype "unspecified+no_connect"))
    )
    (net (code "230") (name "unconnected-(U5-SWDIO-PadD3)") (class "Default")
      (node (ref "U5") (pin "D3") (pinfunction "SWDIO_D3") (pintype "unspecified+no_connect"))
    )
    (net (code "231") (name "unconnected-(U5-UART0_RX{slash}I2C0_SCL{slash}SPI1_CSn{slash}GP13-Pad17)") (class "Default")
      (node (ref "U5") (pin "17") (pinfunction "UART0_RX/I2C0_SCL/SPI1_CSn/GP13_17") (pintype "bidirectional+no_connect"))
    )
    (net (code "232") (name "unconnected-(U5-UART0_TX{slash}I2C0_SDA{slash}GPI1_RX{slash}GP12-Pad16)") (class "Default")
      (node (ref "U5") (pin "16") (pinfunction "UART0_TX/I2C0_SDA/GPI1_RX/GP12_16") (pintype "bidirectional+no_connect"))
    )
    (net (code "233") (name "unconnected-(U5-USB_DM-PadTP2)") (class "Default")
      (node (ref "U5") (pin "TP2") (pinfunction "USB_DM_TP2") (pintype "unspecified+no_connect"))
    )
    (net (code "234") (name "unconnected-(U5-USB_DP-PadTP3)") (class "Default")
      (node (ref "U5") (pin "TP3") (pinfunction "USB_DP_TP3") (pintype "unspecified+no_connect"))
    )
    (net (code "235") (name "unconnected-(U5-VBUS-Pad40)") (class "Default")
      (node (ref "U5") (pin "40") (pinfunction "VBUS_40") (pintype "bidirectional+no_connect"))
    )
    (net (code "236") (name "unconnected-(U8-SW-Pad1)") (class "Default")
      (node (ref "U8") (pin "1") (pinfunction "SW_1") (pintype "unspecified+no_connect"))
    )
    (net (code "237") (name "unconnected-(U9-SW-Pad1)") (class "Default")
      (node (ref "U9") (pin "1") (pinfunction "SW_1") (pintype "unspecified+no_connect"))
    )
    (net (code "238") (name "unconnected-(U45-Pad3)") (class "Default")
      (node (ref "U45") (pin "3") (pinfunction "3_3") (pintype "unspecified+no_connect"))
    )
  )
)
